# DRI-21700-flexpcb-12s4p.net
KiCad netlist of a schematic drawn in EAGLE
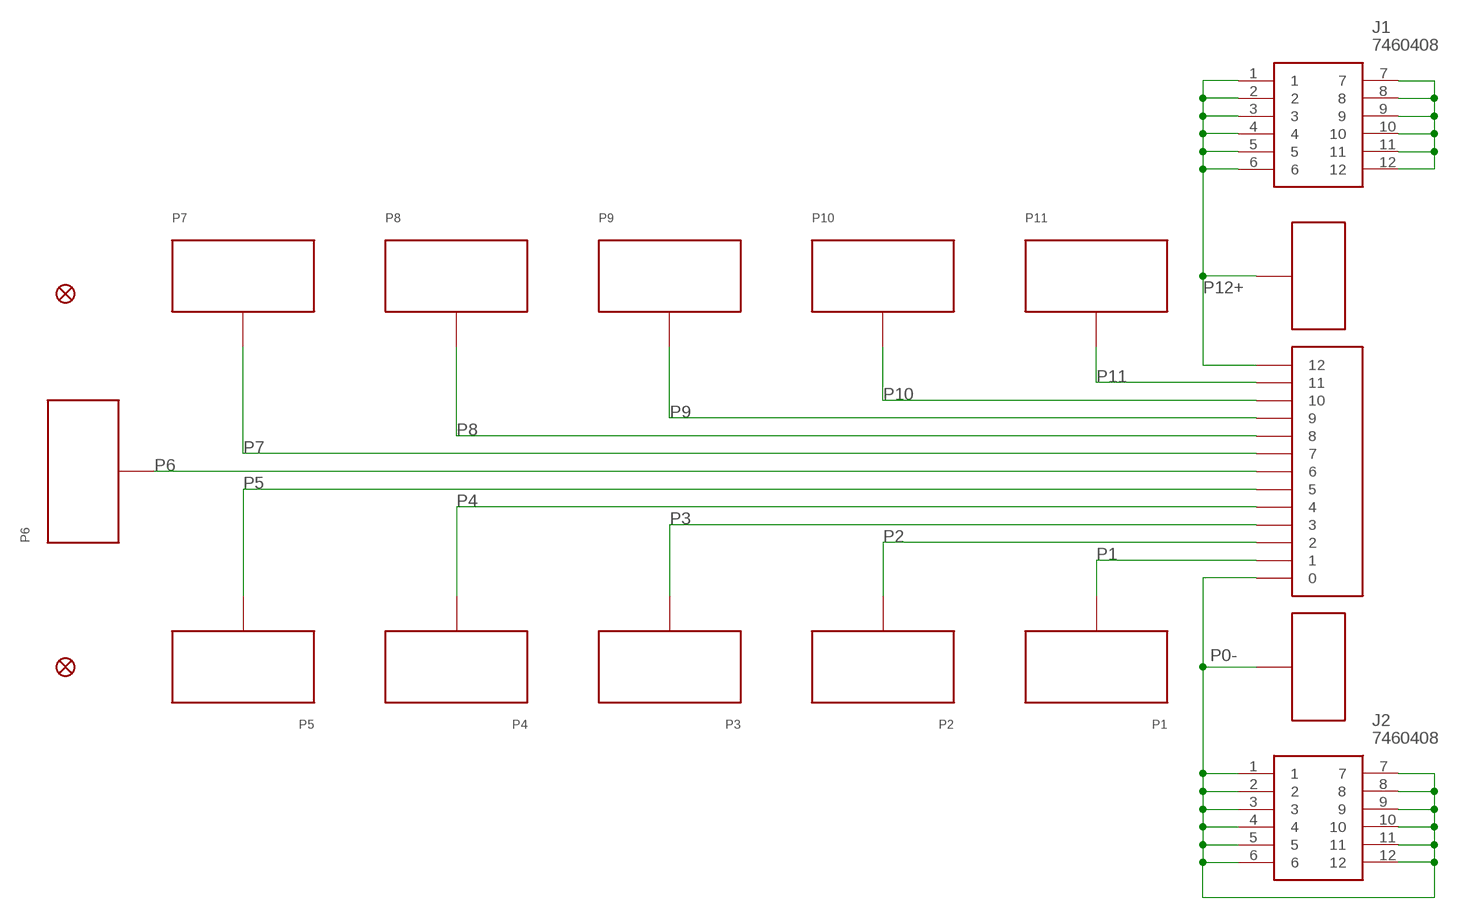
[diagram p0: schematic, sheet 1]

(export (version "E")
  (design (tool "Eeschema 10.0.6"))
  (components
    (comp (ref "FD1")
      (value "FIDUCIAL1X2")
      (footprint "eagle-import:FIDUCIAL-1X2")
      (libsource (lib "eagle-import") (part "FIDUCIAL1X2"))
    )
    (comp (ref "FD2")
      (value "FIDUCIAL1X2")
      (footprint "eagle-import:FIDUCIAL-1X2")
      (libsource (lib "eagle-import") (part "FIDUCIAL1X2"))
    )
    (comp (ref "J1")
      (value "7460408")
      (footprint "eagle-import:7460408")
      (fields (field (name "MOUSER_PART_NUMBER") "710-7460408"))
      (libsource (lib "eagle-import") (part "7460408"))
    )
    (comp (ref "J2")
      (value "7460408")
      (footprint "eagle-import:7460408")
      (fields (field (name "MOUSER_PART_NUMBER") "710-7460408"))
      (libsource (lib "eagle-import") (part "7460408"))
    )
    (comp (ref "JP1")
      (value "13P-JST-2MM")
      (footprint "eagle-import:13P-JST-2MM")
      (libsource (lib "eagle-import") (part "13P-JST-2MM"))
    )
    (comp (ref "P0")
      (value "BUS-TERM-PAD+")
      (footprint "eagle-import:TERM-PAD-")
      (libsource (lib "eagle-import") (part "BUS-TERM-PAD+"))
    )
    (comp (ref "P1")
      (value "BAT-TERM-L")
      (footprint "eagle-import:BAT-TERM-L")
      (libsource (lib "eagle-import") (part "BAT-TERM-L"))
    )
    (comp (ref "P2")
      (value "BAT-TERM-M")
      (footprint "eagle-import:BAT-TERM-M")
      (libsource (lib "eagle-import") (part "BAT-TERM-M"))
    )
    (comp (ref "P3")
      (value "BAT-TERM-L")
      (footprint "eagle-import:BAT-TERM-L")
      (libsource (lib "eagle-import") (part "BAT-TERM-L"))
    )
    (comp (ref "P4")
      (value "BAT-TERM-M")
      (footprint "eagle-import:BAT-TERM-M")
      (libsource (lib "eagle-import") (part "BAT-TERM-M"))
    )
    (comp (ref "P5")
      (value "BAT-TERM-L")
      (footprint "eagle-import:BAT-TERM-L")
      (libsource (lib "eagle-import") (part "BAT-TERM-L"))
    )
    (comp (ref "P6")
      (value "BAT-TERM-END")
      (footprint "eagle-import:BAT-TERM-END")
      (libsource (lib "eagle-import") (part "BAT-TERM-END"))
    )
    (comp (ref "P7")
      (value "BAT-TERM-L")
      (footprint "eagle-import:BAT-TERM-L")
      (libsource (lib "eagle-import") (part "BAT-TERM-L"))
    )
    (comp (ref "P8")
      (value "BAT-TERM-M")
      (footprint "eagle-import:BAT-TERM-M")
      (libsource (lib "eagle-import") (part "BAT-TERM-M"))
    )
    (comp (ref "P9")
      (value "BAT-TERM-L")
      (footprint "eagle-import:BAT-TERM-L")
      (libsource (lib "eagle-import") (part "BAT-TERM-L"))
    )
    (comp (ref "P10")
      (value "BAT-TERM-M")
      (footprint "eagle-import:BAT-TERM-M")
      (libsource (lib "eagle-import") (part "BAT-TERM-M"))
    )
    (comp (ref "P11")
      (value "BAT-TERM-L")
      (footprint "eagle-import:BAT-TERM-L")
      (libsource (lib "eagle-import") (part "BAT-TERM-L"))
    )
    (comp (ref "P12")
      (value "BUS-TERM-PAD+")
      (footprint "eagle-import:TERM-PAD-")
      (libsource (lib "eagle-import") (part "BUS-TERM-PAD+"))
    )
  )
  (nets
    (net (code "1") (name "/P0-") (class "Default")
      (node (ref "J2") (pin "1") (pinfunction "1_1") (pintype "bidirectional"))
      (node (ref "J2") (pin "10") (pinfunction "10_10") (pintype "bidirectional"))
      (node (ref "J2") (pin "11") (pinfunction "11_11") (pintype "bidirectional"))
      (node (ref "J2") (pin "12") (pinfunction "12_12") (pintype "bidirectional"))
      (node (ref "J2") (pin "2") (pinfunction "2_2") (pintype "bidirectional"))
      (node (ref "J2") (pin "3") (pinfunction "3_3") (pintype "bidirectional"))
      (node (ref "J2") (pin "4") (pinfunction "4_4") (pintype "bidirectional"))
      (node (ref "J2") (pin "5") (pinfunction "5_5") (pintype "bidirectional"))
      (node (ref "J2") (pin "6") (pinfunction "6_6") (pintype "bidirectional"))
      (node (ref "J2") (pin "7") (pinfunction "7_7") (pintype "bidirectional"))
      (node (ref "J2") (pin "8") (pinfunction "8_8") (pintype "bidirectional"))
      (node (ref "J2") (pin "9") (pinfunction "9_9") (pintype "bidirectional"))
      (node (ref "JP1") (pin "P$1") (pinfunction "0_P$1") (pintype "bidirectional"))
      (node (ref "P0") (pin "P$10") (pinfunction "P$0_P$10") (pintype "power_in"))
      (node (ref "P0") (pin "P$100") (pinfunction "P$0_P$100") (pintype "power_in"))
      (node (ref "P0") (pin "P$101") (pinfunction "P$0_P$101") (pintype "power_in"))
      (node (ref "P0") (pin "P$102") (pinfunction "P$0_P$102") (pintype "power_in"))
      (node (ref "P0") (pin "P$103") (pinfunction "P$0_P$103") (pintype "power_in"))
      (node (ref "P0") (pin "P$104") (pinfunction "P$0_P$104") (pintype "power_in"))
      (node (ref "P0") (pin "P$105") (pinfunction "P$0_P$105") (pintype "power_in"))
      (node (ref "P0") (pin "P$106") (pinfunction "P$0_P$106") (pintype "power_in"))
      (node (ref "P0") (pin "P$107") (pinfunction "P$0_P$107") (pintype "power_in"))
      (node (ref "P0") (pin "P$108") (pinfunction "P$0_P$108") (pintype "power_in"))
      (node (ref "P0") (pin "P$109") (pinfunction "P$0_P$109") (pintype "power_in"))
      (node (ref "P0") (pin "P$11") (pinfunction "P$0_P$11") (pintype "power_in"))
      (node (ref "P0") (pin "P$110") (pinfunction "P$0_P$110") (pintype "power_in"))
      (node (ref "P0") (pin "P$12") (pinfunction "P$0_P$12") (pintype "power_in"))
      (node (ref "P0") (pin "P$13") (pinfunction "P$0_P$13") (pintype "power_in"))
      (node (ref "P0") (pin "P$14") (pinfunction "P$0_P$14") (pintype "power_in"))
      (node (ref "P0") (pin "P$15") (pinfunction "P$0_P$15") (pintype "power_in"))
      (node (ref "P0") (pin "P$16") (pinfunction "P$0_P$16") (pintype "power_in"))
      (node (ref "P0") (pin "P$17") (pinfunction "P$0_P$17") (pintype "power_in"))
      (node (ref "P0") (pin "P$18") (pinfunction "P$0_P$18") (pintype "power_in"))
      (node (ref "P0") (pin "P$181") (pinfunction "P$0_P$181") (pintype "power_in"))
      (node (ref "P0") (pin "P$182") (pinfunction "P$0_P$182") (pintype "power_in"))
      (node (ref "P0") (pin "P$183") (pinfunction "P$0_P$183") (pintype "power_in"))
      (node (ref "P0") (pin "P$184") (pinfunction "P$0_P$184") (pintype "power_in"))
      (node (ref "P0") (pin "P$185") (pinfunction "P$0_P$185") (pintype "power_in"))
      (node (ref "P0") (pin "P$186") (pinfunction "P$0_P$186") (pintype "power_in"))
      (node (ref "P0") (pin "P$187") (pinfunction "P$0_P$187") (pintype "power_in"))
      (node (ref "P0") (pin "P$188") (pinfunction "P$0_P$188") (pintype "power_in"))
      (node (ref "P0") (pin "P$189") (pinfunction "P$0_P$189") (pintype "power_in"))
      (node (ref "P0") (pin "P$19") (pinfunction "P$0_P$19") (pintype "power_in"))
      (node (ref "P0") (pin "P$190") (pinfunction "P$0_P$190") (pintype "power_in"))
      (node (ref "P0") (pin "P$191") (pinfunction "P$0_P$191") (pintype "power_in"))
      (node (ref "P0") (pin "P$192") (pinfunction "P$0_P$192") (pintype "power_in"))
      (node (ref "P0") (pin "P$193") (pinfunction "P$0_P$193") (pintype "power_in"))
      (node (ref "P0") (pin "P$194") (pinfunction "P$0_P$194") (pintype "power_in"))
      (node (ref "P0") (pin "P$195") (pinfunction "P$0_P$195") (pintype "power_in"))
      (node (ref "P0") (pin "P$196") (pinfunction "P$0_P$196") (pintype "power_in"))
      (node (ref "P0") (pin "P$197") (pinfunction "P$0_P$197") (pintype "power_in"))
      (node (ref "P0") (pin "P$198") (pinfunction "P$0_P$198") (pintype "power_in"))
      (node (ref "P0") (pin "P$199") (pinfunction "P$0_P$199") (pintype "power_in"))
      (node (ref "P0") (pin "P$20") (pinfunction "P$0_P$20") (pintype "power_in"))
      (node (ref "P0") (pin "P$200") (pinfunction "P$0_P$200") (pintype "power_in"))
      (node (ref "P0") (pin "P$201") (pinfunction "P$0_P$201") (pintype "power_in"))
      (node (ref "P0") (pin "P$202") (pinfunction "P$0_P$202") (pintype "power_in"))
      (node (ref "P0") (pin "P$203") (pinfunction "P$0_P$203") (pintype "power_in"))
      (node (ref "P0") (pin "P$204") (pinfunction "P$0_P$204") (pintype "power_in"))
      (node (ref "P0") (pin "P$205") (pinfunction "P$0_P$205") (pintype "power_in"))
      (node (ref "P0") (pin "P$206") (pinfunction "P$0_P$206") (pintype "power_in"))
      (node (ref "P0") (pin "P$207") (pinfunction "P$0_P$207") (pintype "power_in"))
      (node (ref "P0") (pin "P$208") (pinfunction "P$0_P$208") (pintype "power_in"))
      (node (ref "P0") (pin "P$209") (pinfunction "P$0_P$209") (pintype "power_in"))
      (node (ref "P0") (pin "P$21") (pinfunction "P$0_P$21") (pintype "power_in"))
      (node (ref "P0") (pin "P$210") (pinfunction "P$0_P$210") (pintype "power_in"))
      (node (ref "P0") (pin "P$211") (pinfunction "P$0_P$211") (pintype "power_in"))
      (node (ref "P0") (pin "P$212") (pinfunction "P$0_P$212") (pintype "power_in"))
      (node (ref "P0") (pin "P$213") (pinfunction "P$0_P$213") (pintype "power_in"))
      (node (ref "P0") (pin "P$214") (pinfunction "P$0_P$214") (pintype "power_in"))
      (node (ref "P0") (pin "P$215") (pinfunction "P$0_P$215") (pintype "power_in"))
      (node (ref "P0") (pin "P$216") (pinfunction "P$0_P$216") (pintype "power_in"))
      (node (ref "P0") (pin "P$217") (pinfunction "P$0_P$217") (pintype "power_in"))
      (node (ref "P0") (pin "P$218") (pinfunction "P$0_P$218") (pintype "power_in"))
      (node (ref "P0") (pin "P$219") (pinfunction "P$0_P$219") (pintype "power_in"))
      (node (ref "P0") (pin "P$22") (pinfunction "P$0_P$22") (pintype "power_in"))
      (node (ref "P0") (pin "P$220") (pinfunction "P$0_P$220") (pintype "power_in"))
      (node (ref "P0") (pin "P$221") (pinfunction "P$0_P$221") (pintype "power_in"))
      (node (ref "P0") (pin "P$222") (pinfunction "P$0_P$222") (pintype "power_in"))
      (node (ref "P0") (pin "P$223") (pinfunction "P$0_P$223") (pintype "power_in"))
      (node (ref "P0") (pin "P$224") (pinfunction "P$0_P$224") (pintype "power_in"))
      (node (ref "P0") (pin "P$225") (pinfunction "P$0_P$225") (pintype "power_in"))
      (node (ref "P0") (pin "P$226") (pinfunction "P$0_P$226") (pintype "power_in"))
      (node (ref "P0") (pin "P$227") (pinfunction "P$0_P$227") (pintype "power_in"))
      (node (ref "P0") (pin "P$228") (pinfunction "P$0_P$228") (pintype "power_in"))
      (node (ref "P0") (pin "P$229") (pinfunction "P$0_P$229") (pintype "power_in"))
      (node (ref "P0") (pin "P$23") (pinfunction "P$0_P$23") (pintype "power_in"))
      (node (ref "P0") (pin "P$230") (pinfunction "P$0_P$230") (pintype "power_in"))
      (node (ref "P0") (pin "P$231") (pinfunction "P$0_P$231") (pintype "power_in"))
      (node (ref "P0") (pin "P$232") (pinfunction "P$0_P$232") (pintype "power_in"))
      (node (ref "P0") (pin "P$233") (pinfunction "P$0_P$233") (pintype "power_in"))
      (node (ref "P0") (pin "P$234") (pinfunction "P$0_P$234") (pintype "power_in"))
      (node (ref "P0") (pin "P$235") (pinfunction "P$0_P$235") (pintype "power_in"))
      (node (ref "P0") (pin "P$236") (pinfunction "P$0_P$236") (pintype "power_in"))
      (node (ref "P0") (pin "P$237") (pinfunction "P$0_P$237") (pintype "power_in"))
      (node (ref "P0") (pin "P$238") (pinfunction "P$0_P$238") (pintype "power_in"))
      (node (ref "P0") (pin "P$239") (pinfunction "P$0_P$239") (pintype "power_in"))
      (node (ref "P0") (pin "P$24") (pinfunction "P$0_P$24") (pintype "power_in"))
      (node (ref "P0") (pin "P$240") (pinfunction "P$0_P$240") (pintype "power_in"))
      (node (ref "P0") (pin "P$241") (pinfunction "P$0_P$241") (pintype "power_in"))
      (node (ref "P0") (pin "P$242") (pinfunction "P$0_P$242") (pintype "power_in"))
      (node (ref "P0") (pin "P$243") (pinfunction "P$0_P$243") (pintype "power_in"))
      (node (ref "P0") (pin "P$244") (pinfunction "P$0_P$244") (pintype "power_in"))
      (node (ref "P0") (pin "P$245") (pinfunction "P$0_P$245") (pintype "power_in"))
      (node (ref "P0") (pin "P$246") (pinfunction "P$0_P$246") (pintype "power_in"))
      (node (ref "P0") (pin "P$247") (pinfunction "P$0_P$247") (pintype "power_in"))
      (node (ref "P0") (pin "P$248") (pinfunction "P$0_P$248") (pintype "power_in"))
      (node (ref "P0") (pin "P$249") (pinfunction "P$0_P$249") (pintype "power_in"))
      (node (ref "P0") (pin "P$25") (pinfunction "P$0_P$25") (pintype "power_in"))
      (node (ref "P0") (pin "P$250") (pinfunction "P$0_P$250") (pintype "power_in"))
      (node (ref "P0") (pin "P$251") (pinfunction "P$0_P$251") (pintype "power_in"))
      (node (ref "P0") (pin "P$252") (pinfunction "P$0_P$252") (pintype "power_in"))
      (node (ref "P0") (pin "P$253") (pinfunction "P$0_P$253") (pintype "power_in"))
      (node (ref "P0") (pin "P$254") (pinfunction "P$0_P$254") (pintype "power_in"))
      (node (ref "P0") (pin "P$255") (pinfunction "P$0_P$255") (pintype "power_in"))
      (node (ref "P0") (pin "P$256") (pinfunction "P$0_P$256") (pintype "power_in"))
      (node (ref "P0") (pin "P$257") (pinfunction "P$0_P$257") (pintype "power_in"))
      (node (ref "P0") (pin "P$258") (pinfunction "P$0_P$258") (pintype "power_in"))
      (node (ref "P0") (pin "P$259") (pinfunction "P$0_P$259") (pintype "power_in"))
      (node (ref "P0") (pin "P$26") (pinfunction "P$0_P$26") (pintype "power_in"))
      (node (ref "P0") (pin "P$260") (pinfunction "P$0_P$260") (pintype "power_in"))
      (node (ref "P0") (pin "P$261") (pinfunction "P$0_P$261") (pintype "power_in"))
      (node (ref "P0") (pin "P$262") (pinfunction "P$0_P$262") (pintype "power_in"))
      (node (ref "P0") (pin "P$263") (pinfunction "P$0_P$263") (pintype "power_in"))
      (node (ref "P0") (pin "P$264") (pinfunction "P$0_P$264") (pintype "power_in"))
      (node (ref "P0") (pin "P$265") (pinfunction "P$0_P$265") (pintype "power_in"))
      (node (ref "P0") (pin "P$266") (pinfunction "P$0_P$266") (pintype "power_in"))
      (node (ref "P0") (pin "P$267") (pinfunction "P$0_P$267") (pintype "power_in"))
      (node (ref "P0") (pin "P$268") (pinfunction "P$0_P$268") (pintype "power_in"))
      (node (ref "P0") (pin "P$269") (pinfunction "P$0_P$269") (pintype "power_in"))
      (node (ref "P0") (pin "P$27") (pinfunction "P$0_P$27") (pintype "power_in"))
      (node (ref "P0") (pin "P$270") (pinfunction "P$0_P$270") (pintype "power_in"))
      (node (ref "P0") (pin "P$271") (pinfunction "P$0_P$271") (pintype "power_in"))
      (node (ref "P0") (pin "P$272") (pinfunction "P$0_P$272") (pintype "power_in"))
      (node (ref "P0") (pin "P$273") (pinfunction "P$0_P$273") (pintype "power_in"))
      (node (ref "P0") (pin "P$274") (pinfunction "P$0_P$274") (pintype "power_in"))
      (node (ref "P0") (pin "P$275") (pinfunction "P$0_P$275") (pintype "power_in"))
      (node (ref "P0") (pin "P$276") (pinfunction "P$0_P$276") (pintype "power_in"))
      (node (ref "P0") (pin "P$277") (pinfunction "P$0_P$277") (pintype "power_in"))
      (node (ref "P0") (pin "P$278") (pinfunction "P$0_P$278") (pintype "power_in"))
      (node (ref "P0") (pin "P$279") (pinfunction "P$0_P$279") (pintype "power_in"))
      (node (ref "P0") (pin "P$28") (pinfunction "P$0_P$28") (pintype "power_in"))
      (node (ref "P0") (pin "P$280") (pinfunction "P$0_P$280") (pintype "power_in"))
      (node (ref "P0") (pin "P$281") (pinfunction "P$0_P$281") (pintype "power_in"))
      (node (ref "P0") (pin "P$282") (pinfunction "P$0_P$282") (pintype "power_in"))
      (node (ref "P0") (pin "P$283") (pinfunction "P$0_P$283") (pintype "power_in"))
      (node (ref "P0") (pin "P$284") (pinfunction "P$0_P$284") (pintype "power_in"))
      (node (ref "P0") (pin "P$285") (pinfunction "P$0_P$285") (pintype "power_in"))
      (node (ref "P0") (pin "P$286") (pinfunction "P$0_P$286") (pintype "power_in"))
      (node (ref "P0") (pin "P$287") (pinfunction "P$0_P$287") (pintype "power_in"))
      (node (ref "P0") (pin "P$288") (pinfunction "P$0_P$288") (pintype "power_in"))
      (node (ref "P0") (pin "P$289") (pinfunction "P$0_P$289") (pintype "power_in"))
      (node (ref "P0") (pin "P$29") (pinfunction "P$0_P$29") (pintype "power_in"))
      (node (ref "P0") (pin "P$290") (pinfunction "P$0_P$290") (pintype "power_in"))
      (node (ref "P0") (pin "P$291") (pinfunction "P$0_P$291") (pintype "power_in"))
      (node (ref "P0") (pin "P$292") (pinfunction "P$0_P$292") (pintype "power_in"))
      (node (ref "P0") (pin "P$293") (pinfunction "P$0_P$293") (pintype "power_in"))
      (node (ref "P0") (pin "P$294") (pinfunction "P$0_P$294") (pintype "power_in"))
      (node (ref "P0") (pin "P$295") (pinfunction "P$0_P$295") (pintype "power_in"))
      (node (ref "P0") (pin "P$296") (pinfunction "P$0_P$296") (pintype "power_in"))
      (node (ref "P0") (pin "P$297") (pinfunction "P$0_P$297") (pintype "power_in"))
      (node (ref "P0") (pin "P$298") (pinfunction "P$0_P$298") (pintype "power_in"))
      (node (ref "P0") (pin "P$299") (pinfunction "P$0_P$299") (pintype "power_in"))
      (node (ref "P0") (pin "P$3") (pinfunction "P$0_P$3") (pintype "power_in"))
      (node (ref "P0") (pin "P$30") (pinfunction "P$0_P$30") (pintype "power_in"))
      (node (ref "P0") (pin "P$300") (pinfunction "P$0_P$300") (pintype "power_in"))
      (node (ref "P0") (pin "P$301") (pinfunction "P$0_P$301") (pintype "power_in"))
      (node (ref "P0") (pin "P$302") (pinfunction "P$0_P$302") (pintype "power_in"))
      (node (ref "P0") (pin "P$303") (pinfunction "P$0_P$303") (pintype "power_in"))
      (node (ref "P0") (pin "P$304") (pinfunction "P$0_P$304") (pintype "power_in"))
      (node (ref "P0") (pin "P$305") (pinfunction "P$0_P$305") (pintype "power_in"))
      (node (ref "P0") (pin "P$306") (pinfunction "P$0_P$306") (pintype "power_in"))
      (node (ref "P0") (pin "P$307") (pinfunction "P$0_P$307") (pintype "power_in"))
      (node (ref "P0") (pin "P$308") (pinfunction "P$0_P$308") (pintype "power_in"))
      (node (ref "P0") (pin "P$309") (pinfunction "P$0_P$309") (pintype "power_in"))
      (node (ref "P0") (pin "P$31") (pinfunction "P$0_P$31") (pintype "power_in"))
      (node (ref "P0") (pin "P$310") (pinfunction "P$0_P$310") (pintype "power_in"))
      (node (ref "P0") (pin "P$311") (pinfunction "P$0_P$311") (pintype "power_in"))
      (node (ref "P0") (pin "P$312") (pinfunction "P$0_P$312") (pintype "power_in"))
      (node (ref "P0") (pin "P$313") (pinfunction "P$0_P$313") (pintype "power_in"))
      (node (ref "P0") (pin "P$314") (pinfunction "P$0_P$314") (pintype "power_in"))
      (node (ref "P0") (pin "P$315") (pinfunction "P$0_P$315") (pintype "power_in"))
      (node (ref "P0") (pin "P$316") (pinfunction "P$0_P$316") (pintype "power_in"))
      (node (ref "P0") (pin "P$317") (pinfunction "P$0_P$317") (pintype "power_in"))
      (node (ref "P0") (pin "P$318") (pinfunction "P$0_P$318") (pintype "power_in"))
      (node (ref "P0") (pin "P$319") (pinfunction "P$0_P$319") (pintype "power_in"))
      (node (ref "P0") (pin "P$32") (pinfunction "P$0_P$32") (pintype "power_in"))
      (node (ref "P0") (pin "P$320") (pinfunction "P$0_P$320") (pintype "power_in"))
      (node (ref "P0") (pin "P$321") (pinfunction "P$0_P$321") (pintype "power_in"))
      (node (ref "P0") (pin "P$322") (pinfunction "P$0_P$322") (pintype "power_in"))
      (node (ref "P0") (pin "P$323") (pinfunction "P$0_P$323") (pintype "power_in"))
      (node (ref "P0") (pin "P$324") (pinfunction "P$0_P$324") (pintype "power_in"))
      (node (ref "P0") (pin "P$325") (pinfunction "P$0_P$325") (pintype "power_in"))
      (node (ref "P0") (pin "P$326") (pinfunction "P$0_P$326") (pintype "power_in"))
      (node (ref "P0") (pin "P$327") (pinfunction "P$0_P$327") (pintype "power_in"))
      (node (ref "P0") (pin "P$328") (pinfunction "P$0_P$328") (pintype "power_in"))
      (node (ref "P0") (pin "P$329") (pinfunction "P$0_P$329") (pintype "power_in"))
      (node (ref "P0") (pin "P$33") (pinfunction "P$0_P$33") (pintype "power_in"))
      (node (ref "P0") (pin "P$330") (pinfunction "P$0_P$330") (pintype "power_in"))
      (node (ref "P0") (pin "P$331") (pinfunction "P$0_P$331") (pintype "power_in"))
      (node (ref "P0") (pin "P$332") (pinfunction "P$0_P$332") (pintype "power_in"))
      (node (ref "P0") (pin "P$333") (pinfunction "P$0_P$333") (pintype "power_in"))
      (node (ref "P0") (pin "P$334") (pinfunction "P$0_P$334") (pintype "power_in"))
      (node (ref "P0") (pin "P$335") (pinfunction "P$0_P$335") (pintype "power_in"))
      (node (ref "P0") (pin "P$336") (pinfunction "P$0_P$336") (pintype "power_in"))
      (node (ref "P0") (pin "P$337") (pinfunction "P$0_P$337") (pintype "power_in"))
      (node (ref "P0") (pin "P$338") (pinfunction "P$0_P$338") (pintype "power_in"))
      (node (ref "P0") (pin "P$339") (pinfunction "P$0_P$339") (pintype "power_in"))
      (node (ref "P0") (pin "P$34") (pinfunction "P$0_P$34") (pintype "power_in"))
      (node (ref "P0") (pin "P$340") (pinfunction "P$0_P$340") (pintype "power_in"))
      (node (ref "P0") (pin "P$341") (pinfunction "P$0_P$341") (pintype "power_in"))
      (node (ref "P0") (pin "P$342") (pinfunction "P$0_P$342") (pintype "power_in"))
      (node (ref "P0") (pin "P$343") (pinfunction "P$0_P$343") (pintype "power_in"))
      (node (ref "P0") (pin "P$344") (pinfunction "P$0_P$344") (pintype "power_in"))
      (node (ref "P0") (pin "P$345") (pinfunction "P$0_P$345") (pintype "power_in"))
      (node (ref "P0") (pin "P$346") (pinfunction "P$0_P$346") (pintype "power_in"))
      (node (ref "P0") (pin "P$347") (pinfunction "P$0_P$347") (pintype "power_in"))
      (node (ref "P0") (pin "P$348") (pinfunction "P$0_P$348") (pintype "power_in"))
      (node (ref "P0") (pin "P$349") (pinfunction "P$0_P$349") (pintype "power_in"))
      (node (ref "P0") (pin "P$35") (pinfunction "P$0_P$35") (pintype "power_in"))
      (node (ref "P0") (pin "P$350") (pinfunction "P$0_P$350") (pintype "power_in"))
      (node (ref "P0") (pin "P$351") (pinfunction "P$0_P$351") (pintype "power_in"))
      (node (ref "P0") (pin "P$352") (pinfunction "P$0_P$352") (pintype "power_in"))
      (node (ref "P0") (pin "P$353") (pinfunction "P$0_P$353") (pintype "power_in"))
      (node (ref "P0") (pin "P$354") (pinfunction "P$0_P$354") (pintype "power_in"))
      (node (ref "P0") (pin "P$355") (pinfunction "P$0_P$355") (pintype "power_in"))
      (node (ref "P0") (pin "P$356") (pinfunction "P$0_P$356") (pintype "power_in"))
      (node (ref "P0") (pin "P$357") (pinfunction "P$0_P$357") (pintype "power_in"))
      (node (ref "P0") (pin "P$358") (pinfunction "P$0_P$358") (pintype "power_in"))
      (node (ref "P0") (pin "P$359") (pinfunction "P$0_P$359") (pintype "power_in"))
      (node (ref "P0") (pin "P$36") (pinfunction "P$0_P$36") (pintype "power_in"))
      (node (ref "P0") (pin "P$360") (pinfunction "P$0_P$360") (pintype "power_in"))
      (node (ref "P0") (pin "P$37") (pinfunction "P$0_P$37") (pintype "power_in"))
      (node (ref "P0") (pin "P$38") (pinfunction "P$0_P$38") (pintype "power_in"))
      (node (ref "P0") (pin "P$39") (pinfunction "P$0_P$39") (pintype "power_in"))
      (node (ref "P0") (pin "P$4") (pinfunction "P$0_P$4") (pintype "power_in"))
      (node (ref "P0") (pin "P$40") (pinfunction "P$0_P$40") (pintype "power_in"))
      (node (ref "P0") (pin "P$41") (pinfunction "P$0_P$41") (pintype "power_in"))
      (node (ref "P0") (pin "P$42") (pinfunction "P$0_P$42") (pintype "power_in"))
      (node (ref "P0") (pin "P$43") (pinfunction "P$0_P$43") (pintype "power_in"))
      (node (ref "P0") (pin "P$44") (pinfunction "P$0_P$44") (pintype "power_in"))
      (node (ref "P0") (pin "P$45") (pinfunction "P$0_P$45") (pintype "power_in"))
      (node (ref "P0") (pin "P$46") (pinfunction "P$0_P$46") (pintype "power_in"))
      (node (ref "P0") (pin "P$47") (pinfunction "P$0_P$47") (pintype "power_in"))
      (node (ref "P0") (pin "P$48") (pinfunction "P$0_P$48") (pintype "power_in"))
      (node (ref "P0") (pin "P$49") (pinfunction "P$0_P$49") (pintype "power_in"))
      (node (ref "P0") (pin "P$5") (pinfunction "P$0_P$5") (pintype "power_in"))
      (node (ref "P0") (pin "P$50") (pinfunction "P$0_P$50") (pintype "power_in"))
      (node (ref "P0") (pin "P$51") (pinfunction "P$0_P$51") (pintype "power_in"))
      (node (ref "P0") (pin "P$52") (pinfunction "P$0_P$52") (pintype "power_in"))
      (node (ref "P0") (pin "P$53") (pinfunction "P$0_P$53") (pintype "power_in"))
      (node (ref "P0") (pin "P$54") (pinfunction "P$0_P$54") (pintype "power_in"))
      (node (ref "P0") (pin "P$55") (pinfunction "P$0_P$55") (pintype "power_in"))
      (node (ref "P0") (pin "P$56") (pinfunction "P$0_P$56") (pintype "power_in"))
      (node (ref "P0") (pin "P$57") (pinfunction "P$0_P$57") (pintype "power_in"))
      (node (ref "P0") (pin "P$58") (pinfunction "P$0_P$58") (pintype "power_in"))
      (node (ref "P0") (pin "P$59") (pinfunction "P$0_P$59") (pintype "power_in"))
      (node (ref "P0") (pin "P$6") (pinfunction "P$0_P$6") (pintype "power_in"))
      (node (ref "P0") (pin "P$60") (pinfunction "P$0_P$60") (pintype "power_in"))
      (node (ref "P0") (pin "P$61") (pinfunction "P$0_P$61") (pintype "power_in"))
      (node (ref "P0") (pin "P$62") (pinfunction "P$0_P$62") (pintype "power_in"))
      (node (ref "P0") (pin "P$63") (pinfunction "P$0_P$63") (pintype "power_in"))
      (node (ref "P0") (pin "P$64") (pinfunction "P$0_P$64") (pintype "power_in"))
      (node (ref "P0") (pin "P$65") (pinfunction "P$0_P$65") (pintype "power_in"))
      (node (ref "P0") (pin "P$66") (pinfunction "P$0_P$66") (pintype "power_in"))
      (node (ref "P0") (pin "P$67") (pinfunction "P$0_P$67") (pintype "power_in"))
      (node (ref "P0") (pin "P$68") (pinfunction "P$0_P$68") (pintype "power_in"))
      (node (ref "P0") (pin "P$69") (pinfunction "P$0_P$69") (pintype "power_in"))
      (node (ref "P0") (pin "P$7") (pinfunction "P$0_P$7") (pintype "power_in"))
      (node (ref "P0") (pin "P$70") (pinfunction "P$0_P$70") (pintype "power_in"))
      (node (ref "P0") (pin "P$71") (pinfunction "P$0_P$71") (pintype "power_in"))
      (node (ref "P0") (pin "P$72") (pinfunction "P$0_P$72") (pintype "power_in"))
      (node (ref "P0") (pin "P$73") (pinfunction "P$0_P$73") (pintype "power_in"))
      (node (ref "P0") (pin "P$74") (pinfunction "P$0_P$74") (pintype "power_in"))
      (node (ref "P0") (pin "P$75") (pinfunction "P$0_P$75") (pintype "power_in"))
      (node (ref "P0") (pin "P$76") (pinfunction "P$0_P$76") (pintype "power_in"))
      (node (ref "P0") (pin "P$77") (pinfunction "P$0_P$77") (pintype "power_in"))
      (node (ref "P0") (pin "P$78") (pinfunction "P$0_P$78") (pintype "power_in"))
      (node (ref "P0") (pin "P$79") (pinfunction "P$0_P$79") (pintype "power_in"))
      (node (ref "P0") (pin "P$8") (pinfunction "P$0_P$8") (pintype "power_in"))
      (node (ref "P0") (pin "P$80") (pinfunction "P$0_P$80") (pintype "power_in"))
      (node (ref "P0") (pin "P$81") (pinfunction "P$0_P$81") (pintype "power_in"))
      (node (ref "P0") (pin "P$82") (pinfunction "P$0_P$82") (pintype "power_in"))
      (node (ref "P0") (pin "P$83") (pinfunction "P$0_P$83") (pintype "power_in"))
      (node (ref "P0") (pin "P$84") (pinfunction "P$0_P$84") (pintype "power_in"))
      (node (ref "P0") (pin "P$85") (pinfunction "P$0_P$85") (pintype "power_in"))
      (node (ref "P0") (pin "P$86") (pinfunction "P$0_P$86") (pintype "power_in"))
      (node (ref "P0") (pin "P$87") (pinfunction "P$0_P$87") (pintype "power_in"))
      (node (ref "P0") (pin "P$88") (pinfunction "P$0_P$88") (pintype "power_in"))
      (node (ref "P0") (pin "P$89") (pinfunction "P$0_P$89") (pintype "power_in"))
      (node (ref "P0") (pin "P$9") (pinfunction "P$0_P$9") (pintype "power_in"))
      (node (ref "P0") (pin "P$90") (pinfunction "P$0_P$90") (pintype "power_in"))
      (node (ref "P0") (pin "P$91") (pinfunction "P$0_P$91") (pintype "power_in"))
      (node (ref "P0") (pin "P$92") (pinfunction "P$0_P$92") (pintype "power_in"))
      (node (ref "P0") (pin "P$93") (pinfunction "P$0_P$93") (pintype "power_in"))
      (node (ref "P0") (pin "P$94") (pinfunction "P$0_P$94") (pintype "power_in"))
      (node (ref "P0") (pin "P$95") (pinfunction "P$0_P$95") (pintype "power_in"))
      (node (ref "P0") (pin "P$96") (pinfunction "P$0_P$96") (pintype "power_in"))
      (node (ref "P0") (pin "P$97") (pinfunction "P$0_P$97") (pintype "power_in"))
      (node (ref "P0") (pin "P$98") (pinfunction "P$0_P$98") (pintype "power_in"))
      (node (ref "P0") (pin "P$99") (pinfunction "P$0_P$99") (pintype "power_in"))
    )
    (net (code "2") (name "/P1") (class "Default")
      (node (ref "JP1") (pin "P$2") (pinfunction "1_P$2") (pintype "bidirectional"))
      (node (ref "P1") (pin "P$10") (pinfunction "P$1_P$10") (pintype "power_in"))
      (node (ref "P1") (pin "P$100") (pinfunction "P$1_P$100") (pintype "power_in"))
      (node (ref "P1") (pin "P$101") (pinfunction "P$1_P$101") (pintype "power_in"))
      (node (ref "P1") (pin "P$102") (pinfunction "P$1_P$102") (pintype "power_in"))
      (node (ref "P1") (pin "P$103") (pinfunction "P$1_P$103") (pintype "power_in"))
      (node (ref "P1") (pin "P$104") (pinfunction "P$1_P$104") (pintype "power_in"))
      (node (ref "P1") (pin "P$105") (pinfunction "P$1_P$105") (pintype "power_in"))
      (node (ref "P1") (pin "P$106") (pinfunction "P$1_P$106") (pintype "power_in"))
      (node (ref "P1") (pin "P$107") (pinfunction "P$1_P$107") (pintype "power_in"))
      (node (ref "P1") (pin "P$108") (pinfunction "P$1_P$108") (pintype "power_in"))
      (node (ref "P1") (pin "P$109") (pinfunction "P$1_P$109") (pintype "power_in"))
      (node (ref "P1") (pin "P$11") (pinfunction "P$1_P$11") (pintype "power_in"))
      (node (ref "P1") (pin "P$110") (pinfunction "P$1_P$110") (pintype "power_in"))
      (node (ref "P1") (pin "P$111") (pinfunction "P$1_P$111") (pintype "power_in"))
      (node (ref "P1") (pin "P$112") (pinfunction "P$1_P$112") (pintype "power_in"))
      (node (ref "P1") (pin "P$114") (pinfunction "P$1_P$114") (pintype "power_in"))
      (node (ref "P1") (pin "P$115") (pinfunction "P$1_P$115") (pintype "power_in"))
      (node (ref "P1") (pin "P$116") (pinfunction "P$1_P$116") (pintype "power_in"))
      (node (ref "P1") (pin "P$117") (pinfunction "P$1_P$117") (pintype "power_in"))
      (node (ref "P1") (pin "P$118") (pinfunction "P$1_P$118") (pintype "power_in"))
      (node (ref "P1") (pin "P$119") (pinfunction "P$1_P$119") (pintype "power_in"))
      (node (ref "P1") (pin "P$12") (pinfunction "P$1_P$12") (pintype "power_in"))
      (node (ref "P1") (pin "P$120") (pinfunction "P$1_P$120") (pintype "power_in"))
      (node (ref "P1") (pin "P$121") (pinfunction "P$1_P$121") (pintype "power_in"))
      (node (ref "P1") (pin "P$122") (pinfunction "P$1_P$122") (pintype "power_in"))
      (node (ref "P1") (pin "P$123") (pinfunction "P$1_P$123") (pintype "power_in"))
      (node (ref "P1") (pin "P$124") (pinfunction "P$1_P$124") (pintype "power_in"))
      (node (ref "P1") (pin "P$125") (pinfunction "P$1_P$125") (pintype "power_in"))
      (node (ref "P1") (pin "P$126") (pinfunction "P$1_P$126") (pintype "power_in"))
      (node (ref "P1") (pin "P$127") (pinfunction "P$1_P$127") (pintype "power_in"))
      (node (ref "P1") (pin "P$128") (pinfunction "P$1_P$128") (pintype "power_in"))
      (node (ref "P1") (pin "P$129") (pinfunction "P$1_P$129") (pintype "power_in"))
      (node (ref "P1") (pin "P$13") (pinfunction "P$1_P$13") (pintype "power_in"))
      (node (ref "P1") (pin "P$130") (pinfunction "P$1_P$130") (pintype "power_in"))
      (node (ref "P1") (pin "P$131") (pinfunction "P$1_P$131") (pintype "power_in"))
      (node (ref "P1") (pin "P$132") (pinfunction "P$1_P$132") (pintype "power_in"))
      (node (ref "P1") (pin "P$133") (pinfunction "P$1_P$133") (pintype "power_in"))
      (node (ref "P1") (pin "P$134") (pinfunction "P$1_P$134") (pintype "power_in"))
      (node (ref "P1") (pin "P$135") (pinfunction "P$1_P$135") (pintype "power_in"))
      (node (ref "P1") (pin "P$136") (pinfunction "P$1_P$136") (pintype "power_in"))
      (node (ref "P1") (pin "P$137") (pinfunction "P$1_P$137") (pintype "power_in"))
      (node (ref "P1") (pin "P$138") (pinfunction "P$1_P$138") (pintype "power_in"))
      (node (ref "P1") (pin "P$139") (pinfunction "P$1_P$139") (pintype "power_in"))
      (node (ref "P1") (pin "P$14") (pinfunction "P$1_P$14") (pintype "power_in"))
      (node (ref "P1") (pin "P$140") (pinfunction "P$1_P$140") (pintype "power_in"))
      (node (ref "P1") (pin "P$141") (pinfunction "P$1_P$141") (pintype "power_in"))
      (node (ref "P1") (pin "P$142") (pinfunction "P$1_P$142") (pintype "power_in"))
      (node (ref "P1") (pin "P$143") (pinfunction "P$1_P$143") (pintype "power_in"))
      (node (ref "P1") (pin "P$144") (pinfunction "P$1_P$144") (pintype "power_in"))
      (node (ref "P1") (pin "P$145") (pinfunction "P$1_P$145") (pintype "power_in"))
      (node (ref "P1") (pin "P$146") (pinfunction "P$1_P$146") (pintype "power_in"))
      (node (ref "P1") (pin "P$147") (pinfunction "P$1_P$147") (pintype "power_in"))
      (node (ref "P1") (pin "P$148") (pinfunction "P$1_P$148") (pintype "power_in"))
      (node (ref "P1") (pin "P$149") (pinfunction "P$1_P$149") (pintype "power_in"))
      (node (ref "P1") (pin "P$15") (pinfunction "P$1_P$15") (pintype "power_in"))
      (node (ref "P1") (pin "P$151") (pinfunction "P$1_P$151") (pintype "power_in"))
      (node (ref "P1") (pin "P$152") (pinfunction "P$1_P$152") (pintype "power_in"))
      (node (ref "P1") (pin "P$153") (pinfunction "P$1_P$153") (pintype "power_in"))
      (node (ref "P1") (pin "P$154") (pinfunction "P$1_P$154") (pintype "power_in"))
      (node (ref "P1") (pin "P$155") (pinfunction "P$1_P$155") (pintype "power_in"))
      (node (ref "P1") (pin "P$156") (pinfunction "P$1_P$156") (pintype "power_in"))
      (node (ref "P1") (pin "P$157") (pinfunction "P$1_P$157") (pintype "power_in"))
      (node (ref "P1") (pin "P$158") (pinfunction "P$1_P$158") (pintype "power_in"))
      (node (ref "P1") (pin "P$159") (pinfunction "P$1_P$159") (pintype "power_in"))
      (node (ref "P1") (pin "P$16") (pinfunction "P$1_P$16") (pintype "power_in"))
      (node (ref "P1") (pin "P$160") (pinfunction "P$1_P$160") (pintype "power_in"))
      (node (ref "P1") (pin "P$161") (pinfunction "P$1_P$161") (pintype "power_in"))
      (node (ref "P1") (pin "P$162") (pinfunction "P$1_P$162") (pintype "power_in"))
      (node (ref "P1") (pin "P$163") (pinfunction "P$1_P$163") (pintype "power_in"))
      (node (ref "P1") (pin "P$164") (pinfunction "P$1_P$164") (pintype "power_in"))
      (node (ref "P1") (pin "P$165") (pinfunction "P$1_P$165") (pintype "power_in"))
      (node (ref "P1") (pin "P$166") (pinfunction "P$1_P$166") (pintype "power_in"))
      (node (ref "P1") (pin "P$167") (pinfunction "P$1_P$167") (pintype "power_in"))
      (node (ref "P1") (pin "P$168") (pinfunction "P$1_P$168") (pintype "power_in"))
      (node (ref "P1") (pin "P$169") (pinfunction "P$1_P$169") (pintype "power_in"))
      (node (ref "P1") (pin "P$17") (pinfunction "P$1_P$17") (pintype "power_in"))
      (node (ref "P1") (pin "P$170") (pinfunction "P$1_P$170") (pintype "power_in"))
      (node (ref "P1") (pin "P$171") (pinfunction "P$1_P$171") (pintype "power_in"))
      (node (ref "P1") (pin "P$172") (pinfunction "P$1_P$172") (pintype "power_in"))
      (node (ref "P1") (pin "P$173") (pinfunction "P$1_P$173") (pintype "power_in"))
      (node (ref "P1") (pin "P$174") (pinfunction "P$1_P$174") (pintype "power_in"))
      (node (ref "P1") (pin "P$175") (pinfunction "P$1_P$175") (pintype "power_in"))
      (node (ref "P1") (pin "P$176") (pinfunction "P$1_P$176") (pintype "power_in"))
      (node (ref "P1") (pin "P$177") (pinfunction "P$1_P$177") (pintype "power_in"))
      (node (ref "P1") (pin "P$178") (pinfunction "P$1_P$178") (pintype "power_in"))
      (node (ref "P1") (pin "P$179") (pinfunction "P$1_P$179") (pintype "power_in"))
      (node (ref "P1") (pin "P$18") (pinfunction "P$1_P$18") (pintype "power_in"))
      (node (ref "P1") (pin "P$180") (pinfunction "P$1_P$180") (pintype "power_in"))
      (node (ref "P1") (pin "P$181") (pinfunction "P$1_P$181") (pintype "power_in"))
      (node (ref "P1") (pin "P$182") (pinfunction "P$1_P$182") (pintype "power_in"))
      (node (ref "P1") (pin "P$183") (pinfunction "P$1_P$183") (pintype "power_in"))
      (node (ref "P1") (pin "P$184") (pinfunction "P$1_P$184") (pintype "power_in"))
      (node (ref "P1") (pin "P$185") (pinfunction "P$1_P$185") (pintype "power_in"))
      (node (ref "P1") (pin "P$186") (pinfunction "P$1_P$186") (pintype "power_in"))
      (node (ref "P1") (pin "P$188") (pinfunction "P$1_P$188") (pintype "power_in"))
      (node (ref "P1") (pin "P$189") (pinfunction "P$1_P$189") (pintype "power_in"))
      (node (ref "P1") (pin "P$19") (pinfunction "P$1_P$19") (pintype "power_in"))
      (node (ref "P1") (pin "P$190") (pinfunction "P$1_P$190") (pintype "power_in"))
      (node (ref "P1") (pin "P$191") (pinfunction "P$1_P$191") (pintype "power_in"))
      (node (ref "P1") (pin "P$192") (pinfunction "P$1_P$192") (pintype "power_in"))
      (node (ref "P1") (pin "P$193") (pinfunction "P$1_P$193") (pintype "power_in"))
      (node (ref "P1") (pin "P$194") (pinfunction "P$1_P$194") (pintype "power_in"))
      (node (ref "P1") (pin "P$195") (pinfunction "P$1_P$195") (pintype "power_in"))
      (node (ref "P1") (pin "P$196") (pinfunction "P$1_P$196") (pintype "power_in"))
      (node (ref "P1") (pin "P$197") (pinfunction "P$1_P$197") (pintype "power_in"))
      (node (ref "P1") (pin "P$198") (pinfunction "P$1_P$198") (pintype "power_in"))
      (node (ref "P1") (pin "P$199") (pinfunction "P$1_P$199") (pintype "power_in"))
      (node (ref "P1") (pin "P$20") (pinfunction "P$1_P$20") (pintype "power_in"))
      (node (ref "P1") (pin "P$200") (pinfunction "P$1_P$200") (pintype "power_in"))
      (node (ref "P1") (pin "P$201") (pinfunction "P$1_P$201") (pintype "power_in"))
      (node (ref "P1") (pin "P$202") (pinfunction "P$1_P$202") (pintype "power_in"))
      (node (ref "P1") (pin "P$203") (pinfunction "P$1_P$203") (pintype "power_in"))
      (node (ref "P1") (pin "P$204") (pinfunction "P$1_P$204") (pintype "power_in"))
      (node (ref "P1") (pin "P$205") (pinfunction "P$1_P$205") (pintype "power_in"))
      (node (ref "P1") (pin "P$206") (pinfunction "P$1_P$206") (pintype "power_in"))
      (node (ref "P1") (pin "P$207") (pinfunction "P$1_P$207") (pintype "power_in"))
      (node (ref "P1") (pin "P$208") (pinfunction "P$1_P$208") (pintype "power_in"))
      (node (ref "P1") (pin "P$209") (pinfunction "P$1_P$209") (pintype "power_in"))
      (node (ref "P1") (pin "P$21") (pinfunction "P$1_P$21") (pintype "power_in"))
      (node (ref "P1") (pin "P$210") (pinfunction "P$1_P$210") (pintype "power_in"))
      (node (ref "P1") (pin "P$211") (pinfunction "P$1_P$211") (pintype "power_in"))
      (node (ref "P1") (pin "P$212") (pinfunction "P$1_P$212") (pintype "power_in"))
      (node (ref "P1") (pin "P$213") (pinfunction "P$1_P$213") (pintype "power_in"))
      (node (ref "P1") (pin "P$214") (pinfunction "P$1_P$214") (pintype "power_in"))
      (node (ref "P1") (pin "P$215") (pinfunction "P$1_P$215") (pintype "power_in"))
      (node (ref "P1") (pin "P$216") (pinfunction "P$1_P$216") (pintype "power_in"))
      (node (ref "P1") (pin "P$217") (pinfunction "P$1_P$217") (pintype "power_in"))
      (node (ref "P1") (pin "P$218") (pinfunction "P$1_P$218") (pintype "power_in"))
      (node (ref "P1") (pin "P$219") (pinfunction "P$1_P$219") (pintype "power_in"))
      (node (ref "P1") (pin "P$22") (pinfunction "P$1_P$22") (pintype "power_in"))
      (node (ref "P1") (pin "P$220") (pinfunction "P$1_P$220") (pintype "power_in"))
      (node (ref "P1") (pin "P$221") (pinfunction "P$1_P$221") (pintype "power_in"))
      (node (ref "P1") (pin "P$222") (pinfunction "P$1_P$222") (pintype "power_in"))
      (node (ref "P1") (pin "P$223") (pinfunction "P$1_P$223") (pintype "power_in"))
      (node (ref "P1") (pin "P$23") (pinfunction "P$1_P$23") (pintype "power_in"))
      (node (ref "P1") (pin "P$24") (pinfunction "P$1_P$24") (pintype "power_in"))
      (node (ref "P1") (pin "P$25") (pinfunction "P$1_P$25") (pintype "power_in"))
      (node (ref "P1") (pin "P$26") (pinfunction "P$1_P$26") (pintype "power_in"))
      (node (ref "P1") (pin "P$27") (pinfunction "P$1_P$27") (pintype "power_in"))
      (node (ref "P1") (pin "P$28") (pinfunction "P$1_P$28") (pintype "power_in"))
      (node (ref "P1") (pin "P$29") (pinfunction "P$1_P$29") (pintype "power_in"))
      (node (ref "P1") (pin "P$30") (pinfunction "P$1_P$30") (pintype "power_in"))
      (node (ref "P1") (pin "P$31") (pinfunction "P$1_P$31") (pintype "power_in"))
      (node (ref "P1") (pin "P$32") (pinfunction "P$1_P$32") (pintype "power_in"))
      (node (ref "P1") (pin "P$33") (pinfunction "P$1_P$33") (pintype "power_in"))
      (node (ref "P1") (pin "P$34") (pinfunction "P$1_P$34") (pintype "power_in"))
      (node (ref "P1") (pin "P$35") (pinfunction "P$1_P$35") (pintype "power_in"))
      (node (ref "P1") (pin "P$36") (pinfunction "P$1_P$36") (pintype "power_in"))
      (node (ref "P1") (pin "P$37") (pinfunction "P$1_P$37") (pintype "power_in"))
      (node (ref "P1") (pin "P$38") (pinfunction "P$1_P$38") (pintype "power_in"))
      (node (ref "P1") (pin "P$39") (pinfunction "P$1_P$39") (pintype "power_in"))
      (node (ref "P1") (pin "P$40") (pinfunction "P$1_P$40") (pintype "power_in"))
      (node (ref "P1") (pin "P$41") (pinfunction "P$1_P$41") (pintype "power_in"))
      (node (ref "P1") (pin "P$42") (pinfunction "P$1_P$42") (pintype "power_in"))
      (node (ref "P1") (pin "P$43") (pinfunction "P$1_P$43") (pintype "power_in"))
      (node (ref "P1") (pin "P$44") (pinfunction "P$1_P$44") (pintype "power_in"))
      (node (ref "P1") (pin "P$45") (pinfunction "P$1_P$45") (pintype "power_in"))
      (node (ref "P1") (pin "P$46") (pinfunction "P$1_P$46") (pintype "power_in"))
      (node (ref "P1") (pin "P$47") (pinfunction "P$1_P$47") (pintype "power_in"))
      (node (ref "P1") (pin "P$48") (pinfunction "P$1_P$48") (pintype "power_in"))
      (node (ref "P1") (pin "P$49") (pinfunction "P$1_P$49") (pintype "power_in"))
      (node (ref "P1") (pin "P$5") (pinfunction "P$1_P$5") (pintype "power_in"))
      (node (ref "P1") (pin "P$50") (pinfunction "P$1_P$50") (pintype "power_in"))
      (node (ref "P1") (pin "P$51") (pinfunction "P$1_P$51") (pintype "power_in"))
      (node (ref "P1") (pin "P$52") (pinfunction "P$1_P$52") (pintype "power_in"))
      (node (ref "P1") (pin "P$53") (pinfunction "P$1_P$53") (pintype "power_in"))
      (node (ref "P1") (pin "P$54") (pinfunction "P$1_P$54") (pintype "power_in"))
      (node (ref "P1") (pin "P$55") (pinfunction "P$1_P$55") (pintype "power_in"))
      (node (ref "P1") (pin "P$56") (pinfunction "P$1_P$56") (pintype "power_in"))
      (node (ref "P1") (pin "P$57") (pinfunction "P$1_P$57") (pintype "power_in"))
      (node (ref "P1") (pin "P$58") (pinfunction "P$1_P$58") (pintype "power_in"))
      (node (ref "P1") (pin "P$59") (pinfunction "P$1_P$59") (pintype "power_in"))
      (node (ref "P1") (pin "P$6") (pinfunction "P$1_P$6") (pintype "power_in"))
      (node (ref "P1") (pin "P$60") (pinfunction "P$1_P$60") (pintype "power_in"))
      (node (ref "P1") (pin "P$61") (pinfunction "P$1_P$61") (pintype "power_in"))
      (node (ref "P1") (pin "P$62") (pinfunction "P$1_P$62") (pintype "power_in"))
      (node (ref "P1") (pin "P$63") (pinfunction "P$1_P$63") (pintype "power_in"))
      (node (ref "P1") (pin "P$64") (pinfunction "P$1_P$64") (pintype "power_in"))
      (node (ref "P1") (pin "P$65") (pinfunction "P$1_P$65") (pintype "power_in"))
      (node (ref "P1") (pin "P$66") (pinfunction "P$1_P$66") (pintype "power_in"))
      (node (ref "P1") (pin "P$67") (pinfunction "P$1_P$67") (pintype "power_in"))
      (node (ref "P1") (pin "P$68") (pinfunction "P$1_P$68") (pintype "power_in"))
      (node (ref "P1") (pin "P$69") (pinfunction "P$1_P$69") (pintype "power_in"))
      (node (ref "P1") (pin "P$7") (pinfunction "P$1_P$7") (pintype "power_in"))
      (node (ref "P1") (pin "P$70") (pinfunction "P$1_P$70") (pintype "power_in"))
      (node (ref "P1") (pin "P$71") (pinfunction "P$1_P$71") (pintype "power_in"))
      (node (ref "P1") (pin "P$72") (pinfunction "P$1_P$72") (pintype "power_in"))
      (node (ref "P1") (pin "P$73") (pinfunction "P$1_P$73") (pintype "power_in"))
      (node (ref "P1") (pin "P$74") (pinfunction "P$1_P$74") (pintype "power_in"))
      (node (ref "P1") (pin "P$75") (pinfunction "P$1_P$75") (pintype "power_in"))
      (node (ref "P1") (pin "P$76") (pinfunction "P$1_P$76") (pintype "power_in"))
      (node (ref "P1") (pin "P$77") (pinfunction "P$1_P$77") (pintype "power_in"))
      (node (ref "P1") (pin "P$78") (pinfunction "P$1_P$78") (pintype "power_in"))
      (node (ref "P1") (pin "P$79") (pinfunction "P$1_P$79") (pintype "power_in"))
      (node (ref "P1") (pin "P$8") (pinfunction "P$1_P$8") (pintype "power_in"))
      (node (ref "P1") (pin "P$80") (pinfunction "P$1_P$80") (pintype "power_in"))
      (node (ref "P1") (pin "P$81") (pinfunction "P$1_P$81") (pintype "power_in"))
      (node (ref "P1") (pin "P$82") (pinfunction "P$1_P$82") (pintype "power_in"))
      (node (ref "P1") (pin "P$83") (pinfunction "P$1_P$83") (pintype "power_in"))
      (node (ref "P1") (pin "P$84") (pinfunction "P$1_P$84") (pintype "power_in"))
      (node (ref "P1") (pin "P$85") (pinfunction "P$1_P$85") (pintype "power_in"))
      (node (ref "P1") (pin "P$86") (pinfunction "P$1_P$86") (pintype "power_in"))
      (node (ref "P1") (pin "P$87") (pinfunction "P$1_P$87") (pintype "power_in"))
      (node (ref "P1") (pin "P$88") (pinfunction "P$1_P$88") (pintype "power_in"))
      (node (ref "P1") (pin "P$89") (pinfunction "P$1_P$89") (pintype "power_in"))
      (node (ref "P1") (pin "P$9") (pinfunction "P$1_P$9") (pintype "power_in"))
      (node (ref "P1") (pin "P$90") (pinfunction "P$1_P$90") (pintype "power_in"))
      (node (ref "P1") (pin "P$91") (pinfunction "P$1_P$91") (pintype "power_in"))
      (node (ref "P1") (pin "P$92") (pinfunction "P$1_P$92") (pintype "power_in"))
      (node (ref "P1") (pin "P$93") (pinfunction "P$1_P$93") (pintype "power_in"))
      (node (ref "P1") (pin "P$94") (pinfunction "P$1_P$94") (pintype "power_in"))
      (node (ref "P1") (pin "P$95") (pinfunction "P$1_P$95") (pintype "power_in"))
      (node (ref "P1") (pin "P$96") (pinfunction "P$1_P$96") (pintype "power_in"))
      (node (ref "P1") (pin "P$97") (pinfunction "P$1_P$97") (pintype "power_in"))
      (node (ref "P1") (pin "P$98") (pinfunction "P$1_P$98") (pintype "power_in"))
      (node (ref "P1") (pin "P$99") (pinfunction "P$1_P$99") (pintype "power_in"))
    )
    (net (code "3") (name "/P2") (class "Default")
      (node (ref "JP1") (pin "P$3") (pinfunction "2_P$3") (pintype "bidirectional"))
      (node (ref "P2") (pin "P$10") (pinfunction "P$1_P$10") (pintype "power_in"))
      (node (ref "P2") (pin "P$100") (pinfunction "P$1_P$100") (pintype "power_in"))
      (node (ref "P2") (pin "P$101") (pinfunction "P$1_P$101") (pintype "power_in"))
      (node (ref "P2") (pin "P$102") (pinfunction "P$1_P$102") (pintype "power_in"))
      (node (ref "P2") (pin "P$103") (pinfunction "P$1_P$103") (pintype "power_in"))
      (node (ref "P2") (pin "P$104") (pinfunction "P$1_P$104") (pintype "power_in"))
      (node (ref "P2") (pin "P$105") (pinfunction "P$1_P$105") (pintype "power_in"))
      (node (ref "P2") (pin "P$106") (pinfunction "P$1_P$106") (pintype "power_in"))
      (node (ref "P2") (pin "P$107") (pinfunction "P$1_P$107") (pintype "power_in"))
      (node (ref "P2") (pin "P$108") (pinfunction "P$1_P$108") (pintype "power_in"))
      (node (ref "P2") (pin "P$109") (pinfunction "P$1_P$109") (pintype "power_in"))
      (node (ref "P2") (pin "P$11") (pinfunction "P$1_P$11") (pintype "power_in"))
      (node (ref "P2") (pin "P$110") (pinfunction "P$1_P$110") (pintype "power_in"))
      (node (ref "P2") (pin "P$111") (pinfunction "P$1_P$111") (pintype "power_in"))
      (node (ref "P2") (pin "P$112") (pinfunction "P$1_P$112") (pintype "power_in"))
      (node (ref "P2") (pin "P$113") (pinfunction "P$1_P$113") (pintype "power_in"))
      (node (ref "P2") (pin "P$114") (pinfunction "P$1_P$114") (pintype "power_in"))
      (node (ref "P2") (pin "P$116") (pinfunction "P$1_P$116") (pintype "power_in"))
      (node (ref "P2") (pin "P$117") (pinfunction "P$1_P$117") (pintype "power_in"))
      (node (ref "P2") (pin "P$118") (pinfunction "P$1_P$118") (pintype "power_in"))
      (node (ref "P2") (pin "P$119") (pinfunction "P$1_P$119") (pintype "power_in"))
      (node (ref "P2") (pin "P$12") (pinfunction "P$1_P$12") (pintype "power_in"))
      (node (ref "P2") (pin "P$120") (pinfunction "P$1_P$120") (pintype "power_in"))
      (node (ref "P2") (pin "P$121") (pinfunction "P$1_P$121") (pintype "power_in"))
      (node (ref "P2") (pin "P$122") (pinfunction "P$1_P$122") (pintype "power_in"))
      (node (ref "P2") (pin "P$123") (pinfunction "P$1_P$123") (pintype "power_in"))
      (node (ref "P2") (pin "P$124") (pinfunction "P$1_P$124") (pintype "power_in"))
      (node (ref "P2") (pin "P$125") (pinfunction "P$1_P$125") (pintype "power_in"))
      (node (ref "P2") (pin "P$126") (pinfunction "P$1_P$126") (pintype "power_in"))
      (node (ref "P2") (pin "P$127") (pinfunction "P$1_P$127") (pintype "power_in"))
      (node (ref "P2") (pin "P$128") (pinfunction "P$1_P$128") (pintype "power_in"))
      (node (ref "P2") (pin "P$129") (pinfunction "P$1_P$129") (pintype "power_in"))
      (node (ref "P2") (pin "P$13") (pinfunction "P$1_P$13") (pintype "power_in"))
      (node (ref "P2") (pin "P$130") (pinfunction "P$1_P$130") (pintype "power_in"))
      (node (ref "P2") (pin "P$131") (pinfunction "P$1_P$131") (pintype "power_in"))
      (node (ref "P2") (pin "P$132") (pinfunction "P$1_P$132") (pintype "power_in"))
      (node (ref "P2") (pin "P$133") (pinfunction "P$1_P$133") (pintype "power_in"))
      (node (ref "P2") (pin "P$134") (pinfunction "P$1_P$134") (pintype "power_in"))
      (node (ref "P2") (pin "P$135") (pinfunction "P$1_P$135") (pintype "power_in"))
      (node (ref "P2") (pin "P$136") (pinfunction "P$1_P$136") (pintype "power_in"))
      (node (ref "P2") (pin "P$137") (pinfunction "P$1_P$137") (pintype "power_in"))
      (node (ref "P2") (pin "P$138") (pinfunction "P$1_P$138") (pintype "power_in"))
      (node (ref "P2") (pin "P$139") (pinfunction "P$1_P$139") (pintype "power_in"))
      (node (ref "P2") (pin "P$14") (pinfunction "P$1_P$14") (pintype "power_in"))
      (node (ref "P2") (pin "P$140") (pinfunction "P$1_P$140") (pintype "power_in"))
      (node (ref "P2") (pin "P$141") (pinfunction "P$1_P$141") (pintype "power_in"))
      (node (ref "P2") (pin "P$142") (pinfunction "P$1_P$142") (pintype "power_in"))
      (node (ref "P2") (pin "P$143") (pinfunction "P$1_P$143") (pintype "power_in"))
      (node (ref "P2") (pin "P$144") (pinfunction "P$1_P$144") (pintype "power_in"))
      (node (ref "P2") (pin "P$145") (pinfunction "P$1_P$145") (pintype "power_in"))
      (node (ref "P2") (pin "P$146") (pinfunction "P$1_P$146") (pintype "power_in"))
      (node (ref "P2") (pin "P$147") (pinfunction "P$1_P$147") (pintype "power_in"))
      (node (ref "P2") (pin "P$148") (pinfunction "P$1_P$148") (pintype "power_in"))
      (node (ref "P2") (pin "P$149") (pinfunction "P$1_P$149") (pintype "power_in"))
      (node (ref "P2") (pin "P$15") (pinfunction "P$1_P$15") (pintype "power_in"))
      (node (ref "P2") (pin "P$150") (pinfunction "P$1_P$150") (pintype "power_in"))
      (node (ref "P2") (pin "P$151") (pinfunction "P$1_P$151") (pintype "power_in"))
      (node (ref "P2") (pin "P$153") (pinfunction "P$1_P$153") (pintype "power_in"))
      (node (ref "P2") (pin "P$154") (pinfunction "P$1_P$154") (pintype "power_in"))
      (node (ref "P2") (pin "P$155") (pinfunction "P$1_P$155") (pintype "power_in"))
      (node (ref "P2") (pin "P$156") (pinfunction "P$1_P$156") (pintype "power_in"))
      (node (ref "P2") (pin "P$157") (pinfunction "P$1_P$157") (pintype "power_in"))
      (node (ref "P2") (pin "P$158") (pinfunction "P$1_P$158") (pintype "power_in"))
      (node (ref "P2") (pin "P$159") (pinfunction "P$1_P$159") (pintype "power_in"))
      (node (ref "P2") (pin "P$16") (pinfunction "P$1_P$16") (pintype "power_in"))
      (node (ref "P2") (pin "P$160") (pinfunction "P$1_P$160") (pintype "power_in"))
      (node (ref "P2") (pin "P$161") (pinfunction "P$1_P$161") (pintype "power_in"))
      (node (ref "P2") (pin "P$162") (pinfunction "P$1_P$162") (pintype "power_in"))
      (node (ref "P2") (pin "P$163") (pinfunction "P$1_P$163") (pintype "power_in"))
      (node (ref "P2") (pin "P$164") (pinfunction "P$1_P$164") (pintype "power_in"))
      (node (ref "P2") (pin "P$165") (pinfunction "P$1_P$165") (pintype "power_in"))
      (node (ref "P2") (pin "P$166") (pinfunction "P$1_P$166") (pintype "power_in"))
      (node (ref "P2") (pin "P$167") (pinfunction "P$1_P$167") (pintype "power_in"))
      (node (ref "P2") (pin "P$168") (pinfunction "P$1_P$168") (pintype "power_in"))
      (node (ref "P2") (pin "P$169") (pinfunction "P$1_P$169") (pintype "power_in"))
      (node (ref "P2") (pin "P$17") (pinfunction "P$1_P$17") (pintype "power_in"))
      (node (ref "P2") (pin "P$170") (pinfunction "P$1_P$170") (pintype "power_in"))
      (node (ref "P2") (pin "P$171") (pinfunction "P$1_P$171") (pintype "power_in"))
      (node (ref "P2") (pin "P$172") (pinfunction "P$1_P$172") (pintype "power_in"))
      (node (ref "P2") (pin "P$173") (pinfunction "P$1_P$173") (pintype "power_in"))
      (node (ref "P2") (pin "P$174") (pinfunction "P$1_P$174") (pintype "power_in"))
      (node (ref "P2") (pin "P$175") (pinfunction "P$1_P$175") (pintype "power_in"))
      (node (ref "P2") (pin "P$176") (pinfunction "P$1_P$176") (pintype "power_in"))
      (node (ref "P2") (pin "P$177") (pinfunction "P$1_P$177") (pintype "power_in"))
      (node (ref "P2") (pin "P$178") (pinfunction "P$1_P$178") (pintype "power_in"))
      (node (ref "P2") (pin "P$179") (pinfunction "P$1_P$179") (pintype "power_in"))
      (node (ref "P2") (pin "P$18") (pinfunction "P$1_P$18") (pintype "power_in"))
      (node (ref "P2") (pin "P$180") (pinfunction "P$1_P$180") (pintype "power_in"))
      (node (ref "P2") (pin "P$181") (pinfunction "P$1_P$181") (pintype "power_in"))
      (node (ref "P2") (pin "P$182") (pinfunction "P$1_P$182") (pintype "power_in"))
      (node (ref "P2") (pin "P$183") (pinfunction "P$1_P$183") (pintype "power_in"))
      (node (ref "P2") (pin "P$184") (pinfunction "P$1_P$184") (pintype "power_in"))
      (node (ref "P2") (pin "P$185") (pinfunction "P$1_P$185") (pintype "power_in"))
      (node (ref "P2") (pin "P$186") (pinfunction "P$1_P$186") (pintype "power_in"))
      (node (ref "P2") (pin "P$187") (pinfunction "P$1_P$187") (pintype "power_in"))
      (node (ref "P2") (pin "P$188") (pinfunction "P$1_P$188") (pintype "power_in"))
      (node (ref "P2") (pin "P$19") (pinfunction "P$1_P$19") (pintype "power_in"))
      (node (ref "P2") (pin "P$190") (pinfunction "P$1_P$190") (pintype "power_in"))
      (node (ref "P2") (pin "P$191") (pinfunction "P$1_P$191") (pintype "power_in"))
      (node (ref "P2") (pin "P$192") (pinfunction "P$1_P$192") (pintype "power_in"))
      (node (ref "P2") (pin "P$193") (pinfunction "P$1_P$193") (pintype "power_in"))
      (node (ref "P2") (pin "P$194") (pinfunction "P$1_P$194") (pintype "power_in"))
      (node (ref "P2") (pin "P$195") (pinfunction "P$1_P$195") (pintype "power_in"))
      (node (ref "P2") (pin "P$196") (pinfunction "P$1_P$196") (pintype "power_in"))
      (node (ref "P2") (pin "P$197") (pinfunction "P$1_P$197") (pintype "power_in"))
      (node (ref "P2") (pin "P$198") (pinfunction "P$1_P$198") (pintype "power_in"))
      (node (ref "P2") (pin "P$199") (pinfunction "P$1_P$199") (pintype "power_in"))
      (node (ref "P2") (pin "P$20") (pinfunction "P$1_P$20") (pintype "power_in"))
      (node (ref "P2") (pin "P$200") (pinfunction "P$1_P$200") (pintype "power_in"))
      (node (ref "P2") (pin "P$201") (pinfunction "P$1_P$201") (pintype "power_in"))
      (node (ref "P2") (pin "P$202") (pinfunction "P$1_P$202") (pintype "power_in"))
      (node (ref "P2") (pin "P$203") (pinfunction "P$1_P$203") (pintype "power_in"))
      (node (ref "P2") (pin "P$204") (pinfunction "P$1_P$204") (pintype "power_in"))
      (node (ref "P2") (pin "P$205") (pinfunction "P$1_P$205") (pintype "power_in"))
      (node (ref "P2") (pin "P$206") (pinfunction "P$1_P$206") (pintype "power_in"))
      (node (ref "P2") (pin "P$207") (pinfunction "P$1_P$207") (pintype "power_in"))
      (node (ref "P2") (pin "P$208") (pinfunction "P$1_P$208") (pintype "power_in"))
      (node (ref "P2") (pin "P$209") (pinfunction "P$1_P$209") (pintype "power_in"))
      (node (ref "P2") (pin "P$21") (pinfunction "P$1_P$21") (pintype "power_in"))
      (node (ref "P2") (pin "P$210") (pinfunction "P$1_P$210") (pintype "power_in"))
      (node (ref "P2") (pin "P$211") (pinfunction "P$1_P$211") (pintype "power_in"))
      (node (ref "P2") (pin "P$212") (pinfunction "P$1_P$212") (pintype "power_in"))
      (node (ref "P2") (pin "P$213") (pinfunction "P$1_P$213") (pintype "power_in"))
      (node (ref "P2") (pin "P$214") (pinfunction "P$1_P$214") (pintype "power_in"))
      (node (ref "P2") (pin "P$215") (pinfunction "P$1_P$215") (pintype "power_in"))
      (node (ref "P2") (pin "P$216") (pinfunction "P$1_P$216") (pintype "power_in"))
      (node (ref "P2") (pin "P$217") (pinfunction "P$1_P$217") (pintype "power_in"))
      (node (ref "P2") (pin "P$218") (pinfunction "P$1_P$218") (pintype "power_in"))
      (node (ref "P2") (pin "P$219") (pinfunction "P$1_P$219") (pintype "power_in"))
      (node (ref "P2") (pin "P$22") (pinfunction "P$1_P$22") (pintype "power_in"))
      (node (ref "P2") (pin "P$220") (pinfunction "P$1_P$220") (pintype "power_in"))
      (node (ref "P2") (pin "P$221") (pinfunction "P$1_P$221") (pintype "power_in"))
      (node (ref "P2") (pin "P$222") (pinfunction "P$1_P$222") (pintype "power_in"))
      (node (ref "P2") (pin "P$223") (pinfunction "P$1_P$223") (pintype "power_in"))
      (node (ref "P2") (pin "P$224") (pinfunction "P$1_P$224") (pintype "power_in"))
      (node (ref "P2") (pin "P$225") (pinfunction "P$1_P$225") (pintype "power_in"))
      (node (ref "P2") (pin "P$23") (pinfunction "P$1_P$23") (pintype "power_in"))
      (node (ref "P2") (pin "P$24") (pinfunction "P$1_P$24") (pintype "power_in"))
      (node (ref "P2") (pin "P$25") (pinfunction "P$1_P$25") (pintype "power_in"))
      (node (ref "P2") (pin "P$26") (pinfunction "P$1_P$26") (pintype "power_in"))
      (node (ref "P2") (pin "P$27") (pinfunction "P$1_P$27") (pintype "power_in"))
      (node (ref "P2") (pin "P$28") (pinfunction "P$1_P$28") (pintype "power_in"))
      (node (ref "P2") (pin "P$29") (pinfunction "P$1_P$29") (pintype "power_in"))
      (node (ref "P2") (pin "P$30") (pinfunction "P$1_P$30") (pintype "power_in"))
      (node (ref "P2") (pin "P$31") (pinfunction "P$1_P$31") (pintype "power_in"))
      (node (ref "P2") (pin "P$32") (pinfunction "P$1_P$32") (pintype "power_in"))
      (node (ref "P2") (pin "P$33") (pinfunction "P$1_P$33") (pintype "power_in"))
      (node (ref "P2") (pin "P$34") (pinfunction "P$1_P$34") (pintype "power_in"))
      (node (ref "P2") (pin "P$35") (pinfunction "P$1_P$35") (pintype "power_in"))
      (node (ref "P2") (pin "P$36") (pinfunction "P$1_P$36") (pintype "power_in"))
      (node (ref "P2") (pin "P$37") (pinfunction "P$1_P$37") (pintype "power_in"))
      (node (ref "P2") (pin "P$38") (pinfunction "P$1_P$38") (pintype "power_in"))
      (node (ref "P2") (pin "P$39") (pinfunction "P$1_P$39") (pintype "power_in"))
      (node (ref "P2") (pin "P$40") (pinfunction "P$1_P$40") (pintype "power_in"))
      (node (ref "P2") (pin "P$42") (pinfunction "P$1_P$42") (pintype "power_in"))
      (node (ref "P2") (pin "P$43") (pinfunction "P$1_P$43") (pintype "power_in"))
      (node (ref "P2") (pin "P$44") (pinfunction "P$1_P$44") (pintype "power_in"))
      (node (ref "P2") (pin "P$45") (pinfunction "P$1_P$45") (pintype "power_in"))
      (node (ref "P2") (pin "P$46") (pinfunction "P$1_P$46") (pintype "power_in"))
      (node (ref "P2") (pin "P$47") (pinfunction "P$1_P$47") (pintype "power_in"))
      (node (ref "P2") (pin "P$48") (pinfunction "P$1_P$48") (pintype "power_in"))
      (node (ref "P2") (pin "P$49") (pinfunction "P$1_P$49") (pintype "power_in"))
      (node (ref "P2") (pin "P$5") (pinfunction "P$1_P$5") (pintype "power_in"))
      (node (ref "P2") (pin "P$50") (pinfunction "P$1_P$50") (pintype "power_in"))
      (node (ref "P2") (pin "P$51") (pinfunction "P$1_P$51") (pintype "power_in"))
      (node (ref "P2") (pin "P$52") (pinfunction "P$1_P$52") (pintype "power_in"))
      (node (ref "P2") (pin "P$53") (pinfunction "P$1_P$53") (pintype "power_in"))
      (node (ref "P2") (pin "P$54") (pinfunction "P$1_P$54") (pintype "power_in"))
      (node (ref "P2") (pin "P$55") (pinfunction "P$1_P$55") (pintype "power_in"))
      (node (ref "P2") (pin "P$56") (pinfunction "P$1_P$56") (pintype "power_in"))
      (node (ref "P2") (pin "P$57") (pinfunction "P$1_P$57") (pintype "power_in"))
      (node (ref "P2") (pin "P$58") (pinfunction "P$1_P$58") (pintype "power_in"))
      (node (ref "P2") (pin "P$59") (pinfunction "P$1_P$59") (pintype "power_in"))
      (node (ref "P2") (pin "P$6") (pinfunction "P$1_P$6") (pintype "power_in"))
      (node (ref "P2") (pin "P$60") (pinfunction "P$1_P$60") (pintype "power_in"))
      (node (ref "P2") (pin "P$61") (pinfunction "P$1_P$61") (pintype "power_in"))
      (node (ref "P2") (pin "P$62") (pinfunction "P$1_P$62") (pintype "power_in"))
      (node (ref "P2") (pin "P$63") (pinfunction "P$1_P$63") (pintype "power_in"))
      (node (ref "P2") (pin "P$64") (pinfunction "P$1_P$64") (pintype "power_in"))
      (node (ref "P2") (pin "P$65") (pinfunction "P$1_P$65") (pintype "power_in"))
      (node (ref "P2") (pin "P$66") (pinfunction "P$1_P$66") (pintype "power_in"))
      (node (ref "P2") (pin "P$67") (pinfunction "P$1_P$67") (pintype "power_in"))
      (node (ref "P2") (pin "P$68") (pinfunction "P$1_P$68") (pintype "power_in"))
      (node (ref "P2") (pin "P$69") (pinfunction "P$1_P$69") (pintype "power_in"))
      (node (ref "P2") (pin "P$7") (pinfunction "P$1_P$7") (pintype "power_in"))
      (node (ref "P2") (pin "P$70") (pinfunction "P$1_P$70") (pintype "power_in"))
      (node (ref "P2") (pin "P$71") (pinfunction "P$1_P$71") (pintype "power_in"))
      (node (ref "P2") (pin "P$72") (pinfunction "P$1_P$72") (pintype "power_in"))
      (node (ref "P2") (pin "P$73") (pinfunction "P$1_P$73") (pintype "power_in"))
      (node (ref "P2") (pin "P$74") (pinfunction "P$1_P$74") (pintype "power_in"))
      (node (ref "P2") (pin "P$75") (pinfunction "P$1_P$75") (pintype "power_in"))
      (node (ref "P2") (pin "P$76") (pinfunction "P$1_P$76") (pintype "power_in"))
      (node (ref "P2") (pin "P$77") (pinfunction "P$1_P$77") (pintype "power_in"))
      (node (ref "P2") (pin "P$79") (pinfunction "P$1_P$79") (pintype "power_in"))
      (node (ref "P2") (pin "P$8") (pinfunction "P$1_P$8") (pintype "power_in"))
      (node (ref "P2") (pin "P$80") (pinfunction "P$1_P$80") (pintype "power_in"))
      (node (ref "P2") (pin "P$81") (pinfunction "P$1_P$81") (pintype "power_in"))
      (node (ref "P2") (pin "P$82") (pinfunction "P$1_P$82") (pintype "power_in"))
      (node (ref "P2") (pin "P$83") (pinfunction "P$1_P$83") (pintype "power_in"))
      (node (ref "P2") (pin "P$84") (pinfunction "P$1_P$84") (pintype "power_in"))
      (node (ref "P2") (pin "P$85") (pinfunction "P$1_P$85") (pintype "power_in"))
      (node (ref "P2") (pin "P$86") (pinfunction "P$1_P$86") (pintype "power_in"))
      (node (ref "P2") (pin "P$87") (pinfunction "P$1_P$87") (pintype "power_in"))
      (node (ref "P2") (pin "P$88") (pinfunction "P$1_P$88") (pintype "power_in"))
      (node (ref "P2") (pin "P$89") (pinfunction "P$1_P$89") (pintype "power_in"))
      (node (ref "P2") (pin "P$9") (pinfunction "P$1_P$9") (pintype "power_in"))
      (node (ref "P2") (pin "P$90") (pinfunction "P$1_P$90") (pintype "power_in"))
      (node (ref "P2") (pin "P$91") (pinfunction "P$1_P$91") (pintype "power_in"))
      (node (ref "P2") (pin "P$92") (pinfunction "P$1_P$92") (pintype "power_in"))
      (node (ref "P2") (pin "P$93") (pinfunction "P$1_P$93") (pintype "power_in"))
      (node (ref "P2") (pin "P$94") (pinfunction "P$1_P$94") (pintype "power_in"))
      (node (ref "P2") (pin "P$95") (pinfunction "P$1_P$95") (pintype "power_in"))
      (node (ref "P2") (pin "P$96") (pinfunction "P$1_P$96") (pintype "power_in"))
      (node (ref "P2") (pin "P$97") (pinfunction "P$1_P$97") (pintype "power_in"))
      (node (ref "P2") (pin "P$98") (pinfunction "P$1_P$98") (pintype "power_in"))
      (node (ref "P2") (pin "P$99") (pinfunction "P$1_P$99") (pintype "power_in"))
    )
    (net (code "4") (name "/P3") (class "Default")
      (node (ref "JP1") (pin "P$4") (pinfunction "3_P$4") (pintype "bidirectional"))
      (node (ref "P3") (pin "P$10") (pinfunction "P$1_P$10") (pintype "power_in"))
      (node (ref "P3") (pin "P$100") (pinfunction "P$1_P$100") (pintype "power_in"))
      (node (ref "P3") (pin "P$101") (pinfunction "P$1_P$101") (pintype "power_in"))
      (node (ref "P3") (pin "P$102") (pinfunction "P$1_P$102") (pintype "power_in"))
      (node (ref "P3") (pin "P$103") (pinfunction "P$1_P$103") (pintype "power_in"))
      (node (ref "P3") (pin "P$104") (pinfunction "P$1_P$104") (pintype "power_in"))
      (node (ref "P3") (pin "P$105") (pinfunction "P$1_P$105") (pintype "power_in"))
      (node (ref "P3") (pin "P$106") (pinfunction "P$1_P$106") (pintype "power_in"))
      (node (ref "P3") (pin "P$107") (pinfunction "P$1_P$107") (pintype "power_in"))
      (node (ref "P3") (pin "P$108") (pinfunction "P$1_P$108") (pintype "power_in"))
      (node (ref "P3") (pin "P$109") (pinfunction "P$1_P$109") (pintype "power_in"))
      (node (ref "P3") (pin "P$11") (pinfunction "P$1_P$11") (pintype "power_in"))
      (node (ref "P3") (pin "P$110") (pinfunction "P$1_P$110") (pintype "power_in"))
      (node (ref "P3") (pin "P$111") (pinfunction "P$1_P$111") (pintype "power_in"))
      (node (ref "P3") (pin "P$112") (pinfunction "P$1_P$112") (pintype "power_in"))
      (node (ref "P3") (pin "P$114") (pinfunction "P$1_P$114") (pintype "power_in"))
      (node (ref "P3") (pin "P$115") (pinfunction "P$1_P$115") (pintype "power_in"))
      (node (ref "P3") (pin "P$116") (pinfunction "P$1_P$116") (pintype "power_in"))
      (node (ref "P3") (pin "P$117") (pinfunction "P$1_P$117") (pintype "power_in"))
      (node (ref "P3") (pin "P$118") (pinfunction "P$1_P$118") (pintype "power_in"))
      (node (ref "P3") (pin "P$119") (pinfunction "P$1_P$119") (pintype "power_in"))
      (node (ref "P3") (pin "P$12") (pinfunction "P$1_P$12") (pintype "power_in"))
      (node (ref "P3") (pin "P$120") (pinfunction "P$1_P$120") (pintype "power_in"))
      (node (ref "P3") (pin "P$121") (pinfunction "P$1_P$121") (pintype "power_in"))
      (node (ref "P3") (pin "P$122") (pinfunction "P$1_P$122") (pintype "power_in"))
      (node (ref "P3") (pin "P$123") (pinfunction "P$1_P$123") (pintype "power_in"))
      (node (ref "P3") (pin "P$124") (pinfunction "P$1_P$124") (pintype "power_in"))
      (node (ref "P3") (pin "P$125") (pinfunction "P$1_P$125") (pintype "power_in"))
      (node (ref "P3") (pin "P$126") (pinfunction "P$1_P$126") (pintype "power_in"))
      (node (ref "P3") (pin "P$127") (pinfunction "P$1_P$127") (pintype "power_in"))
      (node (ref "P3") (pin "P$128") (pinfunction "P$1_P$128") (pintype "power_in"))
      (node (ref "P3") (pin "P$129") (pinfunction "P$1_P$129") (pintype "power_in"))
      (node (ref "P3") (pin "P$13") (pinfunction "P$1_P$13") (pintype "power_in"))
      (node (ref "P3") (pin "P$130") (pinfunction "P$1_P$130") (pintype "power_in"))
      (node (ref "P3") (pin "P$131") (pinfunction "P$1_P$131") (pintype "power_in"))
      (node (ref "P3") (pin "P$132") (pinfunction "P$1_P$132") (pintype "power_in"))
      (node (ref "P3") (pin "P$133") (pinfunction "P$1_P$133") (pintype "power_in"))
      (node (ref "P3") (pin "P$134") (pinfunction "P$1_P$134") (pintype "power_in"))
      (node (ref "P3") (pin "P$135") (pinfunction "P$1_P$135") (pintype "power_in"))
      (node (ref "P3") (pin "P$136") (pinfunction "P$1_P$136") (pintype "power_in"))
      (node (ref "P3") (pin "P$137") (pinfunction "P$1_P$137") (pintype "power_in"))
      (node (ref "P3") (pin "P$138") (pinfunction "P$1_P$138") (pintype "power_in"))
      (node (ref "P3") (pin "P$139") (pinfunction "P$1_P$139") (pintype "power_in"))
      (node (ref "P3") (pin "P$14") (pinfunction "P$1_P$14") (pintype "power_in"))
      (node (ref "P3") (pin "P$140") (pinfunction "P$1_P$140") (pintype "power_in"))
      (node (ref "P3") (pin "P$141") (pinfunction "P$1_P$141") (pintype "power_in"))
      (node (ref "P3") (pin "P$142") (pinfunction "P$1_P$142") (pintype "power_in"))
      (node (ref "P3") (pin "P$143") (pinfunction "P$1_P$143") (pintype "power_in"))
      (node (ref "P3") (pin "P$144") (pinfunction "P$1_P$144") (pintype "power_in"))
      (node (ref "P3") (pin "P$145") (pinfunction "P$1_P$145") (pintype "power_in"))
      (node (ref "P3") (pin "P$146") (pinfunction "P$1_P$146") (pintype "power_in"))
      (node (ref "P3") (pin "P$147") (pinfunction "P$1_P$147") (pintype "power_in"))
      (node (ref "P3") (pin "P$148") (pinfunction "P$1_P$148") (pintype "power_in"))
      (node (ref "P3") (pin "P$149") (pinfunction "P$1_P$149") (pintype "power_in"))
      (node (ref "P3") (pin "P$15") (pinfunction "P$1_P$15") (pintype "power_in"))
      (node (ref "P3") (pin "P$151") (pinfunction "P$1_P$151") (pintype "power_in"))
      (node (ref "P3") (pin "P$152") (pinfunction "P$1_P$152") (pintype "power_in"))
      (node (ref "P3") (pin "P$153") (pinfunction "P$1_P$153") (pintype "power_in"))
      (node (ref "P3") (pin "P$154") (pinfunction "P$1_P$154") (pintype "power_in"))
      (node (ref "P3") (pin "P$155") (pinfunction "P$1_P$155") (pintype "power_in"))
      (node (ref "P3") (pin "P$156") (pinfunction "P$1_P$156") (pintype "power_in"))
      (node (ref "P3") (pin "P$157") (pinfunction "P$1_P$157") (pintype "power_in"))
      (node (ref "P3") (pin "P$158") (pinfunction "P$1_P$158") (pintype "power_in"))
      (node (ref "P3") (pin "P$159") (pinfunction "P$1_P$159") (pintype "power_in"))
      (node (ref "P3") (pin "P$16") (pinfunction "P$1_P$16") (pintype "power_in"))
      (node (ref "P3") (pin "P$160") (pinfunction "P$1_P$160") (pintype "power_in"))
      (node (ref "P3") (pin "P$161") (pinfunction "P$1_P$161") (pintype "power_in"))
      (node (ref "P3") (pin "P$162") (pinfunction "P$1_P$162") (pintype "power_in"))
      (node (ref "P3") (pin "P$163") (pinfunction "P$1_P$163") (pintype "power_in"))
      (node (ref "P3") (pin "P$164") (pinfunction "P$1_P$164") (pintype "power_in"))
      (node (ref "P3") (pin "P$165") (pinfunction "P$1_P$165") (pintype "power_in"))
      (node (ref "P3") (pin "P$166") (pinfunction "P$1_P$166") (pintype "power_in"))
      (node (ref "P3") (pin "P$167") (pinfunction "P$1_P$167") (pintype "power_in"))
      (node (ref "P3") (pin "P$168") (pinfunction "P$1_P$168") (pintype "power_in"))
      (node (ref "P3") (pin "P$169") (pinfunction "P$1_P$169") (pintype "power_in"))
      (node (ref "P3") (pin "P$17") (pinfunction "P$1_P$17") (pintype "power_in"))
      (node (ref "P3") (pin "P$170") (pinfunction "P$1_P$170") (pintype "power_in"))
      (node (ref "P3") (pin "P$171") (pinfunction "P$1_P$171") (pintype "power_in"))
      (node (ref "P3") (pin "P$172") (pinfunction "P$1_P$172") (pintype "power_in"))
      (node (ref "P3") (pin "P$173") (pinfunction "P$1_P$173") (pintype "power_in"))
      (node (ref "P3") (pin "P$174") (pinfunction "P$1_P$174") (pintype "power_in"))
      (node (ref "P3") (pin "P$175") (pinfunction "P$1_P$175") (pintype "power_in"))
      (node (ref "P3") (pin "P$176") (pinfunction "P$1_P$176") (pintype "power_in"))
      (node (ref "P3") (pin "P$177") (pinfunction "P$1_P$177") (pintype "power_in"))
      (node (ref "P3") (pin "P$178") (pinfunction "P$1_P$178") (pintype "power_in"))
      (node (ref "P3") (pin "P$179") (pinfunction "P$1_P$179") (pintype "power_in"))
      (node (ref "P3") (pin "P$18") (pinfunction "P$1_P$18") (pintype "power_in"))
      (node (ref "P3") (pin "P$180") (pinfunction "P$1_P$180") (pintype "power_in"))
      (node (ref "P3") (pin "P$181") (pinfunction "P$1_P$181") (pintype "power_in"))
      (node (ref "P3") (pin "P$182") (pinfunction "P$1_P$182") (pintype "power_in"))
      (node (ref "P3") (pin "P$183") (pinfunction "P$1_P$183") (pintype "power_in"))
      (node (ref "P3") (pin "P$184") (pinfunction "P$1_P$184") (pintype "power_in"))
      (node (ref "P3") (pin "P$185") (pinfunction "P$1_P$185") (pintype "power_in"))
      (node (ref "P3") (pin "P$186") (pinfunction "P$1_P$186") (pintype "power_in"))
      (node (ref "P3") (pin "P$188") (pinfunction "P$1_P$188") (pintype "power_in"))
      (node (ref "P3") (pin "P$189") (pinfunction "P$1_P$189") (pintype "power_in"))
      (node (ref "P3") (pin "P$19") (pinfunction "P$1_P$19") (pintype "power_in"))
      (node (ref "P3") (pin "P$190") (pinfunction "P$1_P$190") (pintype "power_in"))
      (node (ref "P3") (pin "P$191") (pinfunction "P$1_P$191") (pintype "power_in"))
      (node (ref "P3") (pin "P$192") (pinfunction "P$1_P$192") (pintype "power_in"))
      (node (ref "P3") (pin "P$193") (pinfunction "P$1_P$193") (pintype "power_in"))
      (node (ref "P3") (pin "P$194") (pinfunction "P$1_P$194") (pintype "power_in"))
      (node (ref "P3") (pin "P$195") (pinfunction "P$1_P$195") (pintype "power_in"))
      (node (ref "P3") (pin "P$196") (pinfunction "P$1_P$196") (pintype "power_in"))
      (node (ref "P3") (pin "P$197") (pinfunction "P$1_P$197") (pintype "power_in"))
      (node (ref "P3") (pin "P$198") (pinfunction "P$1_P$198") (pintype "power_in"))
      (node (ref "P3") (pin "P$199") (pinfunction "P$1_P$199") (pintype "power_in"))
      (node (ref "P3") (pin "P$20") (pinfunction "P$1_P$20") (pintype "power_in"))
      (node (ref "P3") (pin "P$200") (pinfunction "P$1_P$200") (pintype "power_in"))
      (node (ref "P3") (pin "P$201") (pinfunction "P$1_P$201") (pintype "power_in"))
      (node (ref "P3") (pin "P$202") (pinfunction "P$1_P$202") (pintype "power_in"))
      (node (ref "P3") (pin "P$203") (pinfunction "P$1_P$203") (pintype "power_in"))
      (node (ref "P3") (pin "P$204") (pinfunction "P$1_P$204") (pintype "power_in"))
      (node (ref "P3") (pin "P$205") (pinfunction "P$1_P$205") (pintype "power_in"))
      (node (ref "P3") (pin "P$206") (pinfunction "P$1_P$206") (pintype "power_in"))
      (node (ref "P3") (pin "P$207") (pinfunction "P$1_P$207") (pintype "power_in"))
      (node (ref "P3") (pin "P$208") (pinfunction "P$1_P$208") (pintype "power_in"))
      (node (ref "P3") (pin "P$209") (pinfunction "P$1_P$209") (pintype "power_in"))
      (node (ref "P3") (pin "P$21") (pinfunction "P$1_P$21") (pintype "power_in"))
      (node (ref "P3") (pin "P$210") (pinfunction "P$1_P$210") (pintype "power_in"))
      (node (ref "P3") (pin "P$211") (pinfunction "P$1_P$211") (pintype "power_in"))
      (node (ref "P3") (pin "P$212") (pinfunction "P$1_P$212") (pintype "power_in"))
      (node (ref "P3") (pin "P$213") (pinfunction "P$1_P$213") (pintype "power_in"))
      (node (ref "P3") (pin "P$214") (pinfunction "P$1_P$214") (pintype "power_in"))
      (node (ref "P3") (pin "P$215") (pinfunction "P$1_P$215") (pintype "power_in"))
      (node (ref "P3") (pin "P$216") (pinfunction "P$1_P$216") (pintype "power_in"))
      (node (ref "P3") (pin "P$217") (pinfunction "P$1_P$217") (pintype "power_in"))
      (node (ref "P3") (pin "P$218") (pinfunction "P$1_P$218") (pintype "power_in"))
      (node (ref "P3") (pin "P$219") (pinfunction "P$1_P$219") (pintype "power_in"))
      (node (ref "P3") (pin "P$22") (pinfunction "P$1_P$22") (pintype "power_in"))
      (node (ref "P3") (pin "P$220") (pinfunction "P$1_P$220") (pintype "power_in"))
      (node (ref "P3") (pin "P$221") (pinfunction "P$1_P$221") (pintype "power_in"))
      (node (ref "P3") (pin "P$222") (pinfunction "P$1_P$222") (pintype "power_in"))
      (node (ref "P3") (pin "P$223") (pinfunction "P$1_P$223") (pintype "power_in"))
      (node (ref "P3") (pin "P$23") (pinfunction "P$1_P$23") (pintype "power_in"))
      (node (ref "P3") (pin "P$24") (pinfunction "P$1_P$24") (pintype "power_in"))
      (node (ref "P3") (pin "P$25") (pinfunction "P$1_P$25") (pintype "power_in"))
      (node (ref "P3") (pin "P$26") (pinfunction "P$1_P$26") (pintype "power_in"))
      (node (ref "P3") (pin "P$27") (pinfunction "P$1_P$27") (pintype "power_in"))
      (node (ref "P3") (pin "P$28") (pinfunction "P$1_P$28") (pintype "power_in"))
      (node (ref "P3") (pin "P$29") (pinfunction "P$1_P$29") (pintype "power_in"))
      (node (ref "P3") (pin "P$30") (pinfunction "P$1_P$30") (pintype "power_in"))
      (node (ref "P3") (pin "P$31") (pinfunction "P$1_P$31") (pintype "power_in"))
      (node (ref "P3") (pin "P$32") (pinfunction "P$1_P$32") (pintype "power_in"))
      (node (ref "P3") (pin "P$33") (pinfunction "P$1_P$33") (pintype "power_in"))
      (node (ref "P3") (pin "P$34") (pinfunction "P$1_P$34") (pintype "power_in"))
      (node (ref "P3") (pin "P$35") (pinfunction "P$1_P$35") (pintype "power_in"))
      (node (ref "P3") (pin "P$36") (pinfunction "P$1_P$36") (pintype "power_in"))
      (node (ref "P3") (pin "P$37") (pinfunction "P$1_P$37") (pintype "power_in"))
      (node (ref "P3") (pin "P$38") (pinfunction "P$1_P$38") (pintype "power_in"))
      (node (ref "P3") (pin "P$39") (pinfunction "P$1_P$39") (pintype "power_in"))
      (node (ref "P3") (pin "P$40") (pinfunction "P$1_P$40") (pintype "power_in"))
      (node (ref "P3") (pin "P$41") (pinfunction "P$1_P$41") (pintype "power_in"))
      (node (ref "P3") (pin "P$42") (pinfunction "P$1_P$42") (pintype "power_in"))
      (node (ref "P3") (pin "P$43") (pinfunction "P$1_P$43") (pintype "power_in"))
      (node (ref "P3") (pin "P$44") (pinfunction "P$1_P$44") (pintype "power_in"))
      (node (ref "P3") (pin "P$45") (pinfunction "P$1_P$45") (pintype "power_in"))
      (node (ref "P3") (pin "P$46") (pinfunction "P$1_P$46") (pintype "power_in"))
      (node (ref "P3") (pin "P$47") (pinfunction "P$1_P$47") (pintype "power_in"))
      (node (ref "P3") (pin "P$48") (pinfunction "P$1_P$48") (pintype "power_in"))
      (node (ref "P3") (pin "P$49") (pinfunction "P$1_P$49") (pintype "power_in"))
      (node (ref "P3") (pin "P$5") (pinfunction "P$1_P$5") (pintype "power_in"))
      (node (ref "P3") (pin "P$50") (pinfunction "P$1_P$50") (pintype "power_in"))
      (node (ref "P3") (pin "P$51") (pinfunction "P$1_P$51") (pintype "power_in"))
      (node (ref "P3") (pin "P$52") (pinfunction "P$1_P$52") (pintype "power_in"))
      (node (ref "P3") (pin "P$53") (pinfunction "P$1_P$53") (pintype "power_in"))
      (node (ref "P3") (pin "P$54") (pinfunction "P$1_P$54") (pintype "power_in"))
      (node (ref "P3") (pin "P$55") (pinfunction "P$1_P$55") (pintype "power_in"))
      (node (ref "P3") (pin "P$56") (pinfunction "P$1_P$56") (pintype "power_in"))
      (node (ref "P3") (pin "P$57") (pinfunction "P$1_P$57") (pintype "power_in"))
      (node (ref "P3") (pin "P$58") (pinfunction "P$1_P$58") (pintype "power_in"))
      (node (ref "P3") (pin "P$59") (pinfunction "P$1_P$59") (pintype "power_in"))
      (node (ref "P3") (pin "P$6") (pinfunction "P$1_P$6") (pintype "power_in"))
      (node (ref "P3") (pin "P$60") (pinfunction "P$1_P$60") (pintype "power_in"))
      (node (ref "P3") (pin "P$61") (pinfunction "P$1_P$61") (pintype "power_in"))
      (node (ref "P3") (pin "P$62") (pinfunction "P$1_P$62") (pintype "power_in"))
      (node (ref "P3") (pin "P$63") (pinfunction "P$1_P$63") (pintype "power_in"))
      (node (ref "P3") (pin "P$64") (pinfunction "P$1_P$64") (pintype "power_in"))
      (node (ref "P3") (pin "P$65") (pinfunction "P$1_P$65") (pintype "power_in"))
      (node (ref "P3") (pin "P$66") (pinfunction "P$1_P$66") (pintype "power_in"))
      (node (ref "P3") (pin "P$67") (pinfunction "P$1_P$67") (pintype "power_in"))
      (node (ref "P3") (pin "P$68") (pinfunction "P$1_P$68") (pintype "power_in"))
      (node (ref "P3") (pin "P$69") (pinfunction "P$1_P$69") (pintype "power_in"))
      (node (ref "P3") (pin "P$7") (pinfunction "P$1_P$7") (pintype "power_in"))
      (node (ref "P3") (pin "P$70") (pinfunction "P$1_P$70") (pintype "power_in"))
      (node (ref "P3") (pin "P$71") (pinfunction "P$1_P$71") (pintype "power_in"))
      (node (ref "P3") (pin "P$72") (pinfunction "P$1_P$72") (pintype "power_in"))
      (node (ref "P3") (pin "P$73") (pinfunction "P$1_P$73") (pintype "power_in"))
      (node (ref "P3") (pin "P$74") (pinfunction "P$1_P$74") (pintype "power_in"))
      (node (ref "P3") (pin "P$75") (pinfunction "P$1_P$75") (pintype "power_in"))
      (node (ref "P3") (pin "P$76") (pinfunction "P$1_P$76") (pintype "power_in"))
      (node (ref "P3") (pin "P$77") (pinfunction "P$1_P$77") (pintype "power_in"))
      (node (ref "P3") (pin "P$78") (pinfunction "P$1_P$78") (pintype "power_in"))
      (node (ref "P3") (pin "P$79") (pinfunction "P$1_P$79") (pintype "power_in"))
      (node (ref "P3") (pin "P$8") (pinfunction "P$1_P$8") (pintype "power_in"))
      (node (ref "P3") (pin "P$80") (pinfunction "P$1_P$80") (pintype "power_in"))
      (node (ref "P3") (pin "P$81") (pinfunction "P$1_P$81") (pintype "power_in"))
      (node (ref "P3") (pin "P$82") (pinfunction "P$1_P$82") (pintype "power_in"))
      (node (ref "P3") (pin "P$83") (pinfunction "P$1_P$83") (pintype "power_in"))
      (node (ref "P3") (pin "P$84") (pinfunction "P$1_P$84") (pintype "power_in"))
      (node (ref "P3") (pin "P$85") (pinfunction "P$1_P$85") (pintype "power_in"))
      (node (ref "P3") (pin "P$86") (pinfunction "P$1_P$86") (pintype "power_in"))
      (node (ref "P3") (pin "P$87") (pinfunction "P$1_P$87") (pintype "power_in"))
      (node (ref "P3") (pin "P$88") (pinfunction "P$1_P$88") (pintype "power_in"))
      (node (ref "P3") (pin "P$89") (pinfunction "P$1_P$89") (pintype "power_in"))
      (node (ref "P3") (pin "P$9") (pinfunction "P$1_P$9") (pintype "power_in"))
      (node (ref "P3") (pin "P$90") (pinfunction "P$1_P$90") (pintype "power_in"))
      (node (ref "P3") (pin "P$91") (pinfunction "P$1_P$91") (pintype "power_in"))
      (node (ref "P3") (pin "P$92") (pinfunction "P$1_P$92") (pintype "power_in"))
      (node (ref "P3") (pin "P$93") (pinfunction "P$1_P$93") (pintype "power_in"))
      (node (ref "P3") (pin "P$94") (pinfunction "P$1_P$94") (pintype "power_in"))
      (node (ref "P3") (pin "P$95") (pinfunction "P$1_P$95") (pintype "power_in"))
      (node (ref "P3") (pin "P$96") (pinfunction "P$1_P$96") (pintype "power_in"))
      (node (ref "P3") (pin "P$97") (pinfunction "P$1_P$97") (pintype "power_in"))
      (node (ref "P3") (pin "P$98") (pinfunction "P$1_P$98") (pintype "power_in"))
      (node (ref "P3") (pin "P$99") (pinfunction "P$1_P$99") (pintype "power_in"))
    )
    (net (code "5") (name "/P4") (class "Default")
      (node (ref "JP1") (pin "P$5") (pinfunction "4_P$5") (pintype "bidirectional"))
      (node (ref "P4") (pin "P$10") (pinfunction "P$1_P$10") (pintype "power_in"))
      (node (ref "P4") (pin "P$100") (pinfunction "P$1_P$100") (pintype "power_in"))
      (node (ref "P4") (pin "P$101") (pinfunction "P$1_P$101") (pintype "power_in"))
      (node (ref "P4") (pin "P$102") (pinfunction "P$1_P$102") (pintype "power_in"))
      (node (ref "P4") (pin "P$103") (pinfunction "P$1_P$103") (pintype "power_in"))
      (node (ref "P4") (pin "P$104") (pinfunction "P$1_P$104") (pintype "power_in"))
      (node (ref "P4") (pin "P$105") (pinfunction "P$1_P$105") (pintype "power_in"))
      (node (ref "P4") (pin "P$106") (pinfunction "P$1_P$106") (pintype "power_in"))
      (node (ref "P4") (pin "P$107") (pinfunction "P$1_P$107") (pintype "power_in"))
      (node (ref "P4") (pin "P$108") (pinfunction "P$1_P$108") (pintype "power_in"))
      (node (ref "P4") (pin "P$109") (pinfunction "P$1_P$109") (pintype "power_in"))
      (node (ref "P4") (pin "P$11") (pinfunction "P$1_P$11") (pintype "power_in"))
      (node (ref "P4") (pin "P$110") (pinfunction "P$1_P$110") (pintype "power_in"))
      (node (ref "P4") (pin "P$111") (pinfunction "P$1_P$111") (pintype "power_in"))
      (node (ref "P4") (pin "P$112") (pinfunction "P$1_P$112") (pintype "power_in"))
      (node (ref "P4") (pin "P$113") (pinfunction "P$1_P$113") (pintype "power_in"))
      (node (ref "P4") (pin "P$114") (pinfunction "P$1_P$114") (pintype "power_in"))
      (node (ref "P4") (pin "P$116") (pinfunction "P$1_P$116") (pintype "power_in"))
      (node (ref "P4") (pin "P$117") (pinfunction "P$1_P$117") (pintype "power_in"))
      (node (ref "P4") (pin "P$118") (pinfunction "P$1_P$118") (pintype "power_in"))
      (node (ref "P4") (pin "P$119") (pinfunction "P$1_P$119") (pintype "power_in"))
      (node (ref "P4") (pin "P$12") (pinfunction "P$1_P$12") (pintype "power_in"))
      (node (ref "P4") (pin "P$120") (pinfunction "P$1_P$120") (pintype "power_in"))
      (node (ref "P4") (pin "P$121") (pinfunction "P$1_P$121") (pintype "power_in"))
      (node (ref "P4") (pin "P$122") (pinfunction "P$1_P$122") (pintype "power_in"))
      (node (ref "P4") (pin "P$123") (pinfunction "P$1_P$123") (pintype "power_in"))
      (node (ref "P4") (pin "P$124") (pinfunction "P$1_P$124") (pintype "power_in"))
      (node (ref "P4") (pin "P$125") (pinfunction "P$1_P$125") (pintype "power_in"))
      (node (ref "P4") (pin "P$126") (pinfunction "P$1_P$126") (pintype "power_in"))
      (node (ref "P4") (pin "P$127") (pinfunction "P$1_P$127") (pintype "power_in"))
      (node (ref "P4") (pin "P$128") (pinfunction "P$1_P$128") (pintype "power_in"))
      (node (ref "P4") (pin "P$129") (pinfunction "P$1_P$129") (pintype "power_in"))
      (node (ref "P4") (pin "P$13") (pinfunction "P$1_P$13") (pintype "power_in"))
      (node (ref "P4") (pin "P$130") (pinfunction "P$1_P$130") (pintype "power_in"))
      (node (ref "P4") (pin "P$131") (pinfunction "P$1_P$131") (pintype "power_in"))
      (node (ref "P4") (pin "P$132") (pinfunction "P$1_P$132") (pintype "power_in"))
      (node (ref "P4") (pin "P$133") (pinfunction "P$1_P$133") (pintype "power_in"))
      (node (ref "P4") (pin "P$134") (pinfunction "P$1_P$134") (pintype "power_in"))
      (node (ref "P4") (pin "P$135") (pinfunction "P$1_P$135") (pintype "power_in"))
      (node (ref "P4") (pin "P$136") (pinfunction "P$1_P$136") (pintype "power_in"))
      (node (ref "P4") (pin "P$137") (pinfunction "P$1_P$137") (pintype "power_in"))
      (node (ref "P4") (pin "P$138") (pinfunction "P$1_P$138") (pintype "power_in"))
      (node (ref "P4") (pin "P$139") (pinfunction "P$1_P$139") (pintype "power_in"))
      (node (ref "P4") (pin "P$14") (pinfunction "P$1_P$14") (pintype "power_in"))
      (node (ref "P4") (pin "P$140") (pinfunction "P$1_P$140") (pintype "power_in"))
      (node (ref "P4") (pin "P$141") (pinfunction "P$1_P$141") (pintype "power_in"))
      (node (ref "P4") (pin "P$142") (pinfunction "P$1_P$142") (pintype "power_in"))
      (node (ref "P4") (pin "P$143") (pinfunction "P$1_P$143") (pintype "power_in"))
      (node (ref "P4") (pin "P$144") (pinfunction "P$1_P$144") (pintype "power_in"))
      (node (ref "P4") (pin "P$145") (pinfunction "P$1_P$145") (pintype "power_in"))
      (node (ref "P4") (pin "P$146") (pinfunction "P$1_P$146") (pintype "power_in"))
      (node (ref "P4") (pin "P$147") (pinfunction "P$1_P$147") (pintype "power_in"))
      (node (ref "P4") (pin "P$148") (pinfunction "P$1_P$148") (pintype "power_in"))
      (node (ref "P4") (pin "P$149") (pinfunction "P$1_P$149") (pintype "power_in"))
      (node (ref "P4") (pin "P$15") (pinfunction "P$1_P$15") (pintype "power_in"))
      (node (ref "P4") (pin "P$150") (pinfunction "P$1_P$150") (pintype "power_in"))
      (node (ref "P4") (pin "P$151") (pinfunction "P$1_P$151") (pintype "power_in"))
      (node (ref "P4") (pin "P$153") (pinfunction "P$1_P$153") (pintype "power_in"))
      (node (ref "P4") (pin "P$154") (pinfunction "P$1_P$154") (pintype "power_in"))
      (node (ref "P4") (pin "P$155") (pinfunction "P$1_P$155") (pintype "power_in"))
      (node (ref "P4") (pin "P$156") (pinfunction "P$1_P$156") (pintype "power_in"))
      (node (ref "P4") (pin "P$157") (pinfunction "P$1_P$157") (pintype "power_in"))
      (node (ref "P4") (pin "P$158") (pinfunction "P$1_P$158") (pintype "power_in"))
      (node (ref "P4") (pin "P$159") (pinfunction "P$1_P$159") (pintype "power_in"))
      (node (ref "P4") (pin "P$16") (pinfunction "P$1_P$16") (pintype "power_in"))
      (node (ref "P4") (pin "P$160") (pinfunction "P$1_P$160") (pintype "power_in"))
      (node (ref "P4") (pin "P$161") (pinfunction "P$1_P$161") (pintype "power_in"))
      (node (ref "P4") (pin "P$162") (pinfunction "P$1_P$162") (pintype "power_in"))
      (node (ref "P4") (pin "P$163") (pinfunction "P$1_P$163") (pintype "power_in"))
      (node (ref "P4") (pin "P$164") (pinfunction "P$1_P$164") (pintype "power_in"))
      (node (ref "P4") (pin "P$165") (pinfunction "P$1_P$165") (pintype "power_in"))
      (node (ref "P4") (pin "P$166") (pinfunction "P$1_P$166") (pintype "power_in"))
      (node (ref "P4") (pin "P$167") (pinfunction "P$1_P$167") (pintype "power_in"))
      (node (ref "P4") (pin "P$168") (pinfunction "P$1_P$168") (pintype "power_in"))
      (node (ref "P4") (pin "P$169") (pinfunction "P$1_P$169") (pintype "power_in"))
      (node (ref "P4") (pin "P$17") (pinfunction "P$1_P$17") (pintype "power_in"))
      (node (ref "P4") (pin "P$170") (pinfunction "P$1_P$170") (pintype "power_in"))
      (node (ref "P4") (pin "P$171") (pinfunction "P$1_P$171") (pintype "power_in"))
      (node (ref "P4") (pin "P$172") (pinfunction "P$1_P$172") (pintype "power_in"))
      (node (ref "P4") (pin "P$173") (pinfunction "P$1_P$173") (pintype "power_in"))
      (node (ref "P4") (pin "P$174") (pinfunction "P$1_P$174") (pintype "power_in"))
      (node (ref "P4") (pin "P$175") (pinfunction "P$1_P$175") (pintype "power_in"))
      (node (ref "P4") (pin "P$176") (pinfunction "P$1_P$176") (pintype "power_in"))
      (node (ref "P4") (pin "P$177") (pinfunction "P$1_P$177") (pintype "power_in"))
      (node (ref "P4") (pin "P$178") (pinfunction "P$1_P$178") (pintype "power_in"))
      (node (ref "P4") (pin "P$179") (pinfunction "P$1_P$179") (pintype "power_in"))
      (node (ref "P4") (pin "P$18") (pinfunction "P$1_P$18") (pintype "power_in"))
      (node (ref "P4") (pin "P$180") (pinfunction "P$1_P$180") (pintype "power_in"))
      (node (ref "P4") (pin "P$181") (pinfunction "P$1_P$181") (pintype "power_in"))
      (node (ref "P4") (pin "P$182") (pinfunction "P$1_P$182") (pintype "power_in"))
      (node (ref "P4") (pin "P$183") (pinfunction "P$1_P$183") (pintype "power_in"))
      (node (ref "P4") (pin "P$184") (pinfunction "P$1_P$184") (pintype "power_in"))
      (node (ref "P4") (pin "P$185") (pinfunction "P$1_P$185") (pintype "power_in"))
      (node (ref "P4") (pin "P$186") (pinfunction "P$1_P$186") (pintype "power_in"))
      (node (ref "P4") (pin "P$187") (pinfunction "P$1_P$187") (pintype "power_in"))
      (node (ref "P4") (pin "P$188") (pinfunction "P$1_P$188") (pintype "power_in"))
      (node (ref "P4") (pin "P$19") (pinfunction "P$1_P$19") (pintype "power_in"))
      (node (ref "P4") (pin "P$190") (pinfunction "P$1_P$190") (pintype "power_in"))
      (node (ref "P4") (pin "P$191") (pinfunction "P$1_P$191") (pintype "power_in"))
      (node (ref "P4") (pin "P$192") (pinfunction "P$1_P$192") (pintype "power_in"))
      (node (ref "P4") (pin "P$193") (pinfunction "P$1_P$193") (pintype "power_in"))
      (node (ref "P4") (pin "P$194") (pinfunction "P$1_P$194") (pintype "power_in"))
      (node (ref "P4") (pin "P$195") (pinfunction "P$1_P$195") (pintype "power_in"))
      (node (ref "P4") (pin "P$196") (pinfunction "P$1_P$196") (pintype "power_in"))
      (node (ref "P4") (pin "P$197") (pinfunction "P$1_P$197") (pintype "power_in"))
      (node (ref "P4") (pin "P$198") (pinfunction "P$1_P$198") (pintype "power_in"))
      (node (ref "P4") (pin "P$199") (pinfunction "P$1_P$199") (pintype "power_in"))
      (node (ref "P4") (pin "P$20") (pinfunction "P$1_P$20") (pintype "power_in"))
      (node (ref "P4") (pin "P$200") (pinfunction "P$1_P$200") (pintype "power_in"))
      (node (ref "P4") (pin "P$201") (pinfunction "P$1_P$201") (pintype "power_in"))
      (node (ref "P4") (pin "P$202") (pinfunction "P$1_P$202") (pintype "power_in"))
      (node (ref "P4") (pin "P$203") (pinfunction "P$1_P$203") (pintype "power_in"))
      (node (ref "P4") (pin "P$204") (pinfunction "P$1_P$204") (pintype "power_in"))
      (node (ref "P4") (pin "P$205") (pinfunction "P$1_P$205") (pintype "power_in"))
      (node (ref "P4") (pin "P$206") (pinfunction "P$1_P$206") (pintype "power_in"))
      (node (ref "P4") (pin "P$207") (pinfunction "P$1_P$207") (pintype "power_in"))
      (node (ref "P4") (pin "P$208") (pinfunction "P$1_P$208") (pintype "power_in"))
      (node (ref "P4") (pin "P$209") (pinfunction "P$1_P$209") (pintype "power_in"))
      (node (ref "P4") (pin "P$21") (pinfunction "P$1_P$21") (pintype "power_in"))
      (node (ref "P4") (pin "P$210") (pinfunction "P$1_P$210") (pintype "power_in"))
      (node (ref "P4") (pin "P$211") (pinfunction "P$1_P$211") (pintype "power_in"))
      (node (ref "P4") (pin "P$212") (pinfunction "P$1_P$212") (pintype "power_in"))
      (node (ref "P4") (pin "P$213") (pinfunction "P$1_P$213") (pintype "power_in"))
      (node (ref "P4") (pin "P$214") (pinfunction "P$1_P$214") (pintype "power_in"))
      (node (ref "P4") (pin "P$215") (pinfunction "P$1_P$215") (pintype "power_in"))
      (node (ref "P4") (pin "P$216") (pinfunction "P$1_P$216") (pintype "power_in"))
      (node (ref "P4") (pin "P$217") (pinfunction "P$1_P$217") (pintype "power_in"))
      (node (ref "P4") (pin "P$218") (pinfunction "P$1_P$218") (pintype "power_in"))
      (node (ref "P4") (pin "P$219") (pinfunction "P$1_P$219") (pintype "power_in"))
      (node (ref "P4") (pin "P$22") (pinfunction "P$1_P$22") (pintype "power_in"))
      (node (ref "P4") (pin "P$220") (pinfunction "P$1_P$220") (pintype "power_in"))
      (node (ref "P4") (pin "P$221") (pinfunction "P$1_P$221") (pintype "power_in"))
      (node (ref "P4") (pin "P$222") (pinfunction "P$1_P$222") (pintype "power_in"))
      (node (ref "P4") (pin "P$223") (pinfunction "P$1_P$223") (pintype "power_in"))
      (node (ref "P4") (pin "P$224") (pinfunction "P$1_P$224") (pintype "power_in"))
      (node (ref "P4") (pin "P$225") (pinfunction "P$1_P$225") (pintype "power_in"))
      (node (ref "P4") (pin "P$23") (pinfunction "P$1_P$23") (pintype "power_in"))
      (node (ref "P4") (pin "P$24") (pinfunction "P$1_P$24") (pintype "power_in"))
      (node (ref "P4") (pin "P$25") (pinfunction "P$1_P$25") (pintype "power_in"))
      (node (ref "P4") (pin "P$26") (pinfunction "P$1_P$26") (pintype "power_in"))
      (node (ref "P4") (pin "P$27") (pinfunction "P$1_P$27") (pintype "power_in"))
      (node (ref "P4") (pin "P$28") (pinfunction "P$1_P$28") (pintype "power_in"))
      (node (ref "P4") (pin "P$29") (pinfunction "P$1_P$29") (pintype "power_in"))
      (node (ref "P4") (pin "P$30") (pinfunction "P$1_P$30") (pintype "power_in"))
      (node (ref "P4") (pin "P$31") (pinfunction "P$1_P$31") (pintype "power_in"))
      (node (ref "P4") (pin "P$32") (pinfunction "P$1_P$32") (pintype "power_in"))
      (node (ref "P4") (pin "P$33") (pinfunction "P$1_P$33") (pintype "power_in"))
      (node (ref "P4") (pin "P$34") (pinfunction "P$1_P$34") (pintype "power_in"))
      (node (ref "P4") (pin "P$35") (pinfunction "P$1_P$35") (pintype "power_in"))
      (node (ref "P4") (pin "P$36") (pinfunction "P$1_P$36") (pintype "power_in"))
      (node (ref "P4") (pin "P$37") (pinfunction "P$1_P$37") (pintype "power_in"))
      (node (ref "P4") (pin "P$38") (pinfunction "P$1_P$38") (pintype "power_in"))
      (node (ref "P4") (pin "P$39") (pinfunction "P$1_P$39") (pintype "power_in"))
      (node (ref "P4") (pin "P$40") (pinfunction "P$1_P$40") (pintype "power_in"))
      (node (ref "P4") (pin "P$42") (pinfunction "P$1_P$42") (pintype "power_in"))
      (node (ref "P4") (pin "P$43") (pinfunction "P$1_P$43") (pintype "power_in"))
      (node (ref "P4") (pin "P$44") (pinfunction "P$1_P$44") (pintype "power_in"))
      (node (ref "P4") (pin "P$45") (pinfunction "P$1_P$45") (pintype "power_in"))
      (node (ref "P4") (pin "P$46") (pinfunction "P$1_P$46") (pintype "power_in"))
      (node (ref "P4") (pin "P$47") (pinfunction "P$1_P$47") (pintype "power_in"))
      (node (ref "P4") (pin "P$48") (pinfunction "P$1_P$48") (pintype "power_in"))
      (node (ref "P4") (pin "P$49") (pinfunction "P$1_P$49") (pintype "power_in"))
      (node (ref "P4") (pin "P$5") (pinfunction "P$1_P$5") (pintype "power_in"))
      (node (ref "P4") (pin "P$50") (pinfunction "P$1_P$50") (pintype "power_in"))
      (node (ref "P4") (pin "P$51") (pinfunction "P$1_P$51") (pintype "power_in"))
      (node (ref "P4") (pin "P$52") (pinfunction "P$1_P$52") (pintype "power_in"))
      (node (ref "P4") (pin "P$53") (pinfunction "P$1_P$53") (pintype "power_in"))
      (node (ref "P4") (pin "P$54") (pinfunction "P$1_P$54") (pintype "power_in"))
      (node (ref "P4") (pin "P$55") (pinfunction "P$1_P$55") (pintype "power_in"))
      (node (ref "P4") (pin "P$56") (pinfunction "P$1_P$56") (pintype "power_in"))
      (node (ref "P4") (pin "P$57") (pinfunction "P$1_P$57") (pintype "power_in"))
      (node (ref "P4") (pin "P$58") (pinfunction "P$1_P$58") (pintype "power_in"))
      (node (ref "P4") (pin "P$59") (pinfunction "P$1_P$59") (pintype "power_in"))
      (node (ref "P4") (pin "P$6") (pinfunction "P$1_P$6") (pintype "power_in"))
      (node (ref "P4") (pin "P$60") (pinfunction "P$1_P$60") (pintype "power_in"))
      (node (ref "P4") (pin "P$61") (pinfunction "P$1_P$61") (pintype "power_in"))
      (node (ref "P4") (pin "P$62") (pinfunction "P$1_P$62") (pintype "power_in"))
      (node (ref "P4") (pin "P$63") (pinfunction "P$1_P$63") (pintype "power_in"))
      (node (ref "P4") (pin "P$64") (pinfunction "P$1_P$64") (pintype "power_in"))
      (node (ref "P4") (pin "P$65") (pinfunction "P$1_P$65") (pintype "power_in"))
      (node (ref "P4") (pin "P$66") (pinfunction "P$1_P$66") (pintype "power_in"))
      (node (ref "P4") (pin "P$67") (pinfunction "P$1_P$67") (pintype "power_in"))
      (node (ref "P4") (pin "P$68") (pinfunction "P$1_P$68") (pintype "power_in"))
      (node (ref "P4") (pin "P$69") (pinfunction "P$1_P$69") (pintype "power_in"))
      (node (ref "P4") (pin "P$7") (pinfunction "P$1_P$7") (pintype "power_in"))
      (node (ref "P4") (pin "P$70") (pinfunction "P$1_P$70") (pintype "power_in"))
      (node (ref "P4") (pin "P$71") (pinfunction "P$1_P$71") (pintype "power_in"))
      (node (ref "P4") (pin "P$72") (pinfunction "P$1_P$72") (pintype "power_in"))
      (node (ref "P4") (pin "P$73") (pinfunction "P$1_P$73") (pintype "power_in"))
      (node (ref "P4") (pin "P$74") (pinfunction "P$1_P$74") (pintype "power_in"))
      (node (ref "P4") (pin "P$75") (pinfunction "P$1_P$75") (pintype "power_in"))
      (node (ref "P4") (pin "P$76") (pinfunction "P$1_P$76") (pintype "power_in"))
      (node (ref "P4") (pin "P$77") (pinfunction "P$1_P$77") (pintype "power_in"))
      (node (ref "P4") (pin "P$79") (pinfunction "P$1_P$79") (pintype "power_in"))
      (node (ref "P4") (pin "P$8") (pinfunction "P$1_P$8") (pintype "power_in"))
      (node (ref "P4") (pin "P$80") (pinfunction "P$1_P$80") (pintype "power_in"))
      (node (ref "P4") (pin "P$81") (pinfunction "P$1_P$81") (pintype "power_in"))
      (node (ref "P4") (pin "P$82") (pinfunction "P$1_P$82") (pintype "power_in"))
      (node (ref "P4") (pin "P$83") (pinfunction "P$1_P$83") (pintype "power_in"))
      (node (ref "P4") (pin "P$84") (pinfunction "P$1_P$84") (pintype "power_in"))
      (node (ref "P4") (pin "P$85") (pinfunction "P$1_P$85") (pintype "power_in"))
      (node (ref "P4") (pin "P$86") (pinfunction "P$1_P$86") (pintype "power_in"))
      (node (ref "P4") (pin "P$87") (pinfunction "P$1_P$87") (pintype "power_in"))
      (node (ref "P4") (pin "P$88") (pinfunction "P$1_P$88") (pintype "power_in"))
      (node (ref "P4") (pin "P$89") (pinfunction "P$1_P$89") (pintype "power_in"))
      (node (ref "P4") (pin "P$9") (pinfunction "P$1_P$9") (pintype "power_in"))
      (node (ref "P4") (pin "P$90") (pinfunction "P$1_P$90") (pintype "power_in"))
      (node (ref "P4") (pin "P$91") (pinfunction "P$1_P$91") (pintype "power_in"))
      (node (ref "P4") (pin "P$92") (pinfunction "P$1_P$92") (pintype "power_in"))
      (node (ref "P4") (pin "P$93") (pinfunction "P$1_P$93") (pintype "power_in"))
      (node (ref "P4") (pin "P$94") (pinfunction "P$1_P$94") (pintype "power_in"))
      (node (ref "P4") (pin "P$95") (pinfunction "P$1_P$95") (pintype "power_in"))
      (node (ref "P4") (pin "P$96") (pinfunction "P$1_P$96") (pintype "power_in"))
      (node (ref "P4") (pin "P$97") (pinfunction "P$1_P$97") (pintype "power_in"))
      (node (ref "P4") (pin "P$98") (pinfunction "P$1_P$98") (pintype "power_in"))
      (node (ref "P4") (pin "P$99") (pinfunction "P$1_P$99") (pintype "power_in"))
    )
    (net (code "6") (name "/P5") (class "Default")
      (node (ref "JP1") (pin "P$6") (pinfunction "5_P$6") (pintype "bidirectional"))
      (node (ref "P5") (pin "P$10") (pinfunction "P$1_P$10") (pintype "power_in"))
      (node (ref "P5") (pin "P$100") (pinfunction "P$1_P$100") (pintype "power_in"))
      (node (ref "P5") (pin "P$101") (pinfunction "P$1_P$101") (pintype "power_in"))
      (node (ref "P5") (pin "P$102") (pinfunction "P$1_P$102") (pintype "power_in"))
      (node (ref "P5") (pin "P$103") (pinfunction "P$1_P$103") (pintype "power_in"))
      (node (ref "P5") (pin "P$104") (pinfunction "P$1_P$104") (pintype "power_in"))
      (node (ref "P5") (pin "P$105") (pinfunction "P$1_P$105") (pintype "power_in"))
      (node (ref "P5") (pin "P$106") (pinfunction "P$1_P$106") (pintype "power_in"))
      (node (ref "P5") (pin "P$107") (pinfunction "P$1_P$107") (pintype "power_in"))
      (node (ref "P5") (pin "P$108") (pinfunction "P$1_P$108") (pintype "power_in"))
      (node (ref "P5") (pin "P$109") (pinfunction "P$1_P$109") (pintype "power_in"))
      (node (ref "P5") (pin "P$11") (pinfunction "P$1_P$11") (pintype "power_in"))
      (node (ref "P5") (pin "P$110") (pinfunction "P$1_P$110") (pintype "power_in"))
      (node (ref "P5") (pin "P$111") (pinfunction "P$1_P$111") (pintype "power_in"))
      (node (ref "P5") (pin "P$112") (pinfunction "P$1_P$112") (pintype "power_in"))
      (node (ref "P5") (pin "P$114") (pinfunction "P$1_P$114") (pintype "power_in"))
      (node (ref "P5") (pin "P$115") (pinfunction "P$1_P$115") (pintype "power_in"))
      (node (ref "P5") (pin "P$116") (pinfunction "P$1_P$116") (pintype "power_in"))
      (node (ref "P5") (pin "P$117") (pinfunction "P$1_P$117") (pintype "power_in"))
      (node (ref "P5") (pin "P$118") (pinfunction "P$1_P$118") (pintype "power_in"))
      (node (ref "P5") (pin "P$119") (pinfunction "P$1_P$119") (pintype "power_in"))
      (node (ref "P5") (pin "P$12") (pinfunction "P$1_P$12") (pintype "power_in"))
      (node (ref "P5") (pin "P$120") (pinfunction "P$1_P$120") (pintype "power_in"))
      (node (ref "P5") (pin "P$121") (pinfunction "P$1_P$121") (pintype "power_in"))
      (node (ref "P5") (pin "P$122") (pinfunction "P$1_P$122") (pintype "power_in"))
      (node (ref "P5") (pin "P$123") (pinfunction "P$1_P$123") (pintype "power_in"))
      (node (ref "P5") (pin "P$124") (pinfunction "P$1_P$124") (pintype "power_in"))
      (node (ref "P5") (pin "P$125") (pinfunction "P$1_P$125") (pintype "power_in"))
      (node (ref "P5") (pin "P$126") (pinfunction "P$1_P$126") (pintype "power_in"))
      (node (ref "P5") (pin "P$127") (pinfunction "P$1_P$127") (pintype "power_in"))
      (node (ref "P5") (pin "P$128") (pinfunction "P$1_P$128") (pintype "power_in"))
      (node (ref "P5") (pin "P$129") (pinfunction "P$1_P$129") (pintype "power_in"))
      (node (ref "P5") (pin "P$13") (pinfunction "P$1_P$13") (pintype "power_in"))
      (node (ref "P5") (pin "P$130") (pinfunction "P$1_P$130") (pintype "power_in"))
      (node (ref "P5") (pin "P$131") (pinfunction "P$1_P$131") (pintype "power_in"))
      (node (ref "P5") (pin "P$132") (pinfunction "P$1_P$132") (pintype "power_in"))
      (node (ref "P5") (pin "P$133") (pinfunction "P$1_P$133") (pintype "power_in"))
      (node (ref "P5") (pin "P$134") (pinfunction "P$1_P$134") (pintype "power_in"))
      (node (ref "P5") (pin "P$135") (pinfunction "P$1_P$135") (pintype "power_in"))
      (node (ref "P5") (pin "P$136") (pinfunction "P$1_P$136") (pintype "power_in"))
      (node (ref "P5") (pin "P$137") (pinfunction "P$1_P$137") (pintype "power_in"))
      (node (ref "P5") (pin "P$138") (pinfunction "P$1_P$138") (pintype "power_in"))
      (node (ref "P5") (pin "P$139") (pinfunction "P$1_P$139") (pintype "power_in"))
      (node (ref "P5") (pin "P$14") (pinfunction "P$1_P$14") (pintype "power_in"))
      (node (ref "P5") (pin "P$140") (pinfunction "P$1_P$140") (pintype "power_in"))
      (node (ref "P5") (pin "P$141") (pinfunction "P$1_P$141") (pintype "power_in"))
      (node (ref "P5") (pin "P$142") (pinfunction "P$1_P$142") (pintype "power_in"))
      (node (ref "P5") (pin "P$143") (pinfunction "P$1_P$143") (pintype "power_in"))
      (node (ref "P5") (pin "P$144") (pinfunction "P$1_P$144") (pintype "power_in"))
      (node (ref "P5") (pin "P$145") (pinfunction "P$1_P$145") (pintype "power_in"))
      (node (ref "P5") (pin "P$146") (pinfunction "P$1_P$146") (pintype "power_in"))
      (node (ref "P5") (pin "P$147") (pinfunction "P$1_P$147") (pintype "power_in"))
      (node (ref "P5") (pin "P$148") (pinfunction "P$1_P$148") (pintype "power_in"))
      (node (ref "P5") (pin "P$149") (pinfunction "P$1_P$149") (pintype "power_in"))
      (node (ref "P5") (pin "P$15") (pinfunction "P$1_P$15") (pintype "power_in"))
      (node (ref "P5") (pin "P$151") (pinfunction "P$1_P$151") (pintype "power_in"))
      (node (ref "P5") (pin "P$152") (pinfunction "P$1_P$152") (pintype "power_in"))
      (node (ref "P5") (pin "P$153") (pinfunction "P$1_P$153") (pintype "power_in"))
      (node (ref "P5") (pin "P$154") (pinfunction "P$1_P$154") (pintype "power_in"))
      (node (ref "P5") (pin "P$155") (pinfunction "P$1_P$155") (pintype "power_in"))
      (node (ref "P5") (pin "P$156") (pinfunction "P$1_P$156") (pintype "power_in"))
      (node (ref "P5") (pin "P$157") (pinfunction "P$1_P$157") (pintype "power_in"))
      (node (ref "P5") (pin "P$158") (pinfunction "P$1_P$158") (pintype "power_in"))
      (node (ref "P5") (pin "P$159") (pinfunction "P$1_P$159") (pintype "power_in"))
      (node (ref "P5") (pin "P$16") (pinfunction "P$1_P$16") (pintype "power_in"))
      (node (ref "P5") (pin "P$160") (pinfunction "P$1_P$160") (pintype "power_in"))
      (node (ref "P5") (pin "P$161") (pinfunction "P$1_P$161") (pintype "power_in"))
      (node (ref "P5") (pin "P$162") (pinfunction "P$1_P$162") (pintype "power_in"))
      (node (ref "P5") (pin "P$163") (pinfunction "P$1_P$163") (pintype "power_in"))
      (node (ref "P5") (pin "P$164") (pinfunction "P$1_P$164") (pintype "power_in"))
      (node (ref "P5") (pin "P$165") (pinfunction "P$1_P$165") (pintype "power_in"))
      (node (ref "P5") (pin "P$166") (pinfunction "P$1_P$166") (pintype "power_in"))
      (node (ref "P5") (pin "P$167") (pinfunction "P$1_P$167") (pintype "power_in"))
      (node (ref "P5") (pin "P$168") (pinfunction "P$1_P$168") (pintype "power_in"))
      (node (ref "P5") (pin "P$169") (pinfunction "P$1_P$169") (pintype "power_in"))
      (node (ref "P5") (pin "P$17") (pinfunction "P$1_P$17") (pintype "power_in"))
      (node (ref "P5") (pin "P$170") (pinfunction "P$1_P$170") (pintype "power_in"))
      (node (ref "P5") (pin "P$171") (pinfunction "P$1_P$171") (pintype "power_in"))
      (node (ref "P5") (pin "P$172") (pinfunction "P$1_P$172") (pintype "power_in"))
      (node (ref "P5") (pin "P$173") (pinfunction "P$1_P$173") (pintype "power_in"))
      (node (ref "P5") (pin "P$174") (pinfunction "P$1_P$174") (pintype "power_in"))
      (node (ref "P5") (pin "P$175") (pinfunction "P$1_P$175") (pintype "power_in"))
      (node (ref "P5") (pin "P$176") (pinfunction "P$1_P$176") (pintype "power_in"))
      (node (ref "P5") (pin "P$177") (pinfunction "P$1_P$177") (pintype "power_in"))
      (node (ref "P5") (pin "P$178") (pinfunction "P$1_P$178") (pintype "power_in"))
      (node (ref "P5") (pin "P$179") (pinfunction "P$1_P$179") (pintype "power_in"))
      (node (ref "P5") (pin "P$18") (pinfunction "P$1_P$18") (pintype "power_in"))
      (node (ref "P5") (pin "P$180") (pinfunction "P$1_P$180") (pintype "power_in"))
      (node (ref "P5") (pin "P$181") (pinfunction "P$1_P$181") (pintype "power_in"))
      (node (ref "P5") (pin "P$182") (pinfunction "P$1_P$182") (pintype "power_in"))
      (node (ref "P5") (pin "P$183") (pinfunction "P$1_P$183") (pintype "power_in"))
      (node (ref "P5") (pin "P$184") (pinfunction "P$1_P$184") (pintype "power_in"))
      (node (ref "P5") (pin "P$185") (pinfunction "P$1_P$185") (pintype "power_in"))
      (node (ref "P5") (pin "P$186") (pinfunction "P$1_P$186") (pintype "power_in"))
      (node (ref "P5") (pin "P$188") (pinfunction "P$1_P$188") (pintype "power_in"))
      (node (ref "P5") (pin "P$189") (pinfunction "P$1_P$189") (pintype "power_in"))
      (node (ref "P5") (pin "P$19") (pinfunction "P$1_P$19") (pintype "power_in"))
      (node (ref "P5") (pin "P$190") (pinfunction "P$1_P$190") (pintype "power_in"))
      (node (ref "P5") (pin "P$191") (pinfunction "P$1_P$191") (pintype "power_in"))
      (node (ref "P5") (pin "P$192") (pinfunction "P$1_P$192") (pintype "power_in"))
      (node (ref "P5") (pin "P$193") (pinfunction "P$1_P$193") (pintype "power_in"))
      (node (ref "P5") (pin "P$194") (pinfunction "P$1_P$194") (pintype "power_in"))
      (node (ref "P5") (pin "P$195") (pinfunction "P$1_P$195") (pintype "power_in"))
      (node (ref "P5") (pin "P$196") (pinfunction "P$1_P$196") (pintype "power_in"))
      (node (ref "P5") (pin "P$197") (pinfunction "P$1_P$197") (pintype "power_in"))
      (node (ref "P5") (pin "P$198") (pinfunction "P$1_P$198") (pintype "power_in"))
      (node (ref "P5") (pin "P$199") (pinfunction "P$1_P$199") (pintype "power_in"))
      (node (ref "P5") (pin "P$20") (pinfunction "P$1_P$20") (pintype "power_in"))
      (node (ref "P5") (pin "P$200") (pinfunction "P$1_P$200") (pintype "power_in"))
      (node (ref "P5") (pin "P$201") (pinfunction "P$1_P$201") (pintype "power_in"))
      (node (ref "P5") (pin "P$202") (pinfunction "P$1_P$202") (pintype "power_in"))
      (node (ref "P5") (pin "P$203") (pinfunction "P$1_P$203") (pintype "power_in"))
      (node (ref "P5") (pin "P$204") (pinfunction "P$1_P$204") (pintype "power_in"))
      (node (ref "P5") (pin "P$205") (pinfunction "P$1_P$205") (pintype "power_in"))
      (node (ref "P5") (pin "P$206") (pinfunction "P$1_P$206") (pintype "power_in"))
      (node (ref "P5") (pin "P$207") (pinfunction "P$1_P$207") (pintype "power_in"))
      (node (ref "P5") (pin "P$208") (pinfunction "P$1_P$208") (pintype "power_in"))
      (node (ref "P5") (pin "P$209") (pinfunction "P$1_P$209") (pintype "power_in"))
      (node (ref "P5") (pin "P$21") (pinfunction "P$1_P$21") (pintype "power_in"))
      (node (ref "P5") (pin "P$210") (pinfunction "P$1_P$210") (pintype "power_in"))
      (node (ref "P5") (pin "P$211") (pinfunction "P$1_P$211") (pintype "power_in"))
      (node (ref "P5") (pin "P$212") (pinfunction "P$1_P$212") (pintype "power_in"))
      (node (ref "P5") (pin "P$213") (pinfunction "P$1_P$213") (pintype "power_in"))
      (node (ref "P5") (pin "P$214") (pinfunction "P$1_P$214") (pintype "power_in"))
      (node (ref "P5") (pin "P$215") (pinfunction "P$1_P$215") (pintype "power_in"))
      (node (ref "P5") (pin "P$216") (pinfunction "P$1_P$216") (pintype "power_in"))
      (node (ref "P5") (pin "P$217") (pinfunction "P$1_P$217") (pintype "power_in"))
      (node (ref "P5") (pin "P$218") (pinfunction "P$1_P$218") (pintype "power_in"))
      (node (ref "P5") (pin "P$219") (pinfunction "P$1_P$219") (pintype "power_in"))
      (node (ref "P5") (pin "P$22") (pinfunction "P$1_P$22") (pintype "power_in"))
      (node (ref "P5") (pin "P$220") (pinfunction "P$1_P$220") (pintype "power_in"))
      (node (ref "P5") (pin "P$221") (pinfunction "P$1_P$221") (pintype "power_in"))
      (node (ref "P5") (pin "P$222") (pinfunction "P$1_P$222") (pintype "power_in"))
      (node (ref "P5") (pin "P$223") (pinfunction "P$1_P$223") (pintype "power_in"))
      (node (ref "P5") (pin "P$23") (pinfunction "P$1_P$23") (pintype "power_in"))
      (node (ref "P5") (pin "P$24") (pinfunction "P$1_P$24") (pintype "power_in"))
      (node (ref "P5") (pin "P$25") (pinfunction "P$1_P$25") (pintype "power_in"))
      (node (ref "P5") (pin "P$26") (pinfunction "P$1_P$26") (pintype "power_in"))
      (node (ref "P5") (pin "P$27") (pinfunction "P$1_P$27") (pintype "power_in"))
      (node (ref "P5") (pin "P$28") (pinfunction "P$1_P$28") (pintype "power_in"))
      (node (ref "P5") (pin "P$29") (pinfunction "P$1_P$29") (pintype "power_in"))
      (node (ref "P5") (pin "P$30") (pinfunction "P$1_P$30") (pintype "power_in"))
      (node (ref "P5") (pin "P$31") (pinfunction "P$1_P$31") (pintype "power_in"))
      (node (ref "P5") (pin "P$32") (pinfunction "P$1_P$32") (pintype "power_in"))
      (node (ref "P5") (pin "P$33") (pinfunction "P$1_P$33") (pintype "power_in"))
      (node (ref "P5") (pin "P$34") (pinfunction "P$1_P$34") (pintype "power_in"))
      (node (ref "P5") (pin "P$35") (pinfunction "P$1_P$35") (pintype "power_in"))
      (node (ref "P5") (pin "P$36") (pinfunction "P$1_P$36") (pintype "power_in"))
      (node (ref "P5") (pin "P$37") (pinfunction "P$1_P$37") (pintype "power_in"))
      (node (ref "P5") (pin "P$38") (pinfunction "P$1_P$38") (pintype "power_in"))
      (node (ref "P5") (pin "P$39") (pinfunction "P$1_P$39") (pintype "power_in"))
      (node (ref "P5") (pin "P$40") (pinfunction "P$1_P$40") (pintype "power_in"))
      (node (ref "P5") (pin "P$41") (pinfunction "P$1_P$41") (pintype "power_in"))
      (node (ref "P5") (pin "P$42") (pinfunction "P$1_P$42") (pintype "power_in"))
      (node (ref "P5") (pin "P$43") (pinfunction "P$1_P$43") (pintype "power_in"))
      (node (ref "P5") (pin "P$44") (pinfunction "P$1_P$44") (pintype "power_in"))
      (node (ref "P5") (pin "P$45") (pinfunction "P$1_P$45") (pintype "power_in"))
      (node (ref "P5") (pin "P$46") (pinfunction "P$1_P$46") (pintype "power_in"))
      (node (ref "P5") (pin "P$47") (pinfunction "P$1_P$47") (pintype "power_in"))
      (node (ref "P5") (pin "P$48") (pinfunction "P$1_P$48") (pintype "power_in"))
      (node (ref "P5") (pin "P$49") (pinfunction "P$1_P$49") (pintype "power_in"))
      (node (ref "P5") (pin "P$5") (pinfunction "P$1_P$5") (pintype "power_in"))
      (node (ref "P5") (pin "P$50") (pinfunction "P$1_P$50") (pintype "power_in"))
      (node (ref "P5") (pin "P$51") (pinfunction "P$1_P$51") (pintype "power_in"))
      (node (ref "P5") (pin "P$52") (pinfunction "P$1_P$52") (pintype "power_in"))
      (node (ref "P5") (pin "P$53") (pinfunction "P$1_P$53") (pintype "power_in"))
      (node (ref "P5") (pin "P$54") (pinfunction "P$1_P$54") (pintype "power_in"))
      (node (ref "P5") (pin "P$55") (pinfunction "P$1_P$55") (pintype "power_in"))
      (node (ref "P5") (pin "P$56") (pinfunction "P$1_P$56") (pintype "power_in"))
      (node (ref "P5") (pin "P$57") (pinfunction "P$1_P$57") (pintype "power_in"))
      (node (ref "P5") (pin "P$58") (pinfunction "P$1_P$58") (pintype "power_in"))
      (node (ref "P5") (pin "P$59") (pinfunction "P$1_P$59") (pintype "power_in"))
      (node (ref "P5") (pin "P$6") (pinfunction "P$1_P$6") (pintype "power_in"))
      (node (ref "P5") (pin "P$60") (pinfunction "P$1_P$60") (pintype "power_in"))
      (node (ref "P5") (pin "P$61") (pinfunction "P$1_P$61") (pintype "power_in"))
      (node (ref "P5") (pin "P$62") (pinfunction "P$1_P$62") (pintype "power_in"))
      (node (ref "P5") (pin "P$63") (pinfunction "P$1_P$63") (pintype "power_in"))
      (node (ref "P5") (pin "P$64") (pinfunction "P$1_P$64") (pintype "power_in"))
      (node (ref "P5") (pin "P$65") (pinfunction "P$1_P$65") (pintype "power_in"))
      (node (ref "P5") (pin "P$66") (pinfunction "P$1_P$66") (pintype "power_in"))
      (node (ref "P5") (pin "P$67") (pinfunction "P$1_P$67") (pintype "power_in"))
      (node (ref "P5") (pin "P$68") (pinfunction "P$1_P$68") (pintype "power_in"))
      (node (ref "P5") (pin "P$69") (pinfunction "P$1_P$69") (pintype "power_in"))
      (node (ref "P5") (pin "P$7") (pinfunction "P$1_P$7") (pintype "power_in"))
      (node (ref "P5") (pin "P$70") (pinfunction "P$1_P$70") (pintype "power_in"))
      (node (ref "P5") (pin "P$71") (pinfunction "P$1_P$71") (pintype "power_in"))
      (node (ref "P5") (pin "P$72") (pinfunction "P$1_P$72") (pintype "power_in"))
      (node (ref "P5") (pin "P$73") (pinfunction "P$1_P$73") (pintype "power_in"))
      (node (ref "P5") (pin "P$74") (pinfunction "P$1_P$74") (pintype "power_in"))
      (node (ref "P5") (pin "P$75") (pinfunction "P$1_P$75") (pintype "power_in"))
      (node (ref "P5") (pin "P$76") (pinfunction "P$1_P$76") (pintype "power_in"))
      (node (ref "P5") (pin "P$77") (pinfunction "P$1_P$77") (pintype "power_in"))
      (node (ref "P5") (pin "P$78") (pinfunction "P$1_P$78") (pintype "power_in"))
      (node (ref "P5") (pin "P$79") (pinfunction "P$1_P$79") (pintype "power_in"))
      (node (ref "P5") (pin "P$8") (pinfunction "P$1_P$8") (pintype "power_in"))
      (node (ref "P5") (pin "P$80") (pinfunction "P$1_P$80") (pintype "power_in"))
      (node (ref "P5") (pin "P$81") (pinfunction "P$1_P$81") (pintype "power_in"))
      (node (ref "P5") (pin "P$82") (pinfunction "P$1_P$82") (pintype "power_in"))
      (node (ref "P5") (pin "P$83") (pinfunction "P$1_P$83") (pintype "power_in"))
      (node (ref "P5") (pin "P$84") (pinfunction "P$1_P$84") (pintype "power_in"))
      (node (ref "P5") (pin "P$85") (pinfunction "P$1_P$85") (pintype "power_in"))
      (node (ref "P5") (pin "P$86") (pinfunction "P$1_P$86") (pintype "power_in"))
      (node (ref "P5") (pin "P$87") (pinfunction "P$1_P$87") (pintype "power_in"))
      (node (ref "P5") (pin "P$88") (pinfunction "P$1_P$88") (pintype "power_in"))
      (node (ref "P5") (pin "P$89") (pinfunction "P$1_P$89") (pintype "power_in"))
      (node (ref "P5") (pin "P$9") (pinfunction "P$1_P$9") (pintype "power_in"))
      (node (ref "P5") (pin "P$90") (pinfunction "P$1_P$90") (pintype "power_in"))
      (node (ref "P5") (pin "P$91") (pinfunction "P$1_P$91") (pintype "power_in"))
      (node (ref "P5") (pin "P$92") (pinfunction "P$1_P$92") (pintype "power_in"))
      (node (ref "P5") (pin "P$93") (pinfunction "P$1_P$93") (pintype "power_in"))
      (node (ref "P5") (pin "P$94") (pinfunction "P$1_P$94") (pintype "power_in"))
      (node (ref "P5") (pin "P$95") (pinfunction "P$1_P$95") (pintype "power_in"))
      (node (ref "P5") (pin "P$96") (pinfunction "P$1_P$96") (pintype "power_in"))
      (node (ref "P5") (pin "P$97") (pinfunction "P$1_P$97") (pintype "power_in"))
      (node (ref "P5") (pin "P$98") (pinfunction "P$1_P$98") (pintype "power_in"))
      (node (ref "P5") (pin "P$99") (pinfunction "P$1_P$99") (pintype "power_in"))
    )
    (net (code "7") (name "/P6") (class "Default")
      (node (ref "JP1") (pin "P$7") (pinfunction "6_P$7") (pintype "bidirectional"))
      (node (ref "P6") (pin "P$10") (pinfunction "P$1_P$10") (pintype "power_in"))
      (node (ref "P6") (pin "P$100") (pinfunction "P$1_P$100") (pintype "power_in"))
      (node (ref "P6") (pin "P$101") (pinfunction "P$1_P$101") (pintype "power_in"))
      (node (ref "P6") (pin "P$102") (pinfunction "P$1_P$102") (pintype "power_in"))
      (node (ref "P6") (pin "P$103") (pinfunction "P$1_P$103") (pintype "power_in"))
      (node (ref "P6") (pin "P$104") (pinfunction "P$1_P$104") (pintype "power_in"))
      (node (ref "P6") (pin "P$105") (pinfunction "P$1_P$105") (pintype "power_in"))
      (node (ref "P6") (pin "P$106") (pinfunction "P$1_P$106") (pintype "power_in"))
      (node (ref "P6") (pin "P$107") (pinfunction "P$1_P$107") (pintype "power_in"))
      (node (ref "P6") (pin "P$108") (pinfunction "P$1_P$108") (pintype "power_in"))
      (node (ref "P6") (pin "P$109") (pinfunction "P$1_P$109") (pintype "power_in"))
      (node (ref "P6") (pin "P$11") (pinfunction "P$1_P$11") (pintype "power_in"))
      (node (ref "P6") (pin "P$110") (pinfunction "P$1_P$110") (pintype "power_in"))
      (node (ref "P6") (pin "P$111") (pinfunction "P$1_P$111") (pintype "power_in"))
      (node (ref "P6") (pin "P$113") (pinfunction "P$1_P$113") (pintype "power_in"))
      (node (ref "P6") (pin "P$114") (pinfunction "P$1_P$114") (pintype "power_in"))
      (node (ref "P6") (pin "P$115") (pinfunction "P$1_P$115") (pintype "power_in"))
      (node (ref "P6") (pin "P$116") (pinfunction "P$1_P$116") (pintype "power_in"))
      (node (ref "P6") (pin "P$117") (pinfunction "P$1_P$117") (pintype "power_in"))
      (node (ref "P6") (pin "P$118") (pinfunction "P$1_P$118") (pintype "power_in"))
      (node (ref "P6") (pin "P$119") (pinfunction "P$1_P$119") (pintype "power_in"))
      (node (ref "P6") (pin "P$12") (pinfunction "P$1_P$12") (pintype "power_in"))
      (node (ref "P6") (pin "P$120") (pinfunction "P$1_P$120") (pintype "power_in"))
      (node (ref "P6") (pin "P$121") (pinfunction "P$1_P$121") (pintype "power_in"))
      (node (ref "P6") (pin "P$122") (pinfunction "P$1_P$122") (pintype "power_in"))
      (node (ref "P6") (pin "P$123") (pinfunction "P$1_P$123") (pintype "power_in"))
      (node (ref "P6") (pin "P$124") (pinfunction "P$1_P$124") (pintype "power_in"))
      (node (ref "P6") (pin "P$125") (pinfunction "P$1_P$125") (pintype "power_in"))
      (node (ref "P6") (pin "P$126") (pinfunction "P$1_P$126") (pintype "power_in"))
      (node (ref "P6") (pin "P$127") (pinfunction "P$1_P$127") (pintype "power_in"))
      (node (ref "P6") (pin "P$128") (pinfunction "P$1_P$128") (pintype "power_in"))
      (node (ref "P6") (pin "P$129") (pinfunction "P$1_P$129") (pintype "power_in"))
      (node (ref "P6") (pin "P$13") (pinfunction "P$1_P$13") (pintype "power_in"))
      (node (ref "P6") (pin "P$130") (pinfunction "P$1_P$130") (pintype "power_in"))
      (node (ref "P6") (pin "P$131") (pinfunction "P$1_P$131") (pintype "power_in"))
      (node (ref "P6") (pin "P$132") (pinfunction "P$1_P$132") (pintype "power_in"))
      (node (ref "P6") (pin "P$133") (pinfunction "P$1_P$133") (pintype "power_in"))
      (node (ref "P6") (pin "P$134") (pinfunction "P$1_P$134") (pintype "power_in"))
      (node (ref "P6") (pin "P$135") (pinfunction "P$1_P$135") (pintype "power_in"))
      (node (ref "P6") (pin "P$136") (pinfunction "P$1_P$136") (pintype "power_in"))
      (node (ref "P6") (pin "P$137") (pinfunction "P$1_P$137") (pintype "power_in"))
      (node (ref "P6") (pin "P$138") (pinfunction "P$1_P$138") (pintype "power_in"))
      (node (ref "P6") (pin "P$139") (pinfunction "P$1_P$139") (pintype "power_in"))
      (node (ref "P6") (pin "P$14") (pinfunction "P$1_P$14") (pintype "power_in"))
      (node (ref "P6") (pin "P$140") (pinfunction "P$1_P$140") (pintype "power_in"))
      (node (ref "P6") (pin "P$141") (pinfunction "P$1_P$141") (pintype "power_in"))
      (node (ref "P6") (pin "P$142") (pinfunction "P$1_P$142") (pintype "power_in"))
      (node (ref "P6") (pin "P$143") (pinfunction "P$1_P$143") (pintype "power_in"))
      (node (ref "P6") (pin "P$144") (pinfunction "P$1_P$144") (pintype "power_in"))
      (node (ref "P6") (pin "P$145") (pinfunction "P$1_P$145") (pintype "power_in"))
      (node (ref "P6") (pin "P$146") (pinfunction "P$1_P$146") (pintype "power_in"))
      (node (ref "P6") (pin "P$147") (pinfunction "P$1_P$147") (pintype "power_in"))
      (node (ref "P6") (pin "P$148") (pinfunction "P$1_P$148") (pintype "power_in"))
      (node (ref "P6") (pin "P$15") (pinfunction "P$1_P$15") (pintype "power_in"))
      (node (ref "P6") (pin "P$150") (pinfunction "P$1_P$150") (pintype "power_in"))
      (node (ref "P6") (pin "P$151") (pinfunction "P$1_P$151") (pintype "power_in"))
      (node (ref "P6") (pin "P$152") (pinfunction "P$1_P$152") (pintype "power_in"))
      (node (ref "P6") (pin "P$153") (pinfunction "P$1_P$153") (pintype "power_in"))
      (node (ref "P6") (pin "P$154") (pinfunction "P$1_P$154") (pintype "power_in"))
      (node (ref "P6") (pin "P$155") (pinfunction "P$1_P$155") (pintype "power_in"))
      (node (ref "P6") (pin "P$156") (pinfunction "P$1_P$156") (pintype "power_in"))
      (node (ref "P6") (pin "P$157") (pinfunction "P$1_P$157") (pintype "power_in"))
      (node (ref "P6") (pin "P$158") (pinfunction "P$1_P$158") (pintype "power_in"))
      (node (ref "P6") (pin "P$159") (pinfunction "P$1_P$159") (pintype "power_in"))
      (node (ref "P6") (pin "P$16") (pinfunction "P$1_P$16") (pintype "power_in"))
      (node (ref "P6") (pin "P$160") (pinfunction "P$1_P$160") (pintype "power_in"))
      (node (ref "P6") (pin "P$161") (pinfunction "P$1_P$161") (pintype "power_in"))
      (node (ref "P6") (pin "P$162") (pinfunction "P$1_P$162") (pintype "power_in"))
      (node (ref "P6") (pin "P$163") (pinfunction "P$1_P$163") (pintype "power_in"))
      (node (ref "P6") (pin "P$164") (pinfunction "P$1_P$164") (pintype "power_in"))
      (node (ref "P6") (pin "P$165") (pinfunction "P$1_P$165") (pintype "power_in"))
      (node (ref "P6") (pin "P$166") (pinfunction "P$1_P$166") (pintype "power_in"))
      (node (ref "P6") (pin "P$167") (pinfunction "P$1_P$167") (pintype "power_in"))
      (node (ref "P6") (pin "P$168") (pinfunction "P$1_P$168") (pintype "power_in"))
      (node (ref "P6") (pin "P$169") (pinfunction "P$1_P$169") (pintype "power_in"))
      (node (ref "P6") (pin "P$17") (pinfunction "P$1_P$17") (pintype "power_in"))
      (node (ref "P6") (pin "P$170") (pinfunction "P$1_P$170") (pintype "power_in"))
      (node (ref "P6") (pin "P$171") (pinfunction "P$1_P$171") (pintype "power_in"))
      (node (ref "P6") (pin "P$172") (pinfunction "P$1_P$172") (pintype "power_in"))
      (node (ref "P6") (pin "P$173") (pinfunction "P$1_P$173") (pintype "power_in"))
      (node (ref "P6") (pin "P$174") (pinfunction "P$1_P$174") (pintype "power_in"))
      (node (ref "P6") (pin "P$175") (pinfunction "P$1_P$175") (pintype "power_in"))
      (node (ref "P6") (pin "P$176") (pinfunction "P$1_P$176") (pintype "power_in"))
      (node (ref "P6") (pin "P$177") (pinfunction "P$1_P$177") (pintype "power_in"))
      (node (ref "P6") (pin "P$178") (pinfunction "P$1_P$178") (pintype "power_in"))
      (node (ref "P6") (pin "P$179") (pinfunction "P$1_P$179") (pintype "power_in"))
      (node (ref "P6") (pin "P$18") (pinfunction "P$1_P$18") (pintype "power_in"))
      (node (ref "P6") (pin "P$180") (pinfunction "P$1_P$180") (pintype "power_in"))
      (node (ref "P6") (pin "P$181") (pinfunction "P$1_P$181") (pintype "power_in"))
      (node (ref "P6") (pin "P$182") (pinfunction "P$1_P$182") (pintype "power_in"))
      (node (ref "P6") (pin "P$183") (pinfunction "P$1_P$183") (pintype "power_in"))
      (node (ref "P6") (pin "P$184") (pinfunction "P$1_P$184") (pintype "power_in"))
      (node (ref "P6") (pin "P$185") (pinfunction "P$1_P$185") (pintype "power_in"))
      (node (ref "P6") (pin "P$187") (pinfunction "P$1_P$187") (pintype "power_in"))
      (node (ref "P6") (pin "P$188") (pinfunction "P$1_P$188") (pintype "power_in"))
      (node (ref "P6") (pin "P$189") (pinfunction "P$1_P$189") (pintype "power_in"))
      (node (ref "P6") (pin "P$19") (pinfunction "P$1_P$19") (pintype "power_in"))
      (node (ref "P6") (pin "P$190") (pinfunction "P$1_P$190") (pintype "power_in"))
      (node (ref "P6") (pin "P$191") (pinfunction "P$1_P$191") (pintype "power_in"))
      (node (ref "P6") (pin "P$192") (pinfunction "P$1_P$192") (pintype "power_in"))
      (node (ref "P6") (pin "P$193") (pinfunction "P$1_P$193") (pintype "power_in"))
      (node (ref "P6") (pin "P$194") (pinfunction "P$1_P$194") (pintype "power_in"))
      (node (ref "P6") (pin "P$195") (pinfunction "P$1_P$195") (pintype "power_in"))
      (node (ref "P6") (pin "P$196") (pinfunction "P$1_P$196") (pintype "power_in"))
      (node (ref "P6") (pin "P$197") (pinfunction "P$1_P$197") (pintype "power_in"))
      (node (ref "P6") (pin "P$198") (pinfunction "P$1_P$198") (pintype "power_in"))
      (node (ref "P6") (pin "P$199") (pinfunction "P$1_P$199") (pintype "power_in"))
      (node (ref "P6") (pin "P$2") (pinfunction "P$1_P$2") (pintype "power_in"))
      (node (ref "P6") (pin "P$20") (pinfunction "P$1_P$20") (pintype "power_in"))
      (node (ref "P6") (pin "P$200") (pinfunction "P$1_P$200") (pintype "power_in"))
      (node (ref "P6") (pin "P$201") (pinfunction "P$1_P$201") (pintype "power_in"))
      (node (ref "P6") (pin "P$202") (pinfunction "P$1_P$202") (pintype "power_in"))
      (node (ref "P6") (pin "P$203") (pinfunction "P$1_P$203") (pintype "power_in"))
      (node (ref "P6") (pin "P$204") (pinfunction "P$1_P$204") (pintype "power_in"))
      (node (ref "P6") (pin "P$205") (pinfunction "P$1_P$205") (pintype "power_in"))
      (node (ref "P6") (pin "P$206") (pinfunction "P$1_P$206") (pintype "power_in"))
      (node (ref "P6") (pin "P$207") (pinfunction "P$1_P$207") (pintype "power_in"))
      (node (ref "P6") (pin "P$208") (pinfunction "P$1_P$208") (pintype "power_in"))
      (node (ref "P6") (pin "P$209") (pinfunction "P$1_P$209") (pintype "power_in"))
      (node (ref "P6") (pin "P$21") (pinfunction "P$1_P$21") (pintype "power_in"))
      (node (ref "P6") (pin "P$210") (pinfunction "P$1_P$210") (pintype "power_in"))
      (node (ref "P6") (pin "P$211") (pinfunction "P$1_P$211") (pintype "power_in"))
      (node (ref "P6") (pin "P$212") (pinfunction "P$1_P$212") (pintype "power_in"))
      (node (ref "P6") (pin "P$213") (pinfunction "P$1_P$213") (pintype "power_in"))
      (node (ref "P6") (pin "P$214") (pinfunction "P$1_P$214") (pintype "power_in"))
      (node (ref "P6") (pin "P$215") (pinfunction "P$1_P$215") (pintype "power_in"))
      (node (ref "P6") (pin "P$216") (pinfunction "P$1_P$216") (pintype "power_in"))
      (node (ref "P6") (pin "P$217") (pinfunction "P$1_P$217") (pintype "power_in"))
      (node (ref "P6") (pin "P$218") (pinfunction "P$1_P$218") (pintype "power_in"))
      (node (ref "P6") (pin "P$219") (pinfunction "P$1_P$219") (pintype "power_in"))
      (node (ref "P6") (pin "P$22") (pinfunction "P$1_P$22") (pintype "power_in"))
      (node (ref "P6") (pin "P$220") (pinfunction "P$1_P$220") (pintype "power_in"))
      (node (ref "P6") (pin "P$221") (pinfunction "P$1_P$221") (pintype "power_in"))
      (node (ref "P6") (pin "P$222") (pinfunction "P$1_P$222") (pintype "power_in"))
      (node (ref "P6") (pin "P$224") (pinfunction "P$1_P$224") (pintype "power_in"))
      (node (ref "P6") (pin "P$225") (pinfunction "P$1_P$225") (pintype "power_in"))
      (node (ref "P6") (pin "P$226") (pinfunction "P$1_P$226") (pintype "power_in"))
      (node (ref "P6") (pin "P$227") (pinfunction "P$1_P$227") (pintype "power_in"))
      (node (ref "P6") (pin "P$228") (pinfunction "P$1_P$228") (pintype "power_in"))
      (node (ref "P6") (pin "P$229") (pinfunction "P$1_P$229") (pintype "power_in"))
      (node (ref "P6") (pin "P$23") (pinfunction "P$1_P$23") (pintype "power_in"))
      (node (ref "P6") (pin "P$230") (pinfunction "P$1_P$230") (pintype "power_in"))
      (node (ref "P6") (pin "P$231") (pinfunction "P$1_P$231") (pintype "power_in"))
      (node (ref "P6") (pin "P$232") (pinfunction "P$1_P$232") (pintype "power_in"))
      (node (ref "P6") (pin "P$233") (pinfunction "P$1_P$233") (pintype "power_in"))
      (node (ref "P6") (pin "P$234") (pinfunction "P$1_P$234") (pintype "power_in"))
      (node (ref "P6") (pin "P$235") (pinfunction "P$1_P$235") (pintype "power_in"))
      (node (ref "P6") (pin "P$236") (pinfunction "P$1_P$236") (pintype "power_in"))
      (node (ref "P6") (pin "P$237") (pinfunction "P$1_P$237") (pintype "power_in"))
      (node (ref "P6") (pin "P$238") (pinfunction "P$1_P$238") (pintype "power_in"))
      (node (ref "P6") (pin "P$239") (pinfunction "P$1_P$239") (pintype "power_in"))
      (node (ref "P6") (pin "P$24") (pinfunction "P$1_P$24") (pintype "power_in"))
      (node (ref "P6") (pin "P$240") (pinfunction "P$1_P$240") (pintype "power_in"))
      (node (ref "P6") (pin "P$241") (pinfunction "P$1_P$241") (pintype "power_in"))
      (node (ref "P6") (pin "P$242") (pinfunction "P$1_P$242") (pintype "power_in"))
      (node (ref "P6") (pin "P$243") (pinfunction "P$1_P$243") (pintype "power_in"))
      (node (ref "P6") (pin "P$244") (pinfunction "P$1_P$244") (pintype "power_in"))
      (node (ref "P6") (pin "P$245") (pinfunction "P$1_P$245") (pintype "power_in"))
      (node (ref "P6") (pin "P$246") (pinfunction "P$1_P$246") (pintype "power_in"))
      (node (ref "P6") (pin "P$247") (pinfunction "P$1_P$247") (pintype "power_in"))
      (node (ref "P6") (pin "P$248") (pinfunction "P$1_P$248") (pintype "power_in"))
      (node (ref "P6") (pin "P$249") (pinfunction "P$1_P$249") (pintype "power_in"))
      (node (ref "P6") (pin "P$25") (pinfunction "P$1_P$25") (pintype "power_in"))
      (node (ref "P6") (pin "P$250") (pinfunction "P$1_P$250") (pintype "power_in"))
      (node (ref "P6") (pin "P$251") (pinfunction "P$1_P$251") (pintype "power_in"))
      (node (ref "P6") (pin "P$252") (pinfunction "P$1_P$252") (pintype "power_in"))
      (node (ref "P6") (pin "P$253") (pinfunction "P$1_P$253") (pintype "power_in"))
      (node (ref "P6") (pin "P$254") (pinfunction "P$1_P$254") (pintype "power_in"))
      (node (ref "P6") (pin "P$255") (pinfunction "P$1_P$255") (pintype "power_in"))
      (node (ref "P6") (pin "P$256") (pinfunction "P$1_P$256") (pintype "power_in"))
      (node (ref "P6") (pin "P$257") (pinfunction "P$1_P$257") (pintype "power_in"))
      (node (ref "P6") (pin "P$258") (pinfunction "P$1_P$258") (pintype "power_in"))
      (node (ref "P6") (pin "P$259") (pinfunction "P$1_P$259") (pintype "power_in"))
      (node (ref "P6") (pin "P$26") (pinfunction "P$1_P$26") (pintype "power_in"))
      (node (ref "P6") (pin "P$261") (pinfunction "P$1_P$261") (pintype "power_in"))
      (node (ref "P6") (pin "P$262") (pinfunction "P$1_P$262") (pintype "power_in"))
      (node (ref "P6") (pin "P$263") (pinfunction "P$1_P$263") (pintype "power_in"))
      (node (ref "P6") (pin "P$264") (pinfunction "P$1_P$264") (pintype "power_in"))
      (node (ref "P6") (pin "P$265") (pinfunction "P$1_P$265") (pintype "power_in"))
      (node (ref "P6") (pin "P$266") (pinfunction "P$1_P$266") (pintype "power_in"))
      (node (ref "P6") (pin "P$267") (pinfunction "P$1_P$267") (pintype "power_in"))
      (node (ref "P6") (pin "P$268") (pinfunction "P$1_P$268") (pintype "power_in"))
      (node (ref "P6") (pin "P$269") (pinfunction "P$1_P$269") (pintype "power_in"))
      (node (ref "P6") (pin "P$27") (pinfunction "P$1_P$27") (pintype "power_in"))
      (node (ref "P6") (pin "P$270") (pinfunction "P$1_P$270") (pintype "power_in"))
      (node (ref "P6") (pin "P$271") (pinfunction "P$1_P$271") (pintype "power_in"))
      (node (ref "P6") (pin "P$272") (pinfunction "P$1_P$272") (pintype "power_in"))
      (node (ref "P6") (pin "P$273") (pinfunction "P$1_P$273") (pintype "power_in"))
      (node (ref "P6") (pin "P$274") (pinfunction "P$1_P$274") (pintype "power_in"))
      (node (ref "P6") (pin "P$275") (pinfunction "P$1_P$275") (pintype "power_in"))
      (node (ref "P6") (pin "P$276") (pinfunction "P$1_P$276") (pintype "power_in"))
      (node (ref "P6") (pin "P$277") (pinfunction "P$1_P$277") (pintype "power_in"))
      (node (ref "P6") (pin "P$278") (pinfunction "P$1_P$278") (pintype "power_in"))
      (node (ref "P6") (pin "P$279") (pinfunction "P$1_P$279") (pintype "power_in"))
      (node (ref "P6") (pin "P$28") (pinfunction "P$1_P$28") (pintype "power_in"))
      (node (ref "P6") (pin "P$280") (pinfunction "P$1_P$280") (pintype "power_in"))
      (node (ref "P6") (pin "P$281") (pinfunction "P$1_P$281") (pintype "power_in"))
      (node (ref "P6") (pin "P$282") (pinfunction "P$1_P$282") (pintype "power_in"))
      (node (ref "P6") (pin "P$283") (pinfunction "P$1_P$283") (pintype "power_in"))
      (node (ref "P6") (pin "P$284") (pinfunction "P$1_P$284") (pintype "power_in"))
      (node (ref "P6") (pin "P$285") (pinfunction "P$1_P$285") (pintype "power_in"))
      (node (ref "P6") (pin "P$286") (pinfunction "P$1_P$286") (pintype "power_in"))
      (node (ref "P6") (pin "P$287") (pinfunction "P$1_P$287") (pintype "power_in"))
      (node (ref "P6") (pin "P$288") (pinfunction "P$1_P$288") (pintype "power_in"))
      (node (ref "P6") (pin "P$289") (pinfunction "P$1_P$289") (pintype "power_in"))
      (node (ref "P6") (pin "P$29") (pinfunction "P$1_P$29") (pintype "power_in"))
      (node (ref "P6") (pin "P$290") (pinfunction "P$1_P$290") (pintype "power_in"))
      (node (ref "P6") (pin "P$291") (pinfunction "P$1_P$291") (pintype "power_in"))
      (node (ref "P6") (pin "P$292") (pinfunction "P$1_P$292") (pintype "power_in"))
      (node (ref "P6") (pin "P$293") (pinfunction "P$1_P$293") (pintype "power_in"))
      (node (ref "P6") (pin "P$294") (pinfunction "P$1_P$294") (pintype "power_in"))
      (node (ref "P6") (pin "P$295") (pinfunction "P$1_P$295") (pintype "power_in"))
      (node (ref "P6") (pin "P$296") (pinfunction "P$1_P$296") (pintype "power_in"))
      (node (ref "P6") (pin "P$3") (pinfunction "P$1_P$3") (pintype "power_in"))
      (node (ref "P6") (pin "P$30") (pinfunction "P$1_P$30") (pintype "power_in"))
      (node (ref "P6") (pin "P$31") (pinfunction "P$1_P$31") (pintype "power_in"))
      (node (ref "P6") (pin "P$32") (pinfunction "P$1_P$32") (pintype "power_in"))
      (node (ref "P6") (pin "P$33") (pinfunction "P$1_P$33") (pintype "power_in"))
      (node (ref "P6") (pin "P$34") (pinfunction "P$1_P$34") (pintype "power_in"))
      (node (ref "P6") (pin "P$35") (pinfunction "P$1_P$35") (pintype "power_in"))
      (node (ref "P6") (pin "P$36") (pinfunction "P$1_P$36") (pintype "power_in"))
      (node (ref "P6") (pin "P$37") (pinfunction "P$1_P$37") (pintype "power_in"))
      (node (ref "P6") (pin "P$39") (pinfunction "P$1_P$39") (pintype "power_in"))
      (node (ref "P6") (pin "P$4") (pinfunction "P$1_P$4") (pintype "power_in"))
      (node (ref "P6") (pin "P$40") (pinfunction "P$1_P$40") (pintype "power_in"))
      (node (ref "P6") (pin "P$41") (pinfunction "P$1_P$41") (pintype "power_in"))
      (node (ref "P6") (pin "P$42") (pinfunction "P$1_P$42") (pintype "power_in"))
      (node (ref "P6") (pin "P$43") (pinfunction "P$1_P$43") (pintype "power_in"))
      (node (ref "P6") (pin "P$433") (pinfunction "P$1_P$433") (pintype "power_in"))
      (node (ref "P6") (pin "P$434") (pinfunction "P$1_P$434") (pintype "power_in"))
      (node (ref "P6") (pin "P$435") (pinfunction "P$1_P$435") (pintype "power_in"))
      (node (ref "P6") (pin "P$436") (pinfunction "P$1_P$436") (pintype "power_in"))
      (node (ref "P6") (pin "P$437") (pinfunction "P$1_P$437") (pintype "power_in"))
      (node (ref "P6") (pin "P$438") (pinfunction "P$1_P$438") (pintype "power_in"))
      (node (ref "P6") (pin "P$439") (pinfunction "P$1_P$439") (pintype "power_in"))
      (node (ref "P6") (pin "P$44") (pinfunction "P$1_P$44") (pintype "power_in"))
      (node (ref "P6") (pin "P$440") (pinfunction "P$1_P$440") (pintype "power_in"))
      (node (ref "P6") (pin "P$441") (pinfunction "P$1_P$441") (pintype "power_in"))
      (node (ref "P6") (pin "P$442") (pinfunction "P$1_P$442") (pintype "power_in"))
      (node (ref "P6") (pin "P$443") (pinfunction "P$1_P$443") (pintype "power_in"))
      (node (ref "P6") (pin "P$444") (pinfunction "P$1_P$444") (pintype "power_in"))
      (node (ref "P6") (pin "P$445") (pinfunction "P$1_P$445") (pintype "power_in"))
      (node (ref "P6") (pin "P$446") (pinfunction "P$1_P$446") (pintype "power_in"))
      (node (ref "P6") (pin "P$447") (pinfunction "P$1_P$447") (pintype "power_in"))
      (node (ref "P6") (pin "P$448") (pinfunction "P$1_P$448") (pintype "power_in"))
      (node (ref "P6") (pin "P$449") (pinfunction "P$1_P$449") (pintype "power_in"))
      (node (ref "P6") (pin "P$45") (pinfunction "P$1_P$45") (pintype "power_in"))
      (node (ref "P6") (pin "P$450") (pinfunction "P$1_P$450") (pintype "power_in"))
      (node (ref "P6") (pin "P$451") (pinfunction "P$1_P$451") (pintype "power_in"))
      (node (ref "P6") (pin "P$452") (pinfunction "P$1_P$452") (pintype "power_in"))
      (node (ref "P6") (pin "P$453") (pinfunction "P$1_P$453") (pintype "power_in"))
      (node (ref "P6") (pin "P$454") (pinfunction "P$1_P$454") (pintype "power_in"))
      (node (ref "P6") (pin "P$455") (pinfunction "P$1_P$455") (pintype "power_in"))
      (node (ref "P6") (pin "P$456") (pinfunction "P$1_P$456") (pintype "power_in"))
      (node (ref "P6") (pin "P$457") (pinfunction "P$1_P$457") (pintype "power_in"))
      (node (ref "P6") (pin "P$458") (pinfunction "P$1_P$458") (pintype "power_in"))
      (node (ref "P6") (pin "P$459") (pinfunction "P$1_P$459") (pintype "power_in"))
      (node (ref "P6") (pin "P$46") (pinfunction "P$1_P$46") (pintype "power_in"))
      (node (ref "P6") (pin "P$460") (pinfunction "P$1_P$460") (pintype "power_in"))
      (node (ref "P6") (pin "P$461") (pinfunction "P$1_P$461") (pintype "power_in"))
      (node (ref "P6") (pin "P$462") (pinfunction "P$1_P$462") (pintype "power_in"))
      (node (ref "P6") (pin "P$463") (pinfunction "P$1_P$463") (pintype "power_in"))
      (node (ref "P6") (pin "P$464") (pinfunction "P$1_P$464") (pintype "power_in"))
      (node (ref "P6") (pin "P$465") (pinfunction "P$1_P$465") (pintype "power_in"))
      (node (ref "P6") (pin "P$466") (pinfunction "P$1_P$466") (pintype "power_in"))
      (node (ref "P6") (pin "P$467") (pinfunction "P$1_P$467") (pintype "power_in"))
      (node (ref "P6") (pin "P$468") (pinfunction "P$1_P$468") (pintype "power_in"))
      (node (ref "P6") (pin "P$469") (pinfunction "P$1_P$469") (pintype "power_in"))
      (node (ref "P6") (pin "P$47") (pinfunction "P$1_P$47") (pintype "power_in"))
      (node (ref "P6") (pin "P$470") (pinfunction "P$1_P$470") (pintype "power_in"))
      (node (ref "P6") (pin "P$471") (pinfunction "P$1_P$471") (pintype "power_in"))
      (node (ref "P6") (pin "P$472") (pinfunction "P$1_P$472") (pintype "power_in"))
      (node (ref "P6") (pin "P$473") (pinfunction "P$1_P$473") (pintype "power_in"))
      (node (ref "P6") (pin "P$474") (pinfunction "P$1_P$474") (pintype "power_in"))
      (node (ref "P6") (pin "P$475") (pinfunction "P$1_P$475") (pintype "power_in"))
      (node (ref "P6") (pin "P$476") (pinfunction "P$1_P$476") (pintype "power_in"))
      (node (ref "P6") (pin "P$477") (pinfunction "P$1_P$477") (pintype "power_in"))
      (node (ref "P6") (pin "P$478") (pinfunction "P$1_P$478") (pintype "power_in"))
      (node (ref "P6") (pin "P$479") (pinfunction "P$1_P$479") (pintype "power_in"))
      (node (ref "P6") (pin "P$48") (pinfunction "P$1_P$48") (pintype "power_in"))
      (node (ref "P6") (pin "P$480") (pinfunction "P$1_P$480") (pintype "power_in"))
      (node (ref "P6") (pin "P$481") (pinfunction "P$1_P$481") (pintype "power_in"))
      (node (ref "P6") (pin "P$482") (pinfunction "P$1_P$482") (pintype "power_in"))
      (node (ref "P6") (pin "P$483") (pinfunction "P$1_P$483") (pintype "power_in"))
      (node (ref "P6") (pin "P$484") (pinfunction "P$1_P$484") (pintype "power_in"))
      (node (ref "P6") (pin "P$485") (pinfunction "P$1_P$485") (pintype "power_in"))
      (node (ref "P6") (pin "P$486") (pinfunction "P$1_P$486") (pintype "power_in"))
      (node (ref "P6") (pin "P$487") (pinfunction "P$1_P$487") (pintype "power_in"))
      (node (ref "P6") (pin "P$488") (pinfunction "P$1_P$488") (pintype "power_in"))
      (node (ref "P6") (pin "P$489") (pinfunction "P$1_P$489") (pintype "power_in"))
      (node (ref "P6") (pin "P$49") (pinfunction "P$1_P$49") (pintype "power_in"))
      (node (ref "P6") (pin "P$490") (pinfunction "P$1_P$490") (pintype "power_in"))
      (node (ref "P6") (pin "P$491") (pinfunction "P$1_P$491") (pintype "power_in"))
      (node (ref "P6") (pin "P$492") (pinfunction "P$1_P$492") (pintype "power_in"))
      (node (ref "P6") (pin "P$493") (pinfunction "P$1_P$493") (pintype "power_in"))
      (node (ref "P6") (pin "P$494") (pinfunction "P$1_P$494") (pintype "power_in"))
      (node (ref "P6") (pin "P$495") (pinfunction "P$1_P$495") (pintype "power_in"))
      (node (ref "P6") (pin "P$496") (pinfunction "P$1_P$496") (pintype "power_in"))
      (node (ref "P6") (pin "P$497") (pinfunction "P$1_P$497") (pintype "power_in"))
      (node (ref "P6") (pin "P$498") (pinfunction "P$1_P$498") (pintype "power_in"))
      (node (ref "P6") (pin "P$499") (pinfunction "P$1_P$499") (pintype "power_in"))
      (node (ref "P6") (pin "P$5") (pinfunction "P$1_P$5") (pintype "power_in"))
      (node (ref "P6") (pin "P$50") (pinfunction "P$1_P$50") (pintype "power_in"))
      (node (ref "P6") (pin "P$500") (pinfunction "P$1_P$500") (pintype "power_in"))
      (node (ref "P6") (pin "P$501") (pinfunction "P$1_P$501") (pintype "power_in"))
      (node (ref "P6") (pin "P$502") (pinfunction "P$1_P$502") (pintype "power_in"))
      (node (ref "P6") (pin "P$503") (pinfunction "P$1_P$503") (pintype "power_in"))
      (node (ref "P6") (pin "P$504") (pinfunction "P$1_P$504") (pintype "power_in"))
      (node (ref "P6") (pin "P$505") (pinfunction "P$1_P$505") (pintype "power_in"))
      (node (ref "P6") (pin "P$506") (pinfunction "P$1_P$506") (pintype "power_in"))
      (node (ref "P6") (pin "P$507") (pinfunction "P$1_P$507") (pintype "power_in"))
      (node (ref "P6") (pin "P$508") (pinfunction "P$1_P$508") (pintype "power_in"))
      (node (ref "P6") (pin "P$509") (pinfunction "P$1_P$509") (pintype "power_in"))
      (node (ref "P6") (pin "P$51") (pinfunction "P$1_P$51") (pintype "power_in"))
      (node (ref "P6") (pin "P$510") (pinfunction "P$1_P$510") (pintype "power_in"))
      (node (ref "P6") (pin "P$511") (pinfunction "P$1_P$511") (pintype "power_in"))
      (node (ref "P6") (pin "P$512") (pinfunction "P$1_P$512") (pintype "power_in"))
      (node (ref "P6") (pin "P$513") (pinfunction "P$1_P$513") (pintype "power_in"))
      (node (ref "P6") (pin "P$514") (pinfunction "P$1_P$514") (pintype "power_in"))
      (node (ref "P6") (pin "P$515") (pinfunction "P$1_P$515") (pintype "power_in"))
      (node (ref "P6") (pin "P$516") (pinfunction "P$1_P$516") (pintype "power_in"))
      (node (ref "P6") (pin "P$517") (pinfunction "P$1_P$517") (pintype "power_in"))
      (node (ref "P6") (pin "P$518") (pinfunction "P$1_P$518") (pintype "power_in"))
      (node (ref "P6") (pin "P$519") (pinfunction "P$1_P$519") (pintype "power_in"))
      (node (ref "P6") (pin "P$52") (pinfunction "P$1_P$52") (pintype "power_in"))
      (node (ref "P6") (pin "P$520") (pinfunction "P$1_P$520") (pintype "power_in"))
      (node (ref "P6") (pin "P$521") (pinfunction "P$1_P$521") (pintype "power_in"))
      (node (ref "P6") (pin "P$522") (pinfunction "P$1_P$522") (pintype "power_in"))
      (node (ref "P6") (pin "P$523") (pinfunction "P$1_P$523") (pintype "power_in"))
      (node (ref "P6") (pin "P$524") (pinfunction "P$1_P$524") (pintype "power_in"))
      (node (ref "P6") (pin "P$525") (pinfunction "P$1_P$525") (pintype "power_in"))
      (node (ref "P6") (pin "P$526") (pinfunction "P$1_P$526") (pintype "power_in"))
      (node (ref "P6") (pin "P$527") (pinfunction "P$1_P$527") (pintype "power_in"))
      (node (ref "P6") (pin "P$528") (pinfunction "P$1_P$528") (pintype "power_in"))
      (node (ref "P6") (pin "P$529") (pinfunction "P$1_P$529") (pintype "power_in"))
      (node (ref "P6") (pin "P$53") (pinfunction "P$1_P$53") (pintype "power_in"))
      (node (ref "P6") (pin "P$530") (pinfunction "P$1_P$530") (pintype "power_in"))
      (node (ref "P6") (pin "P$531") (pinfunction "P$1_P$531") (pintype "power_in"))
      (node (ref "P6") (pin "P$532") (pinfunction "P$1_P$532") (pintype "power_in"))
      (node (ref "P6") (pin "P$533") (pinfunction "P$1_P$533") (pintype "power_in"))
      (node (ref "P6") (pin "P$534") (pinfunction "P$1_P$534") (pintype "power_in"))
      (node (ref "P6") (pin "P$535") (pinfunction "P$1_P$535") (pintype "power_in"))
      (node (ref "P6") (pin "P$536") (pinfunction "P$1_P$536") (pintype "power_in"))
      (node (ref "P6") (pin "P$537") (pinfunction "P$1_P$537") (pintype "power_in"))
      (node (ref "P6") (pin "P$538") (pinfunction "P$1_P$538") (pintype "power_in"))
      (node (ref "P6") (pin "P$539") (pinfunction "P$1_P$539") (pintype "power_in"))
      (node (ref "P6") (pin "P$54") (pinfunction "P$1_P$54") (pintype "power_in"))
      (node (ref "P6") (pin "P$540") (pinfunction "P$1_P$540") (pintype "power_in"))
      (node (ref "P6") (pin "P$541") (pinfunction "P$1_P$541") (pintype "power_in"))
      (node (ref "P6") (pin "P$542") (pinfunction "P$1_P$542") (pintype "power_in"))
      (node (ref "P6") (pin "P$543") (pinfunction "P$1_P$543") (pintype "power_in"))
      (node (ref "P6") (pin "P$544") (pinfunction "P$1_P$544") (pintype "power_in"))
      (node (ref "P6") (pin "P$545") (pinfunction "P$1_P$545") (pintype "power_in"))
      (node (ref "P6") (pin "P$546") (pinfunction "P$1_P$546") (pintype "power_in"))
      (node (ref "P6") (pin "P$547") (pinfunction "P$1_P$547") (pintype "power_in"))
      (node (ref "P6") (pin "P$548") (pinfunction "P$1_P$548") (pintype "power_in"))
      (node (ref "P6") (pin "P$549") (pinfunction "P$1_P$549") (pintype "power_in"))
      (node (ref "P6") (pin "P$55") (pinfunction "P$1_P$55") (pintype "power_in"))
      (node (ref "P6") (pin "P$550") (pinfunction "P$1_P$550") (pintype "power_in"))
      (node (ref "P6") (pin "P$551") (pinfunction "P$1_P$551") (pintype "power_in"))
      (node (ref "P6") (pin "P$552") (pinfunction "P$1_P$552") (pintype "power_in"))
      (node (ref "P6") (pin "P$553") (pinfunction "P$1_P$553") (pintype "power_in"))
      (node (ref "P6") (pin "P$554") (pinfunction "P$1_P$554") (pintype "power_in"))
      (node (ref "P6") (pin "P$555") (pinfunction "P$1_P$555") (pintype "power_in"))
      (node (ref "P6") (pin "P$556") (pinfunction "P$1_P$556") (pintype "power_in"))
      (node (ref "P6") (pin "P$557") (pinfunction "P$1_P$557") (pintype "power_in"))
      (node (ref "P6") (pin "P$558") (pinfunction "P$1_P$558") (pintype "power_in"))
      (node (ref "P6") (pin "P$559") (pinfunction "P$1_P$559") (pintype "power_in"))
      (node (ref "P6") (pin "P$56") (pinfunction "P$1_P$56") (pintype "power_in"))
      (node (ref "P6") (pin "P$560") (pinfunction "P$1_P$560") (pintype "power_in"))
      (node (ref "P6") (pin "P$561") (pinfunction "P$1_P$561") (pintype "power_in"))
      (node (ref "P6") (pin "P$562") (pinfunction "P$1_P$562") (pintype "power_in"))
      (node (ref "P6") (pin "P$563") (pinfunction "P$1_P$563") (pintype "power_in"))
      (node (ref "P6") (pin "P$564") (pinfunction "P$1_P$564") (pintype "power_in"))
      (node (ref "P6") (pin "P$565") (pinfunction "P$1_P$565") (pintype "power_in"))
      (node (ref "P6") (pin "P$566") (pinfunction "P$1_P$566") (pintype "power_in"))
      (node (ref "P6") (pin "P$567") (pinfunction "P$1_P$567") (pintype "power_in"))
      (node (ref "P6") (pin "P$568") (pinfunction "P$1_P$568") (pintype "power_in"))
      (node (ref "P6") (pin "P$569") (pinfunction "P$1_P$569") (pintype "power_in"))
      (node (ref "P6") (pin "P$57") (pinfunction "P$1_P$57") (pintype "power_in"))
      (node (ref "P6") (pin "P$570") (pinfunction "P$1_P$570") (pintype "power_in"))
      (node (ref "P6") (pin "P$571") (pinfunction "P$1_P$571") (pintype "power_in"))
      (node (ref "P6") (pin "P$572") (pinfunction "P$1_P$572") (pintype "power_in"))
      (node (ref "P6") (pin "P$573") (pinfunction "P$1_P$573") (pintype "power_in"))
      (node (ref "P6") (pin "P$574") (pinfunction "P$1_P$574") (pintype "power_in"))
      (node (ref "P6") (pin "P$575") (pinfunction "P$1_P$575") (pintype "power_in"))
      (node (ref "P6") (pin "P$576") (pinfunction "P$1_P$576") (pintype "power_in"))
      (node (ref "P6") (pin "P$58") (pinfunction "P$1_P$58") (pintype "power_in"))
      (node (ref "P6") (pin "P$59") (pinfunction "P$1_P$59") (pintype "power_in"))
      (node (ref "P6") (pin "P$6") (pinfunction "P$1_P$6") (pintype "power_in"))
      (node (ref "P6") (pin "P$60") (pinfunction "P$1_P$60") (pintype "power_in"))
      (node (ref "P6") (pin "P$61") (pinfunction "P$1_P$61") (pintype "power_in"))
      (node (ref "P6") (pin "P$62") (pinfunction "P$1_P$62") (pintype "power_in"))
      (node (ref "P6") (pin "P$63") (pinfunction "P$1_P$63") (pintype "power_in"))
      (node (ref "P6") (pin "P$64") (pinfunction "P$1_P$64") (pintype "power_in"))
      (node (ref "P6") (pin "P$65") (pinfunction "P$1_P$65") (pintype "power_in"))
      (node (ref "P6") (pin "P$66") (pinfunction "P$1_P$66") (pintype "power_in"))
      (node (ref "P6") (pin "P$67") (pinfunction "P$1_P$67") (pintype "power_in"))
      (node (ref "P6") (pin "P$68") (pinfunction "P$1_P$68") (pintype "power_in"))
      (node (ref "P6") (pin "P$69") (pinfunction "P$1_P$69") (pintype "power_in"))
      (node (ref "P6") (pin "P$7") (pinfunction "P$1_P$7") (pintype "power_in"))
      (node (ref "P6") (pin "P$70") (pinfunction "P$1_P$70") (pintype "power_in"))
      (node (ref "P6") (pin "P$71") (pinfunction "P$1_P$71") (pintype "power_in"))
      (node (ref "P6") (pin "P$72") (pinfunction "P$1_P$72") (pintype "power_in"))
      (node (ref "P6") (pin "P$73") (pinfunction "P$1_P$73") (pintype "power_in"))
      (node (ref "P6") (pin "P$74") (pinfunction "P$1_P$74") (pintype "power_in"))
      (node (ref "P6") (pin "P$76") (pinfunction "P$1_P$76") (pintype "power_in"))
      (node (ref "P6") (pin "P$77") (pinfunction "P$1_P$77") (pintype "power_in"))
      (node (ref "P6") (pin "P$78") (pinfunction "P$1_P$78") (pintype "power_in"))
      (node (ref "P6") (pin "P$79") (pinfunction "P$1_P$79") (pintype "power_in"))
      (node (ref "P6") (pin "P$8") (pinfunction "P$1_P$8") (pintype "power_in"))
      (node (ref "P6") (pin "P$80") (pinfunction "P$1_P$80") (pintype "power_in"))
      (node (ref "P6") (pin "P$81") (pinfunction "P$1_P$81") (pintype "power_in"))
      (node (ref "P6") (pin "P$82") (pinfunction "P$1_P$82") (pintype "power_in"))
      (node (ref "P6") (pin "P$83") (pinfunction "P$1_P$83") (pintype "power_in"))
      (node (ref "P6") (pin "P$84") (pinfunction "P$1_P$84") (pintype "power_in"))
      (node (ref "P6") (pin "P$85") (pinfunction "P$1_P$85") (pintype "power_in"))
      (node (ref "P6") (pin "P$86") (pinfunction "P$1_P$86") (pintype "power_in"))
      (node (ref "P6") (pin "P$87") (pinfunction "P$1_P$87") (pintype "power_in"))
      (node (ref "P6") (pin "P$88") (pinfunction "P$1_P$88") (pintype "power_in"))
      (node (ref "P6") (pin "P$89") (pinfunction "P$1_P$89") (pintype "power_in"))
      (node (ref "P6") (pin "P$9") (pinfunction "P$1_P$9") (pintype "power_in"))
      (node (ref "P6") (pin "P$90") (pinfunction "P$1_P$90") (pintype "power_in"))
      (node (ref "P6") (pin "P$91") (pinfunction "P$1_P$91") (pintype "power_in"))
      (node (ref "P6") (pin "P$92") (pinfunction "P$1_P$92") (pintype "power_in"))
      (node (ref "P6") (pin "P$93") (pinfunction "P$1_P$93") (pintype "power_in"))
      (node (ref "P6") (pin "P$94") (pinfunction "P$1_P$94") (pintype "power_in"))
      (node (ref "P6") (pin "P$95") (pinfunction "P$1_P$95") (pintype "power_in"))
      (node (ref "P6") (pin "P$96") (pinfunction "P$1_P$96") (pintype "power_in"))
      (node (ref "P6") (pin "P$97") (pinfunction "P$1_P$97") (pintype "power_in"))
      (node (ref "P6") (pin "P$98") (pinfunction "P$1_P$98") (pintype "power_in"))
      (node (ref "P6") (pin "P$99") (pinfunction "P$1_P$99") (pintype "power_in"))
    )
    (net (code "8") (name "/P7") (class "Default")
      (node (ref "JP1") (pin "P$8") (pinfunction "7_P$8") (pintype "bidirectional"))
      (node (ref "P7") (pin "P$10") (pinfunction "P$1_P$10") (pintype "power_in"))
      (node (ref "P7") (pin "P$100") (pinfunction "P$1_P$100") (pintype "power_in"))
      (node (ref "P7") (pin "P$101") (pinfunction "P$1_P$101") (pintype "power_in"))
      (node (ref "P7") (pin "P$102") (pinfunction "P$1_P$102") (pintype "power_in"))
      (node (ref "P7") (pin "P$103") (pinfunction "P$1_P$103") (pintype "power_in"))
      (node (ref "P7") (pin "P$104") (pinfunction "P$1_P$104") (pintype "power_in"))
      (node (ref "P7") (pin "P$105") (pinfunction "P$1_P$105") (pintype "power_in"))
      (node (ref "P7") (pin "P$106") (pinfunction "P$1_P$106") (pintype "power_in"))
      (node (ref "P7") (pin "P$107") (pinfunction "P$1_P$107") (pintype "power_in"))
      (node (ref "P7") (pin "P$108") (pinfunction "P$1_P$108") (pintype "power_in"))
      (node (ref "P7") (pin "P$109") (pinfunction "P$1_P$109") (pintype "power_in"))
      (node (ref "P7") (pin "P$11") (pinfunction "P$1_P$11") (pintype "power_in"))
      (node (ref "P7") (pin "P$110") (pinfunction "P$1_P$110") (pintype "power_in"))
      (node (ref "P7") (pin "P$111") (pinfunction "P$1_P$111") (pintype "power_in"))
      (node (ref "P7") (pin "P$112") (pinfunction "P$1_P$112") (pintype "power_in"))
      (node (ref "P7") (pin "P$114") (pinfunction "P$1_P$114") (pintype "power_in"))
      (node (ref "P7") (pin "P$115") (pinfunction "P$1_P$115") (pintype "power_in"))
      (node (ref "P7") (pin "P$116") (pinfunction "P$1_P$116") (pintype "power_in"))
      (node (ref "P7") (pin "P$117") (pinfunction "P$1_P$117") (pintype "power_in"))
      (node (ref "P7") (pin "P$118") (pinfunction "P$1_P$118") (pintype "power_in"))
      (node (ref "P7") (pin "P$119") (pinfunction "P$1_P$119") (pintype "power_in"))
      (node (ref "P7") (pin "P$12") (pinfunction "P$1_P$12") (pintype "power_in"))
      (node (ref "P7") (pin "P$120") (pinfunction "P$1_P$120") (pintype "power_in"))
      (node (ref "P7") (pin "P$121") (pinfunction "P$1_P$121") (pintype "power_in"))
      (node (ref "P7") (pin "P$122") (pinfunction "P$1_P$122") (pintype "power_in"))
      (node (ref "P7") (pin "P$123") (pinfunction "P$1_P$123") (pintype "power_in"))
      (node (ref "P7") (pin "P$124") (pinfunction "P$1_P$124") (pintype "power_in"))
      (node (ref "P7") (pin "P$125") (pinfunction "P$1_P$125") (pintype "power_in"))
      (node (ref "P7") (pin "P$126") (pinfunction "P$1_P$126") (pintype "power_in"))
      (node (ref "P7") (pin "P$127") (pinfunction "P$1_P$127") (pintype "power_in"))
      (node (ref "P7") (pin "P$128") (pinfunction "P$1_P$128") (pintype "power_in"))
      (node (ref "P7") (pin "P$129") (pinfunction "P$1_P$129") (pintype "power_in"))
      (node (ref "P7") (pin "P$13") (pinfunction "P$1_P$13") (pintype "power_in"))
      (node (ref "P7") (pin "P$130") (pinfunction "P$1_P$130") (pintype "power_in"))
      (node (ref "P7") (pin "P$131") (pinfunction "P$1_P$131") (pintype "power_in"))
      (node (ref "P7") (pin "P$132") (pinfunction "P$1_P$132") (pintype "power_in"))
      (node (ref "P7") (pin "P$133") (pinfunction "P$1_P$133") (pintype "power_in"))
      (node (ref "P7") (pin "P$134") (pinfunction "P$1_P$134") (pintype "power_in"))
      (node (ref "P7") (pin "P$135") (pinfunction "P$1_P$135") (pintype "power_in"))
      (node (ref "P7") (pin "P$136") (pinfunction "P$1_P$136") (pintype "power_in"))
      (node (ref "P7") (pin "P$137") (pinfunction "P$1_P$137") (pintype "power_in"))
      (node (ref "P7") (pin "P$138") (pinfunction "P$1_P$138") (pintype "power_in"))
      (node (ref "P7") (pin "P$139") (pinfunction "P$1_P$139") (pintype "power_in"))
      (node (ref "P7") (pin "P$14") (pinfunction "P$1_P$14") (pintype "power_in"))
      (node (ref "P7") (pin "P$140") (pinfunction "P$1_P$140") (pintype "power_in"))
      (node (ref "P7") (pin "P$141") (pinfunction "P$1_P$141") (pintype "power_in"))
      (node (ref "P7") (pin "P$142") (pinfunction "P$1_P$142") (pintype "power_in"))
      (node (ref "P7") (pin "P$143") (pinfunction "P$1_P$143") (pintype "power_in"))
      (node (ref "P7") (pin "P$144") (pinfunction "P$1_P$144") (pintype "power_in"))
      (node (ref "P7") (pin "P$145") (pinfunction "P$1_P$145") (pintype "power_in"))
      (node (ref "P7") (pin "P$146") (pinfunction "P$1_P$146") (pintype "power_in"))
      (node (ref "P7") (pin "P$147") (pinfunction "P$1_P$147") (pintype "power_in"))
      (node (ref "P7") (pin "P$148") (pinfunction "P$1_P$148") (pintype "power_in"))
      (node (ref "P7") (pin "P$149") (pinfunction "P$1_P$149") (pintype "power_in"))
      (node (ref "P7") (pin "P$15") (pinfunction "P$1_P$15") (pintype "power_in"))
      (node (ref "P7") (pin "P$151") (pinfunction "P$1_P$151") (pintype "power_in"))
      (node (ref "P7") (pin "P$152") (pinfunction "P$1_P$152") (pintype "power_in"))
      (node (ref "P7") (pin "P$153") (pinfunction "P$1_P$153") (pintype "power_in"))
      (node (ref "P7") (pin "P$154") (pinfunction "P$1_P$154") (pintype "power_in"))
      (node (ref "P7") (pin "P$155") (pinfunction "P$1_P$155") (pintype "power_in"))
      (node (ref "P7") (pin "P$156") (pinfunction "P$1_P$156") (pintype "power_in"))
      (node (ref "P7") (pin "P$157") (pinfunction "P$1_P$157") (pintype "power_in"))
      (node (ref "P7") (pin "P$158") (pinfunction "P$1_P$158") (pintype "power_in"))
      (node (ref "P7") (pin "P$159") (pinfunction "P$1_P$159") (pintype "power_in"))
      (node (ref "P7") (pin "P$16") (pinfunction "P$1_P$16") (pintype "power_in"))
      (node (ref "P7") (pin "P$160") (pinfunction "P$1_P$160") (pintype "power_in"))
      (node (ref "P7") (pin "P$161") (pinfunction "P$1_P$161") (pintype "power_in"))
      (node (ref "P7") (pin "P$162") (pinfunction "P$1_P$162") (pintype "power_in"))
      (node (ref "P7") (pin "P$163") (pinfunction "P$1_P$163") (pintype "power_in"))
      (node (ref "P7") (pin "P$164") (pinfunction "P$1_P$164") (pintype "power_in"))
      (node (ref "P7") (pin "P$165") (pinfunction "P$1_P$165") (pintype "power_in"))
      (node (ref "P7") (pin "P$166") (pinfunction "P$1_P$166") (pintype "power_in"))
      (node (ref "P7") (pin "P$167") (pinfunction "P$1_P$167") (pintype "power_in"))
      (node (ref "P7") (pin "P$168") (pinfunction "P$1_P$168") (pintype "power_in"))
      (node (ref "P7") (pin "P$169") (pinfunction "P$1_P$169") (pintype "power_in"))
      (node (ref "P7") (pin "P$17") (pinfunction "P$1_P$17") (pintype "power_in"))
      (node (ref "P7") (pin "P$170") (pinfunction "P$1_P$170") (pintype "power_in"))
      (node (ref "P7") (pin "P$171") (pinfunction "P$1_P$171") (pintype "power_in"))
      (node (ref "P7") (pin "P$172") (pinfunction "P$1_P$172") (pintype "power_in"))
      (node (ref "P7") (pin "P$173") (pinfunction "P$1_P$173") (pintype "power_in"))
      (node (ref "P7") (pin "P$174") (pinfunction "P$1_P$174") (pintype "power_in"))
      (node (ref "P7") (pin "P$175") (pinfunction "P$1_P$175") (pintype "power_in"))
      (node (ref "P7") (pin "P$176") (pinfunction "P$1_P$176") (pintype "power_in"))
      (node (ref "P7") (pin "P$177") (pinfunction "P$1_P$177") (pintype "power_in"))
      (node (ref "P7") (pin "P$178") (pinfunction "P$1_P$178") (pintype "power_in"))
      (node (ref "P7") (pin "P$179") (pinfunction "P$1_P$179") (pintype "power_in"))
      (node (ref "P7") (pin "P$18") (pinfunction "P$1_P$18") (pintype "power_in"))
      (node (ref "P7") (pin "P$180") (pinfunction "P$1_P$180") (pintype "power_in"))
      (node (ref "P7") (pin "P$181") (pinfunction "P$1_P$181") (pintype "power_in"))
      (node (ref "P7") (pin "P$182") (pinfunction "P$1_P$182") (pintype "power_in"))
      (node (ref "P7") (pin "P$183") (pinfunction "P$1_P$183") (pintype "power_in"))
      (node (ref "P7") (pin "P$184") (pinfunction "P$1_P$184") (pintype "power_in"))
      (node (ref "P7") (pin "P$185") (pinfunction "P$1_P$185") (pintype "power_in"))
      (node (ref "P7") (pin "P$186") (pinfunction "P$1_P$186") (pintype "power_in"))
      (node (ref "P7") (pin "P$188") (pinfunction "P$1_P$188") (pintype "power_in"))
      (node (ref "P7") (pin "P$189") (pinfunction "P$1_P$189") (pintype "power_in"))
      (node (ref "P7") (pin "P$19") (pinfunction "P$1_P$19") (pintype "power_in"))
      (node (ref "P7") (pin "P$190") (pinfunction "P$1_P$190") (pintype "power_in"))
      (node (ref "P7") (pin "P$191") (pinfunction "P$1_P$191") (pintype "power_in"))
      (node (ref "P7") (pin "P$192") (pinfunction "P$1_P$192") (pintype "power_in"))
      (node (ref "P7") (pin "P$193") (pinfunction "P$1_P$193") (pintype "power_in"))
      (node (ref "P7") (pin "P$194") (pinfunction "P$1_P$194") (pintype "power_in"))
      (node (ref "P7") (pin "P$195") (pinfunction "P$1_P$195") (pintype "power_in"))
      (node (ref "P7") (pin "P$196") (pinfunction "P$1_P$196") (pintype "power_in"))
      (node (ref "P7") (pin "P$197") (pinfunction "P$1_P$197") (pintype "power_in"))
      (node (ref "P7") (pin "P$198") (pinfunction "P$1_P$198") (pintype "power_in"))
      (node (ref "P7") (pin "P$199") (pinfunction "P$1_P$199") (pintype "power_in"))
      (node (ref "P7") (pin "P$20") (pinfunction "P$1_P$20") (pintype "power_in"))
      (node (ref "P7") (pin "P$200") (pinfunction "P$1_P$200") (pintype "power_in"))
      (node (ref "P7") (pin "P$201") (pinfunction "P$1_P$201") (pintype "power_in"))
      (node (ref "P7") (pin "P$202") (pinfunction "P$1_P$202") (pintype "power_in"))
      (node (ref "P7") (pin "P$203") (pinfunction "P$1_P$203") (pintype "power_in"))
      (node (ref "P7") (pin "P$204") (pinfunction "P$1_P$204") (pintype "power_in"))
      (node (ref "P7") (pin "P$205") (pinfunction "P$1_P$205") (pintype "power_in"))
      (node (ref "P7") (pin "P$206") (pinfunction "P$1_P$206") (pintype "power_in"))
      (node (ref "P7") (pin "P$207") (pinfunction "P$1_P$207") (pintype "power_in"))
      (node (ref "P7") (pin "P$208") (pinfunction "P$1_P$208") (pintype "power_in"))
      (node (ref "P7") (pin "P$209") (pinfunction "P$1_P$209") (pintype "power_in"))
      (node (ref "P7") (pin "P$21") (pinfunction "P$1_P$21") (pintype "power_in"))
      (node (ref "P7") (pin "P$210") (pinfunction "P$1_P$210") (pintype "power_in"))
      (node (ref "P7") (pin "P$211") (pinfunction "P$1_P$211") (pintype "power_in"))
      (node (ref "P7") (pin "P$212") (pinfunction "P$1_P$212") (pintype "power_in"))
      (node (ref "P7") (pin "P$213") (pinfunction "P$1_P$213") (pintype "power_in"))
      (node (ref "P7") (pin "P$214") (pinfunction "P$1_P$214") (pintype "power_in"))
      (node (ref "P7") (pin "P$215") (pinfunction "P$1_P$215") (pintype "power_in"))
      (node (ref "P7") (pin "P$216") (pinfunction "P$1_P$216") (pintype "power_in"))
      (node (ref "P7") (pin "P$217") (pinfunction "P$1_P$217") (pintype "power_in"))
      (node (ref "P7") (pin "P$218") (pinfunction "P$1_P$218") (pintype "power_in"))
      (node (ref "P7") (pin "P$219") (pinfunction "P$1_P$219") (pintype "power_in"))
      (node (ref "P7") (pin "P$22") (pinfunction "P$1_P$22") (pintype "power_in"))
      (node (ref "P7") (pin "P$220") (pinfunction "P$1_P$220") (pintype "power_in"))
      (node (ref "P7") (pin "P$221") (pinfunction "P$1_P$221") (pintype "power_in"))
      (node (ref "P7") (pin "P$222") (pinfunction "P$1_P$222") (pintype "power_in"))
      (node (ref "P7") (pin "P$223") (pinfunction "P$1_P$223") (pintype "power_in"))
      (node (ref "P7") (pin "P$23") (pinfunction "P$1_P$23") (pintype "power_in"))
      (node (ref "P7") (pin "P$24") (pinfunction "P$1_P$24") (pintype "power_in"))
      (node (ref "P7") (pin "P$25") (pinfunction "P$1_P$25") (pintype "power_in"))
      (node (ref "P7") (pin "P$26") (pinfunction "P$1_P$26") (pintype "power_in"))
      (node (ref "P7") (pin "P$27") (pinfunction "P$1_P$27") (pintype "power_in"))
      (node (ref "P7") (pin "P$28") (pinfunction "P$1_P$28") (pintype "power_in"))
      (node (ref "P7") (pin "P$29") (pinfunction "P$1_P$29") (pintype "power_in"))
      (node (ref "P7") (pin "P$30") (pinfunction "P$1_P$30") (pintype "power_in"))
      (node (ref "P7") (pin "P$31") (pinfunction "P$1_P$31") (pintype "power_in"))
      (node (ref "P7") (pin "P$32") (pinfunction "P$1_P$32") (pintype "power_in"))
      (node (ref "P7") (pin "P$33") (pinfunction "P$1_P$33") (pintype "power_in"))
      (node (ref "P7") (pin "P$34") (pinfunction "P$1_P$34") (pintype "power_in"))
      (node (ref "P7") (pin "P$35") (pinfunction "P$1_P$35") (pintype "power_in"))
      (node (ref "P7") (pin "P$36") (pinfunction "P$1_P$36") (pintype "power_in"))
      (node (ref "P7") (pin "P$37") (pinfunction "P$1_P$37") (pintype "power_in"))
      (node (ref "P7") (pin "P$38") (pinfunction "P$1_P$38") (pintype "power_in"))
      (node (ref "P7") (pin "P$39") (pinfunction "P$1_P$39") (pintype "power_in"))
      (node (ref "P7") (pin "P$40") (pinfunction "P$1_P$40") (pintype "power_in"))
      (node (ref "P7") (pin "P$41") (pinfunction "P$1_P$41") (pintype "power_in"))
      (node (ref "P7") (pin "P$42") (pinfunction "P$1_P$42") (pintype "power_in"))
      (node (ref "P7") (pin "P$43") (pinfunction "P$1_P$43") (pintype "power_in"))
      (node (ref "P7") (pin "P$44") (pinfunction "P$1_P$44") (pintype "power_in"))
      (node (ref "P7") (pin "P$45") (pinfunction "P$1_P$45") (pintype "power_in"))
      (node (ref "P7") (pin "P$46") (pinfunction "P$1_P$46") (pintype "power_in"))
      (node (ref "P7") (pin "P$47") (pinfunction "P$1_P$47") (pintype "power_in"))
      (node (ref "P7") (pin "P$48") (pinfunction "P$1_P$48") (pintype "power_in"))
      (node (ref "P7") (pin "P$49") (pinfunction "P$1_P$49") (pintype "power_in"))
      (node (ref "P7") (pin "P$5") (pinfunction "P$1_P$5") (pintype "power_in"))
      (node (ref "P7") (pin "P$50") (pinfunction "P$1_P$50") (pintype "power_in"))
      (node (ref "P7") (pin "P$51") (pinfunction "P$1_P$51") (pintype "power_in"))
      (node (ref "P7") (pin "P$52") (pinfunction "P$1_P$52") (pintype "power_in"))
      (node (ref "P7") (pin "P$53") (pinfunction "P$1_P$53") (pintype "power_in"))
      (node (ref "P7") (pin "P$54") (pinfunction "P$1_P$54") (pintype "power_in"))
      (node (ref "P7") (pin "P$55") (pinfunction "P$1_P$55") (pintype "power_in"))
      (node (ref "P7") (pin "P$56") (pinfunction "P$1_P$56") (pintype "power_in"))
      (node (ref "P7") (pin "P$57") (pinfunction "P$1_P$57") (pintype "power_in"))
      (node (ref "P7") (pin "P$58") (pinfunction "P$1_P$58") (pintype "power_in"))
      (node (ref "P7") (pin "P$59") (pinfunction "P$1_P$59") (pintype "power_in"))
      (node (ref "P7") (pin "P$6") (pinfunction "P$1_P$6") (pintype "power_in"))
      (node (ref "P7") (pin "P$60") (pinfunction "P$1_P$60") (pintype "power_in"))
      (node (ref "P7") (pin "P$61") (pinfunction "P$1_P$61") (pintype "power_in"))
      (node (ref "P7") (pin "P$62") (pinfunction "P$1_P$62") (pintype "power_in"))
      (node (ref "P7") (pin "P$63") (pinfunction "P$1_P$63") (pintype "power_in"))
      (node (ref "P7") (pin "P$64") (pinfunction "P$1_P$64") (pintype "power_in"))
      (node (ref "P7") (pin "P$65") (pinfunction "P$1_P$65") (pintype "power_in"))
      (node (ref "P7") (pin "P$66") (pinfunction "P$1_P$66") (pintype "power_in"))
      (node (ref "P7") (pin "P$67") (pinfunction "P$1_P$67") (pintype "power_in"))
      (node (ref "P7") (pin "P$68") (pinfunction "P$1_P$68") (pintype "power_in"))
      (node (ref "P7") (pin "P$69") (pinfunction "P$1_P$69") (pintype "power_in"))
      (node (ref "P7") (pin "P$7") (pinfunction "P$1_P$7") (pintype "power_in"))
      (node (ref "P7") (pin "P$70") (pinfunction "P$1_P$70") (pintype "power_in"))
      (node (ref "P7") (pin "P$71") (pinfunction "P$1_P$71") (pintype "power_in"))
      (node (ref "P7") (pin "P$72") (pinfunction "P$1_P$72") (pintype "power_in"))
      (node (ref "P7") (pin "P$73") (pinfunction "P$1_P$73") (pintype "power_in"))
      (node (ref "P7") (pin "P$74") (pinfunction "P$1_P$74") (pintype "power_in"))
      (node (ref "P7") (pin "P$75") (pinfunction "P$1_P$75") (pintype "power_in"))
      (node (ref "P7") (pin "P$76") (pinfunction "P$1_P$76") (pintype "power_in"))
      (node (ref "P7") (pin "P$77") (pinfunction "P$1_P$77") (pintype "power_in"))
      (node (ref "P7") (pin "P$78") (pinfunction "P$1_P$78") (pintype "power_in"))
      (node (ref "P7") (pin "P$79") (pinfunction "P$1_P$79") (pintype "power_in"))
      (node (ref "P7") (pin "P$8") (pinfunction "P$1_P$8") (pintype "power_in"))
      (node (ref "P7") (pin "P$80") (pinfunction "P$1_P$80") (pintype "power_in"))
      (node (ref "P7") (pin "P$81") (pinfunction "P$1_P$81") (pintype "power_in"))
      (node (ref "P7") (pin "P$82") (pinfunction "P$1_P$82") (pintype "power_in"))
      (node (ref "P7") (pin "P$83") (pinfunction "P$1_P$83") (pintype "power_in"))
      (node (ref "P7") (pin "P$84") (pinfunction "P$1_P$84") (pintype "power_in"))
      (node (ref "P7") (pin "P$85") (pinfunction "P$1_P$85") (pintype "power_in"))
      (node (ref "P7") (pin "P$86") (pinfunction "P$1_P$86") (pintype "power_in"))
      (node (ref "P7") (pin "P$87") (pinfunction "P$1_P$87") (pintype "power_in"))
      (node (ref "P7") (pin "P$88") (pinfunction "P$1_P$88") (pintype "power_in"))
      (node (ref "P7") (pin "P$89") (pinfunction "P$1_P$89") (pintype "power_in"))
      (node (ref "P7") (pin "P$9") (pinfunction "P$1_P$9") (pintype "power_in"))
      (node (ref "P7") (pin "P$90") (pinfunction "P$1_P$90") (pintype "power_in"))
      (node (ref "P7") (pin "P$91") (pinfunction "P$1_P$91") (pintype "power_in"))
      (node (ref "P7") (pin "P$92") (pinfunction "P$1_P$92") (pintype "power_in"))
      (node (ref "P7") (pin "P$93") (pinfunction "P$1_P$93") (pintype "power_in"))
      (node (ref "P7") (pin "P$94") (pinfunction "P$1_P$94") (pintype "power_in"))
      (node (ref "P7") (pin "P$95") (pinfunction "P$1_P$95") (pintype "power_in"))
      (node (ref "P7") (pin "P$96") (pinfunction "P$1_P$96") (pintype "power_in"))
      (node (ref "P7") (pin "P$97") (pinfunction "P$1_P$97") (pintype "power_in"))
      (node (ref "P7") (pin "P$98") (pinfunction "P$1_P$98") (pintype "power_in"))
      (node (ref "P7") (pin "P$99") (pinfunction "P$1_P$99") (pintype "power_in"))
    )
    (net (code "9") (name "/P8") (class "Default")
      (node (ref "JP1") (pin "P$9") (pinfunction "8_P$9") (pintype "bidirectional"))
      (node (ref "P8") (pin "P$10") (pinfunction "P$1_P$10") (pintype "power_in"))
      (node (ref "P8") (pin "P$100") (pinfunction "P$1_P$100") (pintype "power_in"))
      (node (ref "P8") (pin "P$101") (pinfunction "P$1_P$101") (pintype "power_in"))
      (node (ref "P8") (pin "P$102") (pinfunction "P$1_P$102") (pintype "power_in"))
      (node (ref "P8") (pin "P$103") (pinfunction "P$1_P$103") (pintype "power_in"))
      (node (ref "P8") (pin "P$104") (pinfunction "P$1_P$104") (pintype "power_in"))
      (node (ref "P8") (pin "P$105") (pinfunction "P$1_P$105") (pintype "power_in"))
      (node (ref "P8") (pin "P$106") (pinfunction "P$1_P$106") (pintype "power_in"))
      (node (ref "P8") (pin "P$107") (pinfunction "P$1_P$107") (pintype "power_in"))
      (node (ref "P8") (pin "P$108") (pinfunction "P$1_P$108") (pintype "power_in"))
      (node (ref "P8") (pin "P$109") (pinfunction "P$1_P$109") (pintype "power_in"))
      (node (ref "P8") (pin "P$11") (pinfunction "P$1_P$11") (pintype "power_in"))
      (node (ref "P8") (pin "P$110") (pinfunction "P$1_P$110") (pintype "power_in"))
      (node (ref "P8") (pin "P$111") (pinfunction "P$1_P$111") (pintype "power_in"))
      (node (ref "P8") (pin "P$112") (pinfunction "P$1_P$112") (pintype "power_in"))
      (node (ref "P8") (pin "P$113") (pinfunction "P$1_P$113") (pintype "power_in"))
      (node (ref "P8") (pin "P$114") (pinfunction "P$1_P$114") (pintype "power_in"))
      (node (ref "P8") (pin "P$116") (pinfunction "P$1_P$116") (pintype "power_in"))
      (node (ref "P8") (pin "P$117") (pinfunction "P$1_P$117") (pintype "power_in"))
      (node (ref "P8") (pin "P$118") (pinfunction "P$1_P$118") (pintype "power_in"))
      (node (ref "P8") (pin "P$119") (pinfunction "P$1_P$119") (pintype "power_in"))
      (node (ref "P8") (pin "P$12") (pinfunction "P$1_P$12") (pintype "power_in"))
      (node (ref "P8") (pin "P$120") (pinfunction "P$1_P$120") (pintype "power_in"))
      (node (ref "P8") (pin "P$121") (pinfunction "P$1_P$121") (pintype "power_in"))
      (node (ref "P8") (pin "P$122") (pinfunction "P$1_P$122") (pintype "power_in"))
      (node (ref "P8") (pin "P$123") (pinfunction "P$1_P$123") (pintype "power_in"))
      (node (ref "P8") (pin "P$124") (pinfunction "P$1_P$124") (pintype "power_in"))
      (node (ref "P8") (pin "P$125") (pinfunction "P$1_P$125") (pintype "power_in"))
      (node (ref "P8") (pin "P$126") (pinfunction "P$1_P$126") (pintype "power_in"))
      (node (ref "P8") (pin "P$127") (pinfunction "P$1_P$127") (pintype "power_in"))
      (node (ref "P8") (pin "P$128") (pinfunction "P$1_P$128") (pintype "power_in"))
      (node (ref "P8") (pin "P$129") (pinfunction "P$1_P$129") (pintype "power_in"))
      (node (ref "P8") (pin "P$13") (pinfunction "P$1_P$13") (pintype "power_in"))
      (node (ref "P8") (pin "P$130") (pinfunction "P$1_P$130") (pintype "power_in"))
      (node (ref "P8") (pin "P$131") (pinfunction "P$1_P$131") (pintype "power_in"))
      (node (ref "P8") (pin "P$132") (pinfunction "P$1_P$132") (pintype "power_in"))
      (node (ref "P8") (pin "P$133") (pinfunction "P$1_P$133") (pintype "power_in"))
      (node (ref "P8") (pin "P$134") (pinfunction "P$1_P$134") (pintype "power_in"))
      (node (ref "P8") (pin "P$135") (pinfunction "P$1_P$135") (pintype "power_in"))
      (node (ref "P8") (pin "P$136") (pinfunction "P$1_P$136") (pintype "power_in"))
      (node (ref "P8") (pin "P$137") (pinfunction "P$1_P$137") (pintype "power_in"))
      (node (ref "P8") (pin "P$138") (pinfunction "P$1_P$138") (pintype "power_in"))
      (node (ref "P8") (pin "P$139") (pinfunction "P$1_P$139") (pintype "power_in"))
      (node (ref "P8") (pin "P$14") (pinfunction "P$1_P$14") (pintype "power_in"))
      (node (ref "P8") (pin "P$140") (pinfunction "P$1_P$140") (pintype "power_in"))
      (node (ref "P8") (pin "P$141") (pinfunction "P$1_P$141") (pintype "power_in"))
      (node (ref "P8") (pin "P$142") (pinfunction "P$1_P$142") (pintype "power_in"))
      (node (ref "P8") (pin "P$143") (pinfunction "P$1_P$143") (pintype "power_in"))
      (node (ref "P8") (pin "P$144") (pinfunction "P$1_P$144") (pintype "power_in"))
      (node (ref "P8") (pin "P$145") (pinfunction "P$1_P$145") (pintype "power_in"))
      (node (ref "P8") (pin "P$146") (pinfunction "P$1_P$146") (pintype "power_in"))
      (node (ref "P8") (pin "P$147") (pinfunction "P$1_P$147") (pintype "power_in"))
      (node (ref "P8") (pin "P$148") (pinfunction "P$1_P$148") (pintype "power_in"))
      (node (ref "P8") (pin "P$149") (pinfunction "P$1_P$149") (pintype "power_in"))
      (node (ref "P8") (pin "P$15") (pinfunction "P$1_P$15") (pintype "power_in"))
      (node (ref "P8") (pin "P$150") (pinfunction "P$1_P$150") (pintype "power_in"))
      (node (ref "P8") (pin "P$151") (pinfunction "P$1_P$151") (pintype "power_in"))
      (node (ref "P8") (pin "P$153") (pinfunction "P$1_P$153") (pintype "power_in"))
      (node (ref "P8") (pin "P$154") (pinfunction "P$1_P$154") (pintype "power_in"))
      (node (ref "P8") (pin "P$155") (pinfunction "P$1_P$155") (pintype "power_in"))
      (node (ref "P8") (pin "P$156") (pinfunction "P$1_P$156") (pintype "power_in"))
      (node (ref "P8") (pin "P$157") (pinfunction "P$1_P$157") (pintype "power_in"))
      (node (ref "P8") (pin "P$158") (pinfunction "P$1_P$158") (pintype "power_in"))
      (node (ref "P8") (pin "P$159") (pinfunction "P$1_P$159") (pintype "power_in"))
      (node (ref "P8") (pin "P$16") (pinfunction "P$1_P$16") (pintype "power_in"))
      (node (ref "P8") (pin "P$160") (pinfunction "P$1_P$160") (pintype "power_in"))
      (node (ref "P8") (pin "P$161") (pinfunction "P$1_P$161") (pintype "power_in"))
      (node (ref "P8") (pin "P$162") (pinfunction "P$1_P$162") (pintype "power_in"))
      (node (ref "P8") (pin "P$163") (pinfunction "P$1_P$163") (pintype "power_in"))
      (node (ref "P8") (pin "P$164") (pinfunction "P$1_P$164") (pintype "power_in"))
      (node (ref "P8") (pin "P$165") (pinfunction "P$1_P$165") (pintype "power_in"))
      (node (ref "P8") (pin "P$166") (pinfunction "P$1_P$166") (pintype "power_in"))
      (node (ref "P8") (pin "P$167") (pinfunction "P$1_P$167") (pintype "power_in"))
      (node (ref "P8") (pin "P$168") (pinfunction "P$1_P$168") (pintype "power_in"))
      (node (ref "P8") (pin "P$169") (pinfunction "P$1_P$169") (pintype "power_in"))
      (node (ref "P8") (pin "P$17") (pinfunction "P$1_P$17") (pintype "power_in"))
      (node (ref "P8") (pin "P$170") (pinfunction "P$1_P$170") (pintype "power_in"))
      (node (ref "P8") (pin "P$171") (pinfunction "P$1_P$171") (pintype "power_in"))
      (node (ref "P8") (pin "P$172") (pinfunction "P$1_P$172") (pintype "power_in"))
      (node (ref "P8") (pin "P$173") (pinfunction "P$1_P$173") (pintype "power_in"))
      (node (ref "P8") (pin "P$174") (pinfunction "P$1_P$174") (pintype "power_in"))
      (node (ref "P8") (pin "P$175") (pinfunction "P$1_P$175") (pintype "power_in"))
      (node (ref "P8") (pin "P$176") (pinfunction "P$1_P$176") (pintype "power_in"))
      (node (ref "P8") (pin "P$177") (pinfunction "P$1_P$177") (pintype "power_in"))
      (node (ref "P8") (pin "P$178") (pinfunction "P$1_P$178") (pintype "power_in"))
      (node (ref "P8") (pin "P$179") (pinfunction "P$1_P$179") (pintype "power_in"))
      (node (ref "P8") (pin "P$18") (pinfunction "P$1_P$18") (pintype "power_in"))
      (node (ref "P8") (pin "P$180") (pinfunction "P$1_P$180") (pintype "power_in"))
      (node (ref "P8") (pin "P$181") (pinfunction "P$1_P$181") (pintype "power_in"))
      (node (ref "P8") (pin "P$182") (pinfunction "P$1_P$182") (pintype "power_in"))
      (node (ref "P8") (pin "P$183") (pinfunction "P$1_P$183") (pintype "power_in"))
      (node (ref "P8") (pin "P$184") (pinfunction "P$1_P$184") (pintype "power_in"))
      (node (ref "P8") (pin "P$185") (pinfunction "P$1_P$185") (pintype "power_in"))
      (node (ref "P8") (pin "P$186") (pinfunction "P$1_P$186") (pintype "power_in"))
      (node (ref "P8") (pin "P$187") (pinfunction "P$1_P$187") (pintype "power_in"))
      (node (ref "P8") (pin "P$188") (pinfunction "P$1_P$188") (pintype "power_in"))
      (node (ref "P8") (pin "P$19") (pinfunction "P$1_P$19") (pintype "power_in"))
      (node (ref "P8") (pin "P$190") (pinfunction "P$1_P$190") (pintype "power_in"))
      (node (ref "P8") (pin "P$191") (pinfunction "P$1_P$191") (pintype "power_in"))
      (node (ref "P8") (pin "P$192") (pinfunction "P$1_P$192") (pintype "power_in"))
      (node (ref "P8") (pin "P$193") (pinfunction "P$1_P$193") (pintype "power_in"))
      (node (ref "P8") (pin "P$194") (pinfunction "P$1_P$194") (pintype "power_in"))
      (node (ref "P8") (pin "P$195") (pinfunction "P$1_P$195") (pintype "power_in"))
      (node (ref "P8") (pin "P$196") (pinfunction "P$1_P$196") (pintype "power_in"))
      (node (ref "P8") (pin "P$197") (pinfunction "P$1_P$197") (pintype "power_in"))
      (node (ref "P8") (pin "P$198") (pinfunction "P$1_P$198") (pintype "power_in"))
      (node (ref "P8") (pin "P$199") (pinfunction "P$1_P$199") (pintype "power_in"))
      (node (ref "P8") (pin "P$20") (pinfunction "P$1_P$20") (pintype "power_in"))
      (node (ref "P8") (pin "P$200") (pinfunction "P$1_P$200") (pintype "power_in"))
      (node (ref "P8") (pin "P$201") (pinfunction "P$1_P$201") (pintype "power_in"))
      (node (ref "P8") (pin "P$202") (pinfunction "P$1_P$202") (pintype "power_in"))
      (node (ref "P8") (pin "P$203") (pinfunction "P$1_P$203") (pintype "power_in"))
      (node (ref "P8") (pin "P$204") (pinfunction "P$1_P$204") (pintype "power_in"))
      (node (ref "P8") (pin "P$205") (pinfunction "P$1_P$205") (pintype "power_in"))
      (node (ref "P8") (pin "P$206") (pinfunction "P$1_P$206") (pintype "power_in"))
      (node (ref "P8") (pin "P$207") (pinfunction "P$1_P$207") (pintype "power_in"))
      (node (ref "P8") (pin "P$208") (pinfunction "P$1_P$208") (pintype "power_in"))
      (node (ref "P8") (pin "P$209") (pinfunction "P$1_P$209") (pintype "power_in"))
      (node (ref "P8") (pin "P$21") (pinfunction "P$1_P$21") (pintype "power_in"))
      (node (ref "P8") (pin "P$210") (pinfunction "P$1_P$210") (pintype "power_in"))
      (node (ref "P8") (pin "P$211") (pinfunction "P$1_P$211") (pintype "power_in"))
      (node (ref "P8") (pin "P$212") (pinfunction "P$1_P$212") (pintype "power_in"))
      (node (ref "P8") (pin "P$213") (pinfunction "P$1_P$213") (pintype "power_in"))
      (node (ref "P8") (pin "P$214") (pinfunction "P$1_P$214") (pintype "power_in"))
      (node (ref "P8") (pin "P$215") (pinfunction "P$1_P$215") (pintype "power_in"))
      (node (ref "P8") (pin "P$216") (pinfunction "P$1_P$216") (pintype "power_in"))
      (node (ref "P8") (pin "P$217") (pinfunction "P$1_P$217") (pintype "power_in"))
      (node (ref "P8") (pin "P$218") (pinfunction "P$1_P$218") (pintype "power_in"))
      (node (ref "P8") (pin "P$219") (pinfunction "P$1_P$219") (pintype "power_in"))
      (node (ref "P8") (pin "P$22") (pinfunction "P$1_P$22") (pintype "power_in"))
      (node (ref "P8") (pin "P$220") (pinfunction "P$1_P$220") (pintype "power_in"))
      (node (ref "P8") (pin "P$221") (pinfunction "P$1_P$221") (pintype "power_in"))
      (node (ref "P8") (pin "P$222") (pinfunction "P$1_P$222") (pintype "power_in"))
      (node (ref "P8") (pin "P$223") (pinfunction "P$1_P$223") (pintype "power_in"))
      (node (ref "P8") (pin "P$224") (pinfunction "P$1_P$224") (pintype "power_in"))
      (node (ref "P8") (pin "P$225") (pinfunction "P$1_P$225") (pintype "power_in"))
      (node (ref "P8") (pin "P$23") (pinfunction "P$1_P$23") (pintype "power_in"))
      (node (ref "P8") (pin "P$24") (pinfunction "P$1_P$24") (pintype "power_in"))
      (node (ref "P8") (pin "P$25") (pinfunction "P$1_P$25") (pintype "power_in"))
      (node (ref "P8") (pin "P$26") (pinfunction "P$1_P$26") (pintype "power_in"))
      (node (ref "P8") (pin "P$27") (pinfunction "P$1_P$27") (pintype "power_in"))
      (node (ref "P8") (pin "P$28") (pinfunction "P$1_P$28") (pintype "power_in"))
      (node (ref "P8") (pin "P$29") (pinfunction "P$1_P$29") (pintype "power_in"))
      (node (ref "P8") (pin "P$30") (pinfunction "P$1_P$30") (pintype "power_in"))
      (node (ref "P8") (pin "P$31") (pinfunction "P$1_P$31") (pintype "power_in"))
      (node (ref "P8") (pin "P$32") (pinfunction "P$1_P$32") (pintype "power_in"))
      (node (ref "P8") (pin "P$33") (pinfunction "P$1_P$33") (pintype "power_in"))
      (node (ref "P8") (pin "P$34") (pinfunction "P$1_P$34") (pintype "power_in"))
      (node (ref "P8") (pin "P$35") (pinfunction "P$1_P$35") (pintype "power_in"))
      (node (ref "P8") (pin "P$36") (pinfunction "P$1_P$36") (pintype "power_in"))
      (node (ref "P8") (pin "P$37") (pinfunction "P$1_P$37") (pintype "power_in"))
      (node (ref "P8") (pin "P$38") (pinfunction "P$1_P$38") (pintype "power_in"))
      (node (ref "P8") (pin "P$39") (pinfunction "P$1_P$39") (pintype "power_in"))
      (node (ref "P8") (pin "P$40") (pinfunction "P$1_P$40") (pintype "power_in"))
      (node (ref "P8") (pin "P$42") (pinfunction "P$1_P$42") (pintype "power_in"))
      (node (ref "P8") (pin "P$43") (pinfunction "P$1_P$43") (pintype "power_in"))
      (node (ref "P8") (pin "P$44") (pinfunction "P$1_P$44") (pintype "power_in"))
      (node (ref "P8") (pin "P$45") (pinfunction "P$1_P$45") (pintype "power_in"))
      (node (ref "P8") (pin "P$46") (pinfunction "P$1_P$46") (pintype "power_in"))
      (node (ref "P8") (pin "P$47") (pinfunction "P$1_P$47") (pintype "power_in"))
      (node (ref "P8") (pin "P$48") (pinfunction "P$1_P$48") (pintype "power_in"))
      (node (ref "P8") (pin "P$49") (pinfunction "P$1_P$49") (pintype "power_in"))
      (node (ref "P8") (pin "P$5") (pinfunction "P$1_P$5") (pintype "power_in"))
      (node (ref "P8") (pin "P$50") (pinfunction "P$1_P$50") (pintype "power_in"))
      (node (ref "P8") (pin "P$51") (pinfunction "P$1_P$51") (pintype "power_in"))
      (node (ref "P8") (pin "P$52") (pinfunction "P$1_P$52") (pintype "power_in"))
      (node (ref "P8") (pin "P$53") (pinfunction "P$1_P$53") (pintype "power_in"))
      (node (ref "P8") (pin "P$54") (pinfunction "P$1_P$54") (pintype "power_in"))
      (node (ref "P8") (pin "P$55") (pinfunction "P$1_P$55") (pintype "power_in"))
      (node (ref "P8") (pin "P$56") (pinfunction "P$1_P$56") (pintype "power_in"))
      (node (ref "P8") (pin "P$57") (pinfunction "P$1_P$57") (pintype "power_in"))
      (node (ref "P8") (pin "P$58") (pinfunction "P$1_P$58") (pintype "power_in"))
      (node (ref "P8") (pin "P$59") (pinfunction "P$1_P$59") (pintype "power_in"))
      (node (ref "P8") (pin "P$6") (pinfunction "P$1_P$6") (pintype "power_in"))
      (node (ref "P8") (pin "P$60") (pinfunction "P$1_P$60") (pintype "power_in"))
      (node (ref "P8") (pin "P$61") (pinfunction "P$1_P$61") (pintype "power_in"))
      (node (ref "P8") (pin "P$62") (pinfunction "P$1_P$62") (pintype "power_in"))
      (node (ref "P8") (pin "P$63") (pinfunction "P$1_P$63") (pintype "power_in"))
      (node (ref "P8") (pin "P$64") (pinfunction "P$1_P$64") (pintype "power_in"))
      (node (ref "P8") (pin "P$65") (pinfunction "P$1_P$65") (pintype "power_in"))
      (node (ref "P8") (pin "P$66") (pinfunction "P$1_P$66") (pintype "power_in"))
      (node (ref "P8") (pin "P$67") (pinfunction "P$1_P$67") (pintype "power_in"))
      (node (ref "P8") (pin "P$68") (pinfunction "P$1_P$68") (pintype "power_in"))
      (node (ref "P8") (pin "P$69") (pinfunction "P$1_P$69") (pintype "power_in"))
      (node (ref "P8") (pin "P$7") (pinfunction "P$1_P$7") (pintype "power_in"))
      (node (ref "P8") (pin "P$70") (pinfunction "P$1_P$70") (pintype "power_in"))
      (node (ref "P8") (pin "P$71") (pinfunction "P$1_P$71") (pintype "power_in"))
      (node (ref "P8") (pin "P$72") (pinfunction "P$1_P$72") (pintype "power_in"))
      (node (ref "P8") (pin "P$73") (pinfunction "P$1_P$73") (pintype "power_in"))
      (node (ref "P8") (pin "P$74") (pinfunction "P$1_P$74") (pintype "power_in"))
      (node (ref "P8") (pin "P$75") (pinfunction "P$1_P$75") (pintype "power_in"))
      (node (ref "P8") (pin "P$76") (pinfunction "P$1_P$76") (pintype "power_in"))
      (node (ref "P8") (pin "P$77") (pinfunction "P$1_P$77") (pintype "power_in"))
      (node (ref "P8") (pin "P$79") (pinfunction "P$1_P$79") (pintype "power_in"))
      (node (ref "P8") (pin "P$8") (pinfunction "P$1_P$8") (pintype "power_in"))
      (node (ref "P8") (pin "P$80") (pinfunction "P$1_P$80") (pintype "power_in"))
      (node (ref "P8") (pin "P$81") (pinfunction "P$1_P$81") (pintype "power_in"))
      (node (ref "P8") (pin "P$82") (pinfunction "P$1_P$82") (pintype "power_in"))
      (node (ref "P8") (pin "P$83") (pinfunction "P$1_P$83") (pintype "power_in"))
      (node (ref "P8") (pin "P$84") (pinfunction "P$1_P$84") (pintype "power_in"))
      (node (ref "P8") (pin "P$85") (pinfunction "P$1_P$85") (pintype "power_in"))
      (node (ref "P8") (pin "P$86") (pinfunction "P$1_P$86") (pintype "power_in"))
      (node (ref "P8") (pin "P$87") (pinfunction "P$1_P$87") (pintype "power_in"))
      (node (ref "P8") (pin "P$88") (pinfunction "P$1_P$88") (pintype "power_in"))
      (node (ref "P8") (pin "P$89") (pinfunction "P$1_P$89") (pintype "power_in"))
      (node (ref "P8") (pin "P$9") (pinfunction "P$1_P$9") (pintype "power_in"))
      (node (ref "P8") (pin "P$90") (pinfunction "P$1_P$90") (pintype "power_in"))
      (node (ref "P8") (pin "P$91") (pinfunction "P$1_P$91") (pintype "power_in"))
      (node (ref "P8") (pin "P$92") (pinfunction "P$1_P$92") (pintype "power_in"))
      (node (ref "P8") (pin "P$93") (pinfunction "P$1_P$93") (pintype "power_in"))
      (node (ref "P8") (pin "P$94") (pinfunction "P$1_P$94") (pintype "power_in"))
      (node (ref "P8") (pin "P$95") (pinfunction "P$1_P$95") (pintype "power_in"))
      (node (ref "P8") (pin "P$96") (pinfunction "P$1_P$96") (pintype "power_in"))
      (node (ref "P8") (pin "P$97") (pinfunction "P$1_P$97") (pintype "power_in"))
      (node (ref "P8") (pin "P$98") (pinfunction "P$1_P$98") (pintype "power_in"))
      (node (ref "P8") (pin "P$99") (pinfunction "P$1_P$99") (pintype "power_in"))
    )
    (net (code "10") (name "/P9") (class "Default")
      (node (ref "JP1") (pin "P$10") (pinfunction "9_P$10") (pintype "bidirectional"))
      (node (ref "P9") (pin "P$10") (pinfunction "P$1_P$10") (pintype "power_in"))
      (node (ref "P9") (pin "P$100") (pinfunction "P$1_P$100") (pintype "power_in"))
      (node (ref "P9") (pin "P$101") (pinfunction "P$1_P$101") (pintype "power_in"))
      (node (ref "P9") (pin "P$102") (pinfunction "P$1_P$102") (pintype "power_in"))
      (node (ref "P9") (pin "P$103") (pinfunction "P$1_P$103") (pintype "power_in"))
      (node (ref "P9") (pin "P$104") (pinfunction "P$1_P$104") (pintype "power_in"))
      (node (ref "P9") (pin "P$105") (pinfunction "P$1_P$105") (pintype "power_in"))
      (node (ref "P9") (pin "P$106") (pinfunction "P$1_P$106") (pintype "power_in"))
      (node (ref "P9") (pin "P$107") (pinfunction "P$1_P$107") (pintype "power_in"))
      (node (ref "P9") (pin "P$108") (pinfunction "P$1_P$108") (pintype "power_in"))
      (node (ref "P9") (pin "P$109") (pinfunction "P$1_P$109") (pintype "power_in"))
      (node (ref "P9") (pin "P$11") (pinfunction "P$1_P$11") (pintype "power_in"))
      (node (ref "P9") (pin "P$110") (pinfunction "P$1_P$110") (pintype "power_in"))
      (node (ref "P9") (pin "P$111") (pinfunction "P$1_P$111") (pintype "power_in"))
      (node (ref "P9") (pin "P$112") (pinfunction "P$1_P$112") (pintype "power_in"))
      (node (ref "P9") (pin "P$114") (pinfunction "P$1_P$114") (pintype "power_in"))
      (node (ref "P9") (pin "P$115") (pinfunction "P$1_P$115") (pintype "power_in"))
      (node (ref "P9") (pin "P$116") (pinfunction "P$1_P$116") (pintype "power_in"))
      (node (ref "P9") (pin "P$117") (pinfunction "P$1_P$117") (pintype "power_in"))
      (node (ref "P9") (pin "P$118") (pinfunction "P$1_P$118") (pintype "power_in"))
      (node (ref "P9") (pin "P$119") (pinfunction "P$1_P$119") (pintype "power_in"))
      (node (ref "P9") (pin "P$12") (pinfunction "P$1_P$12") (pintype "power_in"))
      (node (ref "P9") (pin "P$120") (pinfunction "P$1_P$120") (pintype "power_in"))
      (node (ref "P9") (pin "P$121") (pinfunction "P$1_P$121") (pintype "power_in"))
      (node (ref "P9") (pin "P$122") (pinfunction "P$1_P$122") (pintype "power_in"))
      (node (ref "P9") (pin "P$123") (pinfunction "P$1_P$123") (pintype "power_in"))
      (node (ref "P9") (pin "P$124") (pinfunction "P$1_P$124") (pintype "power_in"))
      (node (ref "P9") (pin "P$125") (pinfunction "P$1_P$125") (pintype "power_in"))
      (node (ref "P9") (pin "P$126") (pinfunction "P$1_P$126") (pintype "power_in"))
      (node (ref "P9") (pin "P$127") (pinfunction "P$1_P$127") (pintype "power_in"))
      (node (ref "P9") (pin "P$128") (pinfunction "P$1_P$128") (pintype "power_in"))
      (node (ref "P9") (pin "P$129") (pinfunction "P$1_P$129") (pintype "power_in"))
      (node (ref "P9") (pin "P$13") (pinfunction "P$1_P$13") (pintype "power_in"))
      (node (ref "P9") (pin "P$130") (pinfunction "P$1_P$130") (pintype "power_in"))
      (node (ref "P9") (pin "P$131") (pinfunction "P$1_P$131") (pintype "power_in"))
      (node (ref "P9") (pin "P$132") (pinfunction "P$1_P$132") (pintype "power_in"))
      (node (ref "P9") (pin "P$133") (pinfunction "P$1_P$133") (pintype "power_in"))
      (node (ref "P9") (pin "P$134") (pinfunction "P$1_P$134") (pintype "power_in"))
      (node (ref "P9") (pin "P$135") (pinfunction "P$1_P$135") (pintype "power_in"))
      (node (ref "P9") (pin "P$136") (pinfunction "P$1_P$136") (pintype "power_in"))
      (node (ref "P9") (pin "P$137") (pinfunction "P$1_P$137") (pintype "power_in"))
      (node (ref "P9") (pin "P$138") (pinfunction "P$1_P$138") (pintype "power_in"))
      (node (ref "P9") (pin "P$139") (pinfunction "P$1_P$139") (pintype "power_in"))
      (node (ref "P9") (pin "P$14") (pinfunction "P$1_P$14") (pintype "power_in"))
      (node (ref "P9") (pin "P$140") (pinfunction "P$1_P$140") (pintype "power_in"))
      (node (ref "P9") (pin "P$141") (pinfunction "P$1_P$141") (pintype "power_in"))
      (node (ref "P9") (pin "P$142") (pinfunction "P$1_P$142") (pintype "power_in"))
      (node (ref "P9") (pin "P$143") (pinfunction "P$1_P$143") (pintype "power_in"))
      (node (ref "P9") (pin "P$144") (pinfunction "P$1_P$144") (pintype "power_in"))
      (node (ref "P9") (pin "P$145") (pinfunction "P$1_P$145") (pintype "power_in"))
      (node (ref "P9") (pin "P$146") (pinfunction "P$1_P$146") (pintype "power_in"))
      (node (ref "P9") (pin "P$147") (pinfunction "P$1_P$147") (pintype "power_in"))
      (node (ref "P9") (pin "P$148") (pinfunction "P$1_P$148") (pintype "power_in"))
      (node (ref "P9") (pin "P$149") (pinfunction "P$1_P$149") (pintype "power_in"))
      (node (ref "P9") (pin "P$15") (pinfunction "P$1_P$15") (pintype "power_in"))
      (node (ref "P9") (pin "P$151") (pinfunction "P$1_P$151") (pintype "power_in"))
      (node (ref "P9") (pin "P$152") (pinfunction "P$1_P$152") (pintype "power_in"))
      (node (ref "P9") (pin "P$153") (pinfunction "P$1_P$153") (pintype "power_in"))
      (node (ref "P9") (pin "P$154") (pinfunction "P$1_P$154") (pintype "power_in"))
      (node (ref "P9") (pin "P$155") (pinfunction "P$1_P$155") (pintype "power_in"))
      (node (ref "P9") (pin "P$156") (pinfunction "P$1_P$156") (pintype "power_in"))
      (node (ref "P9") (pin "P$157") (pinfunction "P$1_P$157") (pintype "power_in"))
      (node (ref "P9") (pin "P$158") (pinfunction "P$1_P$158") (pintype "power_in"))
      (node (ref "P9") (pin "P$159") (pinfunction "P$1_P$159") (pintype "power_in"))
      (node (ref "P9") (pin "P$16") (pinfunction "P$1_P$16") (pintype "power_in"))
      (node (ref "P9") (pin "P$160") (pinfunction "P$1_P$160") (pintype "power_in"))
      (node (ref "P9") (pin "P$161") (pinfunction "P$1_P$161") (pintype "power_in"))
      (node (ref "P9") (pin "P$162") (pinfunction "P$1_P$162") (pintype "power_in"))
      (node (ref "P9") (pin "P$163") (pinfunction "P$1_P$163") (pintype "power_in"))
      (node (ref "P9") (pin "P$164") (pinfunction "P$1_P$164") (pintype "power_in"))
      (node (ref "P9") (pin "P$165") (pinfunction "P$1_P$165") (pintype "power_in"))
      (node (ref "P9") (pin "P$166") (pinfunction "P$1_P$166") (pintype "power_in"))
      (node (ref "P9") (pin "P$167") (pinfunction "P$1_P$167") (pintype "power_in"))
      (node (ref "P9") (pin "P$168") (pinfunction "P$1_P$168") (pintype "power_in"))
      (node (ref "P9") (pin "P$169") (pinfunction "P$1_P$169") (pintype "power_in"))
      (node (ref "P9") (pin "P$17") (pinfunction "P$1_P$17") (pintype "power_in"))
      (node (ref "P9") (pin "P$170") (pinfunction "P$1_P$170") (pintype "power_in"))
      (node (ref "P9") (pin "P$171") (pinfunction "P$1_P$171") (pintype "power_in"))
      (node (ref "P9") (pin "P$172") (pinfunction "P$1_P$172") (pintype "power_in"))
      (node (ref "P9") (pin "P$173") (pinfunction "P$1_P$173") (pintype "power_in"))
      (node (ref "P9") (pin "P$174") (pinfunction "P$1_P$174") (pintype "power_in"))
      (node (ref "P9") (pin "P$175") (pinfunction "P$1_P$175") (pintype "power_in"))
      (node (ref "P9") (pin "P$176") (pinfunction "P$1_P$176") (pintype "power_in"))
      (node (ref "P9") (pin "P$177") (pinfunction "P$1_P$177") (pintype "power_in"))
      (node (ref "P9") (pin "P$178") (pinfunction "P$1_P$178") (pintype "power_in"))
      (node (ref "P9") (pin "P$179") (pinfunction "P$1_P$179") (pintype "power_in"))
      (node (ref "P9") (pin "P$18") (pinfunction "P$1_P$18") (pintype "power_in"))
      (node (ref "P9") (pin "P$180") (pinfunction "P$1_P$180") (pintype "power_in"))
      (node (ref "P9") (pin "P$181") (pinfunction "P$1_P$181") (pintype "power_in"))
      (node (ref "P9") (pin "P$182") (pinfunction "P$1_P$182") (pintype "power_in"))
      (node (ref "P9") (pin "P$183") (pinfunction "P$1_P$183") (pintype "power_in"))
      (node (ref "P9") (pin "P$184") (pinfunction "P$1_P$184") (pintype "power_in"))
      (node (ref "P9") (pin "P$185") (pinfunction "P$1_P$185") (pintype "power_in"))
      (node (ref "P9") (pin "P$186") (pinfunction "P$1_P$186") (pintype "power_in"))
      (node (ref "P9") (pin "P$188") (pinfunction "P$1_P$188") (pintype "power_in"))
      (node (ref "P9") (pin "P$189") (pinfunction "P$1_P$189") (pintype "power_in"))
      (node (ref "P9") (pin "P$19") (pinfunction "P$1_P$19") (pintype "power_in"))
      (node (ref "P9") (pin "P$190") (pinfunction "P$1_P$190") (pintype "power_in"))
      (node (ref "P9") (pin "P$191") (pinfunction "P$1_P$191") (pintype "power_in"))
      (node (ref "P9") (pin "P$192") (pinfunction "P$1_P$192") (pintype "power_in"))
      (node (ref "P9") (pin "P$193") (pinfunction "P$1_P$193") (pintype "power_in"))
      (node (ref "P9") (pin "P$194") (pinfunction "P$1_P$194") (pintype "power_in"))
      (node (ref "P9") (pin "P$195") (pinfunction "P$1_P$195") (pintype "power_in"))
      (node (ref "P9") (pin "P$196") (pinfunction "P$1_P$196") (pintype "power_in"))
      (node (ref "P9") (pin "P$197") (pinfunction "P$1_P$197") (pintype "power_in"))
      (node (ref "P9") (pin "P$198") (pinfunction "P$1_P$198") (pintype "power_in"))
      (node (ref "P9") (pin "P$199") (pinfunction "P$1_P$199") (pintype "power_in"))
      (node (ref "P9") (pin "P$20") (pinfunction "P$1_P$20") (pintype "power_in"))
      (node (ref "P9") (pin "P$200") (pinfunction "P$1_P$200") (pintype "power_in"))
      (node (ref "P9") (pin "P$201") (pinfunction "P$1_P$201") (pintype "power_in"))
      (node (ref "P9") (pin "P$202") (pinfunction "P$1_P$202") (pintype "power_in"))
      (node (ref "P9") (pin "P$203") (pinfunction "P$1_P$203") (pintype "power_in"))
      (node (ref "P9") (pin "P$204") (pinfunction "P$1_P$204") (pintype "power_in"))
      (node (ref "P9") (pin "P$205") (pinfunction "P$1_P$205") (pintype "power_in"))
      (node (ref "P9") (pin "P$206") (pinfunction "P$1_P$206") (pintype "power_in"))
      (node (ref "P9") (pin "P$207") (pinfunction "P$1_P$207") (pintype "power_in"))
      (node (ref "P9") (pin "P$208") (pinfunction "P$1_P$208") (pintype "power_in"))
      (node (ref "P9") (pin "P$209") (pinfunction "P$1_P$209") (pintype "power_in"))
      (node (ref "P9") (pin "P$21") (pinfunction "P$1_P$21") (pintype "power_in"))
      (node (ref "P9") (pin "P$210") (pinfunction "P$1_P$210") (pintype "power_in"))
      (node (ref "P9") (pin "P$211") (pinfunction "P$1_P$211") (pintype "power_in"))
      (node (ref "P9") (pin "P$212") (pinfunction "P$1_P$212") (pintype "power_in"))
      (node (ref "P9") (pin "P$213") (pinfunction "P$1_P$213") (pintype "power_in"))
      (node (ref "P9") (pin "P$214") (pinfunction "P$1_P$214") (pintype "power_in"))
      (node (ref "P9") (pin "P$215") (pinfunction "P$1_P$215") (pintype "power_in"))
      (node (ref "P9") (pin "P$216") (pinfunction "P$1_P$216") (pintype "power_in"))
      (node (ref "P9") (pin "P$217") (pinfunction "P$1_P$217") (pintype "power_in"))
      (node (ref "P9") (pin "P$218") (pinfunction "P$1_P$218") (pintype "power_in"))
      (node (ref "P9") (pin "P$219") (pinfunction "P$1_P$219") (pintype "power_in"))
      (node (ref "P9") (pin "P$22") (pinfunction "P$1_P$22") (pintype "power_in"))
      (node (ref "P9") (pin "P$220") (pinfunction "P$1_P$220") (pintype "power_in"))
      (node (ref "P9") (pin "P$221") (pinfunction "P$1_P$221") (pintype "power_in"))
      (node (ref "P9") (pin "P$222") (pinfunction "P$1_P$222") (pintype "power_in"))
      (node (ref "P9") (pin "P$223") (pinfunction "P$1_P$223") (pintype "power_in"))
      (node (ref "P9") (pin "P$23") (pinfunction "P$1_P$23") (pintype "power_in"))
      (node (ref "P9") (pin "P$24") (pinfunction "P$1_P$24") (pintype "power_in"))
      (node (ref "P9") (pin "P$25") (pinfunction "P$1_P$25") (pintype "power_in"))
      (node (ref "P9") (pin "P$26") (pinfunction "P$1_P$26") (pintype "power_in"))
      (node (ref "P9") (pin "P$27") (pinfunction "P$1_P$27") (pintype "power_in"))
      (node (ref "P9") (pin "P$28") (pinfunction "P$1_P$28") (pintype "power_in"))
      (node (ref "P9") (pin "P$29") (pinfunction "P$1_P$29") (pintype "power_in"))
      (node (ref "P9") (pin "P$30") (pinfunction "P$1_P$30") (pintype "power_in"))
      (node (ref "P9") (pin "P$31") (pinfunction "P$1_P$31") (pintype "power_in"))
      (node (ref "P9") (pin "P$32") (pinfunction "P$1_P$32") (pintype "power_in"))
      (node (ref "P9") (pin "P$33") (pinfunction "P$1_P$33") (pintype "power_in"))
      (node (ref "P9") (pin "P$34") (pinfunction "P$1_P$34") (pintype "power_in"))
      (node (ref "P9") (pin "P$35") (pinfunction "P$1_P$35") (pintype "power_in"))
      (node (ref "P9") (pin "P$36") (pinfunction "P$1_P$36") (pintype "power_in"))
      (node (ref "P9") (pin "P$37") (pinfunction "P$1_P$37") (pintype "power_in"))
      (node (ref "P9") (pin "P$38") (pinfunction "P$1_P$38") (pintype "power_in"))
      (node (ref "P9") (pin "P$39") (pinfunction "P$1_P$39") (pintype "power_in"))
      (node (ref "P9") (pin "P$40") (pinfunction "P$1_P$40") (pintype "power_in"))
      (node (ref "P9") (pin "P$41") (pinfunction "P$1_P$41") (pintype "power_in"))
      (node (ref "P9") (pin "P$42") (pinfunction "P$1_P$42") (pintype "power_in"))
      (node (ref "P9") (pin "P$43") (pinfunction "P$1_P$43") (pintype "power_in"))
      (node (ref "P9") (pin "P$44") (pinfunction "P$1_P$44") (pintype "power_in"))
      (node (ref "P9") (pin "P$45") (pinfunction "P$1_P$45") (pintype "power_in"))
      (node (ref "P9") (pin "P$46") (pinfunction "P$1_P$46") (pintype "power_in"))
      (node (ref "P9") (pin "P$47") (pinfunction "P$1_P$47") (pintype "power_in"))
      (node (ref "P9") (pin "P$48") (pinfunction "P$1_P$48") (pintype "power_in"))
      (node (ref "P9") (pin "P$49") (pinfunction "P$1_P$49") (pintype "power_in"))
      (node (ref "P9") (pin "P$5") (pinfunction "P$1_P$5") (pintype "power_in"))
      (node (ref "P9") (pin "P$50") (pinfunction "P$1_P$50") (pintype "power_in"))
      (node (ref "P9") (pin "P$51") (pinfunction "P$1_P$51") (pintype "power_in"))
      (node (ref "P9") (pin "P$52") (pinfunction "P$1_P$52") (pintype "power_in"))
      (node (ref "P9") (pin "P$53") (pinfunction "P$1_P$53") (pintype "power_in"))
      (node (ref "P9") (pin "P$54") (pinfunction "P$1_P$54") (pintype "power_in"))
      (node (ref "P9") (pin "P$55") (pinfunction "P$1_P$55") (pintype "power_in"))
      (node (ref "P9") (pin "P$56") (pinfunction "P$1_P$56") (pintype "power_in"))
      (node (ref "P9") (pin "P$57") (pinfunction "P$1_P$57") (pintype "power_in"))
      (node (ref "P9") (pin "P$58") (pinfunction "P$1_P$58") (pintype "power_in"))
      (node (ref "P9") (pin "P$59") (pinfunction "P$1_P$59") (pintype "power_in"))
      (node (ref "P9") (pin "P$6") (pinfunction "P$1_P$6") (pintype "power_in"))
      (node (ref "P9") (pin "P$60") (pinfunction "P$1_P$60") (pintype "power_in"))
      (node (ref "P9") (pin "P$61") (pinfunction "P$1_P$61") (pintype "power_in"))
      (node (ref "P9") (pin "P$62") (pinfunction "P$1_P$62") (pintype "power_in"))
      (node (ref "P9") (pin "P$63") (pinfunction "P$1_P$63") (pintype "power_in"))
      (node (ref "P9") (pin "P$64") (pinfunction "P$1_P$64") (pintype "power_in"))
      (node (ref "P9") (pin "P$65") (pinfunction "P$1_P$65") (pintype "power_in"))
      (node (ref "P9") (pin "P$66") (pinfunction "P$1_P$66") (pintype "power_in"))
      (node (ref "P9") (pin "P$67") (pinfunction "P$1_P$67") (pintype "power_in"))
      (node (ref "P9") (pin "P$68") (pinfunction "P$1_P$68") (pintype "power_in"))
      (node (ref "P9") (pin "P$69") (pinfunction "P$1_P$69") (pintype "power_in"))
      (node (ref "P9") (pin "P$7") (pinfunction "P$1_P$7") (pintype "power_in"))
      (node (ref "P9") (pin "P$70") (pinfunction "P$1_P$70") (pintype "power_in"))
      (node (ref "P9") (pin "P$71") (pinfunction "P$1_P$71") (pintype "power_in"))
      (node (ref "P9") (pin "P$72") (pinfunction "P$1_P$72") (pintype "power_in"))
      (node (ref "P9") (pin "P$73") (pinfunction "P$1_P$73") (pintype "power_in"))
      (node (ref "P9") (pin "P$74") (pinfunction "P$1_P$74") (pintype "power_in"))
      (node (ref "P9") (pin "P$75") (pinfunction "P$1_P$75") (pintype "power_in"))
      (node (ref "P9") (pin "P$76") (pinfunction "P$1_P$76") (pintype "power_in"))
      (node (ref "P9") (pin "P$77") (pinfunction "P$1_P$77") (pintype "power_in"))
      (node (ref "P9") (pin "P$78") (pinfunction "P$1_P$78") (pintype "power_in"))
      (node (ref "P9") (pin "P$79") (pinfunction "P$1_P$79") (pintype "power_in"))
      (node (ref "P9") (pin "P$8") (pinfunction "P$1_P$8") (pintype "power_in"))
      (node (ref "P9") (pin "P$80") (pinfunction "P$1_P$80") (pintype "power_in"))
      (node (ref "P9") (pin "P$81") (pinfunction "P$1_P$81") (pintype "power_in"))
      (node (ref "P9") (pin "P$82") (pinfunction "P$1_P$82") (pintype "power_in"))
      (node (ref "P9") (pin "P$83") (pinfunction "P$1_P$83") (pintype "power_in"))
      (node (ref "P9") (pin "P$84") (pinfunction "P$1_P$84") (pintype "power_in"))
      (node (ref "P9") (pin "P$85") (pinfunction "P$1_P$85") (pintype "power_in"))
      (node (ref "P9") (pin "P$86") (pinfunction "P$1_P$86") (pintype "power_in"))
      (node (ref "P9") (pin "P$87") (pinfunction "P$1_P$87") (pintype "power_in"))
      (node (ref "P9") (pin "P$88") (pinfunction "P$1_P$88") (pintype "power_in"))
      (node (ref "P9") (pin "P$89") (pinfunction "P$1_P$89") (pintype "power_in"))
      (node (ref "P9") (pin "P$9") (pinfunction "P$1_P$9") (pintype "power_in"))
      (node (ref "P9") (pin "P$90") (pinfunction "P$1_P$90") (pintype "power_in"))
      (node (ref "P9") (pin "P$91") (pinfunction "P$1_P$91") (pintype "power_in"))
      (node (ref "P9") (pin "P$92") (pinfunction "P$1_P$92") (pintype "power_in"))
      (node (ref "P9") (pin "P$93") (pinfunction "P$1_P$93") (pintype "power_in"))
      (node (ref "P9") (pin "P$94") (pinfunction "P$1_P$94") (pintype "power_in"))
      (node (ref "P9") (pin "P$95") (pinfunction "P$1_P$95") (pintype "power_in"))
      (node (ref "P9") (pin "P$96") (pinfunction "P$1_P$96") (pintype "power_in"))
      (node (ref "P9") (pin "P$97") (pinfunction "P$1_P$97") (pintype "power_in"))
      (node (ref "P9") (pin "P$98") (pinfunction "P$1_P$98") (pintype "power_in"))
      (node (ref "P9") (pin "P$99") (pinfunction "P$1_P$99") (pintype "power_in"))
    )
    (net (code "11") (name "/P10") (class "Default")
      (node (ref "JP1") (pin "P$11") (pinfunction "10_P$11") (pintype "bidirectional"))
      (node (ref "P10") (pin "P$10") (pinfunction "P$1_P$10") (pintype "power_in"))
      (node (ref "P10") (pin "P$100") (pinfunction "P$1_P$100") (pintype "power_in"))
      (node (ref "P10") (pin "P$101") (pinfunction "P$1_P$101") (pintype "power_in"))
      (node (ref "P10") (pin "P$102") (pinfunction "P$1_P$102") (pintype "power_in"))
      (node (ref "P10") (pin "P$103") (pinfunction "P$1_P$103") (pintype "power_in"))
      (node (ref "P10") (pin "P$104") (pinfunction "P$1_P$104") (pintype "power_in"))
      (node (ref "P10") (pin "P$105") (pinfunction "P$1_P$105") (pintype "power_in"))
      (node (ref "P10") (pin "P$106") (pinfunction "P$1_P$106") (pintype "power_in"))
      (node (ref "P10") (pin "P$107") (pinfunction "P$1_P$107") (pintype "power_in"))
      (node (ref "P10") (pin "P$108") (pinfunction "P$1_P$108") (pintype "power_in"))
      (node (ref "P10") (pin "P$109") (pinfunction "P$1_P$109") (pintype "power_in"))
      (node (ref "P10") (pin "P$11") (pinfunction "P$1_P$11") (pintype "power_in"))
      (node (ref "P10") (pin "P$110") (pinfunction "P$1_P$110") (pintype "power_in"))
      (node (ref "P10") (pin "P$111") (pinfunction "P$1_P$111") (pintype "power_in"))
      (node (ref "P10") (pin "P$112") (pinfunction "P$1_P$112") (pintype "power_in"))
      (node (ref "P10") (pin "P$113") (pinfunction "P$1_P$113") (pintype "power_in"))
      (node (ref "P10") (pin "P$114") (pinfunction "P$1_P$114") (pintype "power_in"))
      (node (ref "P10") (pin "P$116") (pinfunction "P$1_P$116") (pintype "power_in"))
      (node (ref "P10") (pin "P$117") (pinfunction "P$1_P$117") (pintype "power_in"))
      (node (ref "P10") (pin "P$118") (pinfunction "P$1_P$118") (pintype "power_in"))
      (node (ref "P10") (pin "P$119") (pinfunction "P$1_P$119") (pintype "power_in"))
      (node (ref "P10") (pin "P$12") (pinfunction "P$1_P$12") (pintype "power_in"))
      (node (ref "P10") (pin "P$120") (pinfunction "P$1_P$120") (pintype "power_in"))
      (node (ref "P10") (pin "P$121") (pinfunction "P$1_P$121") (pintype "power_in"))
      (node (ref "P10") (pin "P$122") (pinfunction "P$1_P$122") (pintype "power_in"))
      (node (ref "P10") (pin "P$123") (pinfunction "P$1_P$123") (pintype "power_in"))
      (node (ref "P10") (pin "P$124") (pinfunction "P$1_P$124") (pintype "power_in"))
      (node (ref "P10") (pin "P$125") (pinfunction "P$1_P$125") (pintype "power_in"))
      (node (ref "P10") (pin "P$126") (pinfunction "P$1_P$126") (pintype "power_in"))
      (node (ref "P10") (pin "P$127") (pinfunction "P$1_P$127") (pintype "power_in"))
      (node (ref "P10") (pin "P$128") (pinfunction "P$1_P$128") (pintype "power_in"))
      (node (ref "P10") (pin "P$129") (pinfunction "P$1_P$129") (pintype "power_in"))
      (node (ref "P10") (pin "P$13") (pinfunction "P$1_P$13") (pintype "power_in"))
      (node (ref "P10") (pin "P$130") (pinfunction "P$1_P$130") (pintype "power_in"))
      (node (ref "P10") (pin "P$131") (pinfunction "P$1_P$131") (pintype "power_in"))
      (node (ref "P10") (pin "P$132") (pinfunction "P$1_P$132") (pintype "power_in"))
      (node (ref "P10") (pin "P$133") (pinfunction "P$1_P$133") (pintype "power_in"))
      (node (ref "P10") (pin "P$134") (pinfunction "P$1_P$134") (pintype "power_in"))
      (node (ref "P10") (pin "P$135") (pinfunction "P$1_P$135") (pintype "power_in"))
      (node (ref "P10") (pin "P$136") (pinfunction "P$1_P$136") (pintype "power_in"))
      (node (ref "P10") (pin "P$137") (pinfunction "P$1_P$137") (pintype "power_in"))
      (node (ref "P10") (pin "P$138") (pinfunction "P$1_P$138") (pintype "power_in"))
      (node (ref "P10") (pin "P$139") (pinfunction "P$1_P$139") (pintype "power_in"))
      (node (ref "P10") (pin "P$14") (pinfunction "P$1_P$14") (pintype "power_in"))
      (node (ref "P10") (pin "P$140") (pinfunction "P$1_P$140") (pintype "power_in"))
      (node (ref "P10") (pin "P$141") (pinfunction "P$1_P$141") (pintype "power_in"))
      (node (ref "P10") (pin "P$142") (pinfunction "P$1_P$142") (pintype "power_in"))
      (node (ref "P10") (pin "P$143") (pinfunction "P$1_P$143") (pintype "power_in"))
      (node (ref "P10") (pin "P$144") (pinfunction "P$1_P$144") (pintype "power_in"))
      (node (ref "P10") (pin "P$145") (pinfunction "P$1_P$145") (pintype "power_in"))
      (node (ref "P10") (pin "P$146") (pinfunction "P$1_P$146") (pintype "power_in"))
      (node (ref "P10") (pin "P$147") (pinfunction "P$1_P$147") (pintype "power_in"))
      (node (ref "P10") (pin "P$148") (pinfunction "P$1_P$148") (pintype "power_in"))
      (node (ref "P10") (pin "P$149") (pinfunction "P$1_P$149") (pintype "power_in"))
      (node (ref "P10") (pin "P$15") (pinfunction "P$1_P$15") (pintype "power_in"))
      (node (ref "P10") (pin "P$150") (pinfunction "P$1_P$150") (pintype "power_in"))
      (node (ref "P10") (pin "P$151") (pinfunction "P$1_P$151") (pintype "power_in"))
      (node (ref "P10") (pin "P$153") (pinfunction "P$1_P$153") (pintype "power_in"))
      (node (ref "P10") (pin "P$154") (pinfunction "P$1_P$154") (pintype "power_in"))
      (node (ref "P10") (pin "P$155") (pinfunction "P$1_P$155") (pintype "power_in"))
      (node (ref "P10") (pin "P$156") (pinfunction "P$1_P$156") (pintype "power_in"))
      (node (ref "P10") (pin "P$157") (pinfunction "P$1_P$157") (pintype "power_in"))
      (node (ref "P10") (pin "P$158") (pinfunction "P$1_P$158") (pintype "power_in"))
      (node (ref "P10") (pin "P$159") (pinfunction "P$1_P$159") (pintype "power_in"))
      (node (ref "P10") (pin "P$16") (pinfunction "P$1_P$16") (pintype "power_in"))
      (node (ref "P10") (pin "P$160") (pinfunction "P$1_P$160") (pintype "power_in"))
      (node (ref "P10") (pin "P$161") (pinfunction "P$1_P$161") (pintype "power_in"))
      (node (ref "P10") (pin "P$162") (pinfunction "P$1_P$162") (pintype "power_in"))
      (node (ref "P10") (pin "P$163") (pinfunction "P$1_P$163") (pintype "power_in"))
      (node (ref "P10") (pin "P$164") (pinfunction "P$1_P$164") (pintype "power_in"))
      (node (ref "P10") (pin "P$165") (pinfunction "P$1_P$165") (pintype "power_in"))
      (node (ref "P10") (pin "P$166") (pinfunction "P$1_P$166") (pintype "power_in"))
      (node (ref "P10") (pin "P$167") (pinfunction "P$1_P$167") (pintype "power_in"))
      (node (ref "P10") (pin "P$168") (pinfunction "P$1_P$168") (pintype "power_in"))
      (node (ref "P10") (pin "P$169") (pinfunction "P$1_P$169") (pintype "power_in"))
      (node (ref "P10") (pin "P$17") (pinfunction "P$1_P$17") (pintype "power_in"))
      (node (ref "P10") (pin "P$170") (pinfunction "P$1_P$170") (pintype "power_in"))
      (node (ref "P10") (pin "P$171") (pinfunction "P$1_P$171") (pintype "power_in"))
      (node (ref "P10") (pin "P$172") (pinfunction "P$1_P$172") (pintype "power_in"))
      (node (ref "P10") (pin "P$173") (pinfunction "P$1_P$173") (pintype "power_in"))
      (node (ref "P10") (pin "P$174") (pinfunction "P$1_P$174") (pintype "power_in"))
      (node (ref "P10") (pin "P$175") (pinfunction "P$1_P$175") (pintype "power_in"))
      (node (ref "P10") (pin "P$176") (pinfunction "P$1_P$176") (pintype "power_in"))
      (node (ref "P10") (pin "P$177") (pinfunction "P$1_P$177") (pintype "power_in"))
      (node (ref "P10") (pin "P$178") (pinfunction "P$1_P$178") (pintype "power_in"))
      (node (ref "P10") (pin "P$179") (pinfunction "P$1_P$179") (pintype "power_in"))
      (node (ref "P10") (pin "P$18") (pinfunction "P$1_P$18") (pintype "power_in"))
      (node (ref "P10") (pin "P$180") (pinfunction "P$1_P$180") (pintype "power_in"))
      (node (ref "P10") (pin "P$181") (pinfunction "P$1_P$181") (pintype "power_in"))
      (node (ref "P10") (pin "P$182") (pinfunction "P$1_P$182") (pintype "power_in"))
      (node (ref "P10") (pin "P$183") (pinfunction "P$1_P$183") (pintype "power_in"))
      (node (ref "P10") (pin "P$184") (pinfunction "P$1_P$184") (pintype "power_in"))
      (node (ref "P10") (pin "P$185") (pinfunction "P$1_P$185") (pintype "power_in"))
      (node (ref "P10") (pin "P$186") (pinfunction "P$1_P$186") (pintype "power_in"))
      (node (ref "P10") (pin "P$187") (pinfunction "P$1_P$187") (pintype "power_in"))
      (node (ref "P10") (pin "P$188") (pinfunction "P$1_P$188") (pintype "power_in"))
      (node (ref "P10") (pin "P$19") (pinfunction "P$1_P$19") (pintype "power_in"))
      (node (ref "P10") (pin "P$190") (pinfunction "P$1_P$190") (pintype "power_in"))
      (node (ref "P10") (pin "P$191") (pinfunction "P$1_P$191") (pintype "power_in"))
      (node (ref "P10") (pin "P$192") (pinfunction "P$1_P$192") (pintype "power_in"))
      (node (ref "P10") (pin "P$193") (pinfunction "P$1_P$193") (pintype "power_in"))
      (node (ref "P10") (pin "P$194") (pinfunction "P$1_P$194") (pintype "power_in"))
      (node (ref "P10") (pin "P$195") (pinfunction "P$1_P$195") (pintype "power_in"))
      (node (ref "P10") (pin "P$196") (pinfunction "P$1_P$196") (pintype "power_in"))
      (node (ref "P10") (pin "P$197") (pinfunction "P$1_P$197") (pintype "power_in"))
      (node (ref "P10") (pin "P$198") (pinfunction "P$1_P$198") (pintype "power_in"))
      (node (ref "P10") (pin "P$199") (pinfunction "P$1_P$199") (pintype "power_in"))
      (node (ref "P10") (pin "P$20") (pinfunction "P$1_P$20") (pintype "power_in"))
      (node (ref "P10") (pin "P$200") (pinfunction "P$1_P$200") (pintype "power_in"))
      (node (ref "P10") (pin "P$201") (pinfunction "P$1_P$201") (pintype "power_in"))
      (node (ref "P10") (pin "P$202") (pinfunction "P$1_P$202") (pintype "power_in"))
      (node (ref "P10") (pin "P$203") (pinfunction "P$1_P$203") (pintype "power_in"))
      (node (ref "P10") (pin "P$204") (pinfunction "P$1_P$204") (pintype "power_in"))
      (node (ref "P10") (pin "P$205") (pinfunction "P$1_P$205") (pintype "power_in"))
      (node (ref "P10") (pin "P$206") (pinfunction "P$1_P$206") (pintype "power_in"))
      (node (ref "P10") (pin "P$207") (pinfunction "P$1_P$207") (pintype "power_in"))
      (node (ref "P10") (pin "P$208") (pinfunction "P$1_P$208") (pintype "power_in"))
      (node (ref "P10") (pin "P$209") (pinfunction "P$1_P$209") (pintype "power_in"))
      (node (ref "P10") (pin "P$21") (pinfunction "P$1_P$21") (pintype "power_in"))
      (node (ref "P10") (pin "P$210") (pinfunction "P$1_P$210") (pintype "power_in"))
      (node (ref "P10") (pin "P$211") (pinfunction "P$1_P$211") (pintype "power_in"))
      (node (ref "P10") (pin "P$212") (pinfunction "P$1_P$212") (pintype "power_in"))
      (node (ref "P10") (pin "P$213") (pinfunction "P$1_P$213") (pintype "power_in"))
      (node (ref "P10") (pin "P$214") (pinfunction "P$1_P$214") (pintype "power_in"))
      (node (ref "P10") (pin "P$215") (pinfunction "P$1_P$215") (pintype "power_in"))
      (node (ref "P10") (pin "P$216") (pinfunction "P$1_P$216") (pintype "power_in"))
      (node (ref "P10") (pin "P$217") (pinfunction "P$1_P$217") (pintype "power_in"))
      (node (ref "P10") (pin "P$218") (pinfunction "P$1_P$218") (pintype "power_in"))
      (node (ref "P10") (pin "P$219") (pinfunction "P$1_P$219") (pintype "power_in"))
      (node (ref "P10") (pin "P$22") (pinfunction "P$1_P$22") (pintype "power_in"))
      (node (ref "P10") (pin "P$220") (pinfunction "P$1_P$220") (pintype "power_in"))
      (node (ref "P10") (pin "P$221") (pinfunction "P$1_P$221") (pintype "power_in"))
      (node (ref "P10") (pin "P$222") (pinfunction "P$1_P$222") (pintype "power_in"))
      (node (ref "P10") (pin "P$223") (pinfunction "P$1_P$223") (pintype "power_in"))
      (node (ref "P10") (pin "P$224") (pinfunction "P$1_P$224") (pintype "power_in"))
      (node (ref "P10") (pin "P$225") (pinfunction "P$1_P$225") (pintype "power_in"))
      (node (ref "P10") (pin "P$23") (pinfunction "P$1_P$23") (pintype "power_in"))
      (node (ref "P10") (pin "P$24") (pinfunction "P$1_P$24") (pintype "power_in"))
      (node (ref "P10") (pin "P$25") (pinfunction "P$1_P$25") (pintype "power_in"))
      (node (ref "P10") (pin "P$26") (pinfunction "P$1_P$26") (pintype "power_in"))
      (node (ref "P10") (pin "P$27") (pinfunction "P$1_P$27") (pintype "power_in"))
      (node (ref "P10") (pin "P$28") (pinfunction "P$1_P$28") (pintype "power_in"))
      (node (ref "P10") (pin "P$29") (pinfunction "P$1_P$29") (pintype "power_in"))
      (node (ref "P10") (pin "P$30") (pinfunction "P$1_P$30") (pintype "power_in"))
      (node (ref "P10") (pin "P$31") (pinfunction "P$1_P$31") (pintype "power_in"))
      (node (ref "P10") (pin "P$32") (pinfunction "P$1_P$32") (pintype "power_in"))
      (node (ref "P10") (pin "P$33") (pinfunction "P$1_P$33") (pintype "power_in"))
      (node (ref "P10") (pin "P$34") (pinfunction "P$1_P$34") (pintype "power_in"))
      (node (ref "P10") (pin "P$35") (pinfunction "P$1_P$35") (pintype "power_in"))
      (node (ref "P10") (pin "P$36") (pinfunction "P$1_P$36") (pintype "power_in"))
      (node (ref "P10") (pin "P$37") (pinfunction "P$1_P$37") (pintype "power_in"))
      (node (ref "P10") (pin "P$38") (pinfunction "P$1_P$38") (pintype "power_in"))
      (node (ref "P10") (pin "P$39") (pinfunction "P$1_P$39") (pintype "power_in"))
      (node (ref "P10") (pin "P$40") (pinfunction "P$1_P$40") (pintype "power_in"))
      (node (ref "P10") (pin "P$42") (pinfunction "P$1_P$42") (pintype "power_in"))
      (node (ref "P10") (pin "P$43") (pinfunction "P$1_P$43") (pintype "power_in"))
      (node (ref "P10") (pin "P$44") (pinfunction "P$1_P$44") (pintype "power_in"))
      (node (ref "P10") (pin "P$45") (pinfunction "P$1_P$45") (pintype "power_in"))
      (node (ref "P10") (pin "P$46") (pinfunction "P$1_P$46") (pintype "power_in"))
      (node (ref "P10") (pin "P$47") (pinfunction "P$1_P$47") (pintype "power_in"))
      (node (ref "P10") (pin "P$48") (pinfunction "P$1_P$48") (pintype "power_in"))
      (node (ref "P10") (pin "P$49") (pinfunction "P$1_P$49") (pintype "power_in"))
      (node (ref "P10") (pin "P$5") (pinfunction "P$1_P$5") (pintype "power_in"))
      (node (ref "P10") (pin "P$50") (pinfunction "P$1_P$50") (pintype "power_in"))
      (node (ref "P10") (pin "P$51") (pinfunction "P$1_P$51") (pintype "power_in"))
      (node (ref "P10") (pin "P$52") (pinfunction "P$1_P$52") (pintype "power_in"))
      (node (ref "P10") (pin "P$53") (pinfunction "P$1_P$53") (pintype "power_in"))
      (node (ref "P10") (pin "P$54") (pinfunction "P$1_P$54") (pintype "power_in"))
      (node (ref "P10") (pin "P$55") (pinfunction "P$1_P$55") (pintype "power_in"))
      (node (ref "P10") (pin "P$56") (pinfunction "P$1_P$56") (pintype "power_in"))
      (node (ref "P10") (pin "P$57") (pinfunction "P$1_P$57") (pintype "power_in"))
      (node (ref "P10") (pin "P$58") (pinfunction "P$1_P$58") (pintype "power_in"))
      (node (ref "P10") (pin "P$59") (pinfunction "P$1_P$59") (pintype "power_in"))
      (node (ref "P10") (pin "P$6") (pinfunction "P$1_P$6") (pintype "power_in"))
      (node (ref "P10") (pin "P$60") (pinfunction "P$1_P$60") (pintype "power_in"))
      (node (ref "P10") (pin "P$61") (pinfunction "P$1_P$61") (pintype "power_in"))
      (node (ref "P10") (pin "P$62") (pinfunction "P$1_P$62") (pintype "power_in"))
      (node (ref "P10") (pin "P$63") (pinfunction "P$1_P$63") (pintype "power_in"))
      (node (ref "P10") (pin "P$64") (pinfunction "P$1_P$64") (pintype "power_in"))
      (node (ref "P10") (pin "P$65") (pinfunction "P$1_P$65") (pintype "power_in"))
      (node (ref "P10") (pin "P$66") (pinfunction "P$1_P$66") (pintype "power_in"))
      (node (ref "P10") (pin "P$67") (pinfunction "P$1_P$67") (pintype "power_in"))
      (node (ref "P10") (pin "P$68") (pinfunction "P$1_P$68") (pintype "power_in"))
      (node (ref "P10") (pin "P$69") (pinfunction "P$1_P$69") (pintype "power_in"))
      (node (ref "P10") (pin "P$7") (pinfunction "P$1_P$7") (pintype "power_in"))
      (node (ref "P10") (pin "P$70") (pinfunction "P$1_P$70") (pintype "power_in"))
      (node (ref "P10") (pin "P$71") (pinfunction "P$1_P$71") (pintype "power_in"))
      (node (ref "P10") (pin "P$72") (pinfunction "P$1_P$72") (pintype "power_in"))
      (node (ref "P10") (pin "P$73") (pinfunction "P$1_P$73") (pintype "power_in"))
      (node (ref "P10") (pin "P$74") (pinfunction "P$1_P$74") (pintype "power_in"))
      (node (ref "P10") (pin "P$75") (pinfunction "P$1_P$75") (pintype "power_in"))
      (node (ref "P10") (pin "P$76") (pinfunction "P$1_P$76") (pintype "power_in"))
      (node (ref "P10") (pin "P$77") (pinfunction "P$1_P$77") (pintype "power_in"))
      (node (ref "P10") (pin "P$79") (pinfunction "P$1_P$79") (pintype "power_in"))
      (node (ref "P10") (pin "P$8") (pinfunction "P$1_P$8") (pintype "power_in"))
      (node (ref "P10") (pin "P$80") (pinfunction "P$1_P$80") (pintype "power_in"))
      (node (ref "P10") (pin "P$81") (pinfunction "P$1_P$81") (pintype "power_in"))
      (node (ref "P10") (pin "P$82") (pinfunction "P$1_P$82") (pintype "power_in"))
      (node (ref "P10") (pin "P$83") (pinfunction "P$1_P$83") (pintype "power_in"))
      (node (ref "P10") (pin "P$84") (pinfunction "P$1_P$84") (pintype "power_in"))
      (node (ref "P10") (pin "P$85") (pinfunction "P$1_P$85") (pintype "power_in"))
      (node (ref "P10") (pin "P$86") (pinfunction "P$1_P$86") (pintype "power_in"))
      (node (ref "P10") (pin "P$87") (pinfunction "P$1_P$87") (pintype "power_in"))
      (node (ref "P10") (pin "P$88") (pinfunction "P$1_P$88") (pintype "power_in"))
      (node (ref "P10") (pin "P$89") (pinfunction "P$1_P$89") (pintype "power_in"))
      (node (ref "P10") (pin "P$9") (pinfunction "P$1_P$9") (pintype "power_in"))
      (node (ref "P10") (pin "P$90") (pinfunction "P$1_P$90") (pintype "power_in"))
      (node (ref "P10") (pin "P$91") (pinfunction "P$1_P$91") (pintype "power_in"))
      (node (ref "P10") (pin "P$92") (pinfunction "P$1_P$92") (pintype "power_in"))
      (node (ref "P10") (pin "P$93") (pinfunction "P$1_P$93") (pintype "power_in"))
      (node (ref "P10") (pin "P$94") (pinfunction "P$1_P$94") (pintype "power_in"))
      (node (ref "P10") (pin "P$95") (pinfunction "P$1_P$95") (pintype "power_in"))
      (node (ref "P10") (pin "P$96") (pinfunction "P$1_P$96") (pintype "power_in"))
      (node (ref "P10") (pin "P$97") (pinfunction "P$1_P$97") (pintype "power_in"))
      (node (ref "P10") (pin "P$98") (pinfunction "P$1_P$98") (pintype "power_in"))
      (node (ref "P10") (pin "P$99") (pinfunction "P$1_P$99") (pintype "power_in"))
    )
    (net (code "12") (name "/P11") (class "Default")
      (node (ref "JP1") (pin "P$12") (pinfunction "11_P$12") (pintype "bidirectional"))
      (node (ref "P11") (pin "P$10") (pinfunction "P$1_P$10") (pintype "power_in"))
      (node (ref "P11") (pin "P$100") (pinfunction "P$1_P$100") (pintype "power_in"))
      (node (ref "P11") (pin "P$101") (pinfunction "P$1_P$101") (pintype "power_in"))
      (node (ref "P11") (pin "P$102") (pinfunction "P$1_P$102") (pintype "power_in"))
      (node (ref "P11") (pin "P$103") (pinfunction "P$1_P$103") (pintype "power_in"))
      (node (ref "P11") (pin "P$104") (pinfunction "P$1_P$104") (pintype "power_in"))
      (node (ref "P11") (pin "P$105") (pinfunction "P$1_P$105") (pintype "power_in"))
      (node (ref "P11") (pin "P$106") (pinfunction "P$1_P$106") (pintype "power_in"))
      (node (ref "P11") (pin "P$107") (pinfunction "P$1_P$107") (pintype "power_in"))
      (node (ref "P11") (pin "P$108") (pinfunction "P$1_P$108") (pintype "power_in"))
      (node (ref "P11") (pin "P$109") (pinfunction "P$1_P$109") (pintype "power_in"))
      (node (ref "P11") (pin "P$11") (pinfunction "P$1_P$11") (pintype "power_in"))
      (node (ref "P11") (pin "P$110") (pinfunction "P$1_P$110") (pintype "power_in"))
      (node (ref "P11") (pin "P$111") (pinfunction "P$1_P$111") (pintype "power_in"))
      (node (ref "P11") (pin "P$112") (pinfunction "P$1_P$112") (pintype "power_in"))
      (node (ref "P11") (pin "P$114") (pinfunction "P$1_P$114") (pintype "power_in"))
      (node (ref "P11") (pin "P$115") (pinfunction "P$1_P$115") (pintype "power_in"))
      (node (ref "P11") (pin "P$116") (pinfunction "P$1_P$116") (pintype "power_in"))
      (node (ref "P11") (pin "P$117") (pinfunction "P$1_P$117") (pintype "power_in"))
      (node (ref "P11") (pin "P$118") (pinfunction "P$1_P$118") (pintype "power_in"))
      (node (ref "P11") (pin "P$119") (pinfunction "P$1_P$119") (pintype "power_in"))
      (node (ref "P11") (pin "P$12") (pinfunction "P$1_P$12") (pintype "power_in"))
      (node (ref "P11") (pin "P$120") (pinfunction "P$1_P$120") (pintype "power_in"))
      (node (ref "P11") (pin "P$121") (pinfunction "P$1_P$121") (pintype "power_in"))
      (node (ref "P11") (pin "P$122") (pinfunction "P$1_P$122") (pintype "power_in"))
      (node (ref "P11") (pin "P$123") (pinfunction "P$1_P$123") (pintype "power_in"))
      (node (ref "P11") (pin "P$124") (pinfunction "P$1_P$124") (pintype "power_in"))
      (node (ref "P11") (pin "P$125") (pinfunction "P$1_P$125") (pintype "power_in"))
      (node (ref "P11") (pin "P$126") (pinfunction "P$1_P$126") (pintype "power_in"))
      (node (ref "P11") (pin "P$127") (pinfunction "P$1_P$127") (pintype "power_in"))
      (node (ref "P11") (pin "P$128") (pinfunction "P$1_P$128") (pintype "power_in"))
      (node (ref "P11") (pin "P$129") (pinfunction "P$1_P$129") (pintype "power_in"))
      (node (ref "P11") (pin "P$13") (pinfunction "P$1_P$13") (pintype "power_in"))
      (node (ref "P11") (pin "P$130") (pinfunction "P$1_P$130") (pintype "power_in"))
      (node (ref "P11") (pin "P$131") (pinfunction "P$1_P$131") (pintype "power_in"))
      (node (ref "P11") (pin "P$132") (pinfunction "P$1_P$132") (pintype "power_in"))
      (node (ref "P11") (pin "P$133") (pinfunction "P$1_P$133") (pintype "power_in"))
      (node (ref "P11") (pin "P$134") (pinfunction "P$1_P$134") (pintype "power_in"))
      (node (ref "P11") (pin "P$135") (pinfunction "P$1_P$135") (pintype "power_in"))
      (node (ref "P11") (pin "P$136") (pinfunction "P$1_P$136") (pintype "power_in"))
      (node (ref "P11") (pin "P$137") (pinfunction "P$1_P$137") (pintype "power_in"))
      (node (ref "P11") (pin "P$138") (pinfunction "P$1_P$138") (pintype "power_in"))
      (node (ref "P11") (pin "P$139") (pinfunction "P$1_P$139") (pintype "power_in"))
      (node (ref "P11") (pin "P$14") (pinfunction "P$1_P$14") (pintype "power_in"))
      (node (ref "P11") (pin "P$140") (pinfunction "P$1_P$140") (pintype "power_in"))
      (node (ref "P11") (pin "P$141") (pinfunction "P$1_P$141") (pintype "power_in"))
      (node (ref "P11") (pin "P$142") (pinfunction "P$1_P$142") (pintype "power_in"))
      (node (ref "P11") (pin "P$143") (pinfunction "P$1_P$143") (pintype "power_in"))
      (node (ref "P11") (pin "P$144") (pinfunction "P$1_P$144") (pintype "power_in"))
      (node (ref "P11") (pin "P$145") (pinfunction "P$1_P$145") (pintype "power_in"))
      (node (ref "P11") (pin "P$146") (pinfunction "P$1_P$146") (pintype "power_in"))
      (node (ref "P11") (pin "P$147") (pinfunction "P$1_P$147") (pintype "power_in"))
      (node (ref "P11") (pin "P$148") (pinfunction "P$1_P$148") (pintype "power_in"))
      (node (ref "P11") (pin "P$149") (pinfunction "P$1_P$149") (pintype "power_in"))
      (node (ref "P11") (pin "P$15") (pinfunction "P$1_P$15") (pintype "power_in"))
      (node (ref "P11") (pin "P$151") (pinfunction "P$1_P$151") (pintype "power_in"))
      (node (ref "P11") (pin "P$152") (pinfunction "P$1_P$152") (pintype "power_in"))
      (node (ref "P11") (pin "P$153") (pinfunction "P$1_P$153") (pintype "power_in"))
      (node (ref "P11") (pin "P$154") (pinfunction "P$1_P$154") (pintype "power_in"))
      (node (ref "P11") (pin "P$155") (pinfunction "P$1_P$155") (pintype "power_in"))
      (node (ref "P11") (pin "P$156") (pinfunction "P$1_P$156") (pintype "power_in"))
      (node (ref "P11") (pin "P$157") (pinfunction "P$1_P$157") (pintype "power_in"))
      (node (ref "P11") (pin "P$158") (pinfunction "P$1_P$158") (pintype "power_in"))
      (node (ref "P11") (pin "P$159") (pinfunction "P$1_P$159") (pintype "power_in"))
      (node (ref "P11") (pin "P$16") (pinfunction "P$1_P$16") (pintype "power_in"))
      (node (ref "P11") (pin "P$160") (pinfunction "P$1_P$160") (pintype "power_in"))
      (node (ref "P11") (pin "P$161") (pinfunction "P$1_P$161") (pintype "power_in"))
      (node (ref "P11") (pin "P$162") (pinfunction "P$1_P$162") (pintype "power_in"))
      (node (ref "P11") (pin "P$163") (pinfunction "P$1_P$163") (pintype "power_in"))
      (node (ref "P11") (pin "P$164") (pinfunction "P$1_P$164") (pintype "power_in"))
      (node (ref "P11") (pin "P$165") (pinfunction "P$1_P$165") (pintype "power_in"))
      (node (ref "P11") (pin "P$166") (pinfunction "P$1_P$166") (pintype "power_in"))
      (node (ref "P11") (pin "P$167") (pinfunction "P$1_P$167") (pintype "power_in"))
      (node (ref "P11") (pin "P$168") (pinfunction "P$1_P$168") (pintype "power_in"))
      (node (ref "P11") (pin "P$169") (pinfunction "P$1_P$169") (pintype "power_in"))
      (node (ref "P11") (pin "P$17") (pinfunction "P$1_P$17") (pintype "power_in"))
      (node (ref "P11") (pin "P$170") (pinfunction "P$1_P$170") (pintype "power_in"))
      (node (ref "P11") (pin "P$171") (pinfunction "P$1_P$171") (pintype "power_in"))
      (node (ref "P11") (pin "P$172") (pinfunction "P$1_P$172") (pintype "power_in"))
      (node (ref "P11") (pin "P$173") (pinfunction "P$1_P$173") (pintype "power_in"))
      (node (ref "P11") (pin "P$174") (pinfunction "P$1_P$174") (pintype "power_in"))
      (node (ref "P11") (pin "P$175") (pinfunction "P$1_P$175") (pintype "power_in"))
      (node (ref "P11") (pin "P$176") (pinfunction "P$1_P$176") (pintype "power_in"))
      (node (ref "P11") (pin "P$177") (pinfunction "P$1_P$177") (pintype "power_in"))
      (node (ref "P11") (pin "P$178") (pinfunction "P$1_P$178") (pintype "power_in"))
      (node (ref "P11") (pin "P$179") (pinfunction "P$1_P$179") (pintype "power_in"))
      (node (ref "P11") (pin "P$18") (pinfunction "P$1_P$18") (pintype "power_in"))
      (node (ref "P11") (pin "P$180") (pinfunction "P$1_P$180") (pintype "power_in"))
      (node (ref "P11") (pin "P$181") (pinfunction "P$1_P$181") (pintype "power_in"))
      (node (ref "P11") (pin "P$182") (pinfunction "P$1_P$182") (pintype "power_in"))
      (node (ref "P11") (pin "P$183") (pinfunction "P$1_P$183") (pintype "power_in"))
      (node (ref "P11") (pin "P$184") (pinfunction "P$1_P$184") (pintype "power_in"))
      (node (ref "P11") (pin "P$185") (pinfunction "P$1_P$185") (pintype "power_in"))
      (node (ref "P11") (pin "P$186") (pinfunction "P$1_P$186") (pintype "power_in"))
      (node (ref "P11") (pin "P$188") (pinfunction "P$1_P$188") (pintype "power_in"))
      (node (ref "P11") (pin "P$189") (pinfunction "P$1_P$189") (pintype "power_in"))
      (node (ref "P11") (pin "P$19") (pinfunction "P$1_P$19") (pintype "power_in"))
      (node (ref "P11") (pin "P$190") (pinfunction "P$1_P$190") (pintype "power_in"))
      (node (ref "P11") (pin "P$191") (pinfunction "P$1_P$191") (pintype "power_in"))
      (node (ref "P11") (pin "P$192") (pinfunction "P$1_P$192") (pintype "power_in"))
      (node (ref "P11") (pin "P$193") (pinfunction "P$1_P$193") (pintype "power_in"))
      (node (ref "P11") (pin "P$194") (pinfunction "P$1_P$194") (pintype "power_in"))
      (node (ref "P11") (pin "P$195") (pinfunction "P$1_P$195") (pintype "power_in"))
      (node (ref "P11") (pin "P$196") (pinfunction "P$1_P$196") (pintype "power_in"))
      (node (ref "P11") (pin "P$197") (pinfunction "P$1_P$197") (pintype "power_in"))
      (node (ref "P11") (pin "P$198") (pinfunction "P$1_P$198") (pintype "power_in"))
      (node (ref "P11") (pin "P$199") (pinfunction "P$1_P$199") (pintype "power_in"))
      (node (ref "P11") (pin "P$20") (pinfunction "P$1_P$20") (pintype "power_in"))
      (node (ref "P11") (pin "P$200") (pinfunction "P$1_P$200") (pintype "power_in"))
      (node (ref "P11") (pin "P$201") (pinfunction "P$1_P$201") (pintype "power_in"))
      (node (ref "P11") (pin "P$202") (pinfunction "P$1_P$202") (pintype "power_in"))
      (node (ref "P11") (pin "P$203") (pinfunction "P$1_P$203") (pintype "power_in"))
      (node (ref "P11") (pin "P$204") (pinfunction "P$1_P$204") (pintype "power_in"))
      (node (ref "P11") (pin "P$205") (pinfunction "P$1_P$205") (pintype "power_in"))
      (node (ref "P11") (pin "P$206") (pinfunction "P$1_P$206") (pintype "power_in"))
      (node (ref "P11") (pin "P$207") (pinfunction "P$1_P$207") (pintype "power_in"))
      (node (ref "P11") (pin "P$208") (pinfunction "P$1_P$208") (pintype "power_in"))
      (node (ref "P11") (pin "P$209") (pinfunction "P$1_P$209") (pintype "power_in"))
      (node (ref "P11") (pin "P$21") (pinfunction "P$1_P$21") (pintype "power_in"))
      (node (ref "P11") (pin "P$210") (pinfunction "P$1_P$210") (pintype "power_in"))
      (node (ref "P11") (pin "P$211") (pinfunction "P$1_P$211") (pintype "power_in"))
      (node (ref "P11") (pin "P$212") (pinfunction "P$1_P$212") (pintype "power_in"))
      (node (ref "P11") (pin "P$213") (pinfunction "P$1_P$213") (pintype "power_in"))
      (node (ref "P11") (pin "P$214") (pinfunction "P$1_P$214") (pintype "power_in"))
      (node (ref "P11") (pin "P$215") (pinfunction "P$1_P$215") (pintype "power_in"))
      (node (ref "P11") (pin "P$216") (pinfunction "P$1_P$216") (pintype "power_in"))
      (node (ref "P11") (pin "P$217") (pinfunction "P$1_P$217") (pintype "power_in"))
      (node (ref "P11") (pin "P$218") (pinfunction "P$1_P$218") (pintype "power_in"))
      (node (ref "P11") (pin "P$219") (pinfunction "P$1_P$219") (pintype "power_in"))
      (node (ref "P11") (pin "P$22") (pinfunction "P$1_P$22") (pintype "power_in"))
      (node (ref "P11") (pin "P$220") (pinfunction "P$1_P$220") (pintype "power_in"))
      (node (ref "P11") (pin "P$221") (pinfunction "P$1_P$221") (pintype "power_in"))
      (node (ref "P11") (pin "P$222") (pinfunction "P$1_P$222") (pintype "power_in"))
      (node (ref "P11") (pin "P$223") (pinfunction "P$1_P$223") (pintype "power_in"))
      (node (ref "P11") (pin "P$23") (pinfunction "P$1_P$23") (pintype "power_in"))
      (node (ref "P11") (pin "P$24") (pinfunction "P$1_P$24") (pintype "power_in"))
      (node (ref "P11") (pin "P$25") (pinfunction "P$1_P$25") (pintype "power_in"))
      (node (ref "P11") (pin "P$26") (pinfunction "P$1_P$26") (pintype "power_in"))
      (node (ref "P11") (pin "P$27") (pinfunction "P$1_P$27") (pintype "power_in"))
      (node (ref "P11") (pin "P$28") (pinfunction "P$1_P$28") (pintype "power_in"))
      (node (ref "P11") (pin "P$29") (pinfunction "P$1_P$29") (pintype "power_in"))
      (node (ref "P11") (pin "P$30") (pinfunction "P$1_P$30") (pintype "power_in"))
      (node (ref "P11") (pin "P$31") (pinfunction "P$1_P$31") (pintype "power_in"))
      (node (ref "P11") (pin "P$32") (pinfunction "P$1_P$32") (pintype "power_in"))
      (node (ref "P11") (pin "P$33") (pinfunction "P$1_P$33") (pintype "power_in"))
      (node (ref "P11") (pin "P$34") (pinfunction "P$1_P$34") (pintype "power_in"))
      (node (ref "P11") (pin "P$35") (pinfunction "P$1_P$35") (pintype "power_in"))
      (node (ref "P11") (pin "P$36") (pinfunction "P$1_P$36") (pintype "power_in"))
      (node (ref "P11") (pin "P$37") (pinfunction "P$1_P$37") (pintype "power_in"))
      (node (ref "P11") (pin "P$38") (pinfunction "P$1_P$38") (pintype "power_in"))
      (node (ref "P11") (pin "P$39") (pinfunction "P$1_P$39") (pintype "power_in"))
      (node (ref "P11") (pin "P$40") (pinfunction "P$1_P$40") (pintype "power_in"))
      (node (ref "P11") (pin "P$41") (pinfunction "P$1_P$41") (pintype "power_in"))
      (node (ref "P11") (pin "P$42") (pinfunction "P$1_P$42") (pintype "power_in"))
      (node (ref "P11") (pin "P$43") (pinfunction "P$1_P$43") (pintype "power_in"))
      (node (ref "P11") (pin "P$44") (pinfunction "P$1_P$44") (pintype "power_in"))
      (node (ref "P11") (pin "P$45") (pinfunction "P$1_P$45") (pintype "power_in"))
      (node (ref "P11") (pin "P$46") (pinfunction "P$1_P$46") (pintype "power_in"))
      (node (ref "P11") (pin "P$47") (pinfunction "P$1_P$47") (pintype "power_in"))
      (node (ref "P11") (pin "P$48") (pinfunction "P$1_P$48") (pintype "power_in"))
      (node (ref "P11") (pin "P$49") (pinfunction "P$1_P$49") (pintype "power_in"))
      (node (ref "P11") (pin "P$5") (pinfunction "P$1_P$5") (pintype "power_in"))
      (node (ref "P11") (pin "P$50") (pinfunction "P$1_P$50") (pintype "power_in"))
      (node (ref "P11") (pin "P$51") (pinfunction "P$1_P$51") (pintype "power_in"))
      (node (ref "P11") (pin "P$52") (pinfunction "P$1_P$52") (pintype "power_in"))
      (node (ref "P11") (pin "P$53") (pinfunction "P$1_P$53") (pintype "power_in"))
      (node (ref "P11") (pin "P$54") (pinfunction "P$1_P$54") (pintype "power_in"))
      (node (ref "P11") (pin "P$55") (pinfunction "P$1_P$55") (pintype "power_in"))
      (node (ref "P11") (pin "P$56") (pinfunction "P$1_P$56") (pintype "power_in"))
      (node (ref "P11") (pin "P$57") (pinfunction "P$1_P$57") (pintype "power_in"))
      (node (ref "P11") (pin "P$58") (pinfunction "P$1_P$58") (pintype "power_in"))
      (node (ref "P11") (pin "P$59") (pinfunction "P$1_P$59") (pintype "power_in"))
      (node (ref "P11") (pin "P$6") (pinfunction "P$1_P$6") (pintype "power_in"))
      (node (ref "P11") (pin "P$60") (pinfunction "P$1_P$60") (pintype "power_in"))
      (node (ref "P11") (pin "P$61") (pinfunction "P$1_P$61") (pintype "power_in"))
      (node (ref "P11") (pin "P$62") (pinfunction "P$1_P$62") (pintype "power_in"))
      (node (ref "P11") (pin "P$63") (pinfunction "P$1_P$63") (pintype "power_in"))
      (node (ref "P11") (pin "P$64") (pinfunction "P$1_P$64") (pintype "power_in"))
      (node (ref "P11") (pin "P$65") (pinfunction "P$1_P$65") (pintype "power_in"))
      (node (ref "P11") (pin "P$66") (pinfunction "P$1_P$66") (pintype "power_in"))
      (node (ref "P11") (pin "P$67") (pinfunction "P$1_P$67") (pintype "power_in"))
      (node (ref "P11") (pin "P$68") (pinfunction "P$1_P$68") (pintype "power_in"))
      (node (ref "P11") (pin "P$69") (pinfunction "P$1_P$69") (pintype "power_in"))
      (node (ref "P11") (pin "P$7") (pinfunction "P$1_P$7") (pintype "power_in"))
      (node (ref "P11") (pin "P$70") (pinfunction "P$1_P$70") (pintype "power_in"))
      (node (ref "P11") (pin "P$71") (pinfunction "P$1_P$71") (pintype "power_in"))
      (node (ref "P11") (pin "P$72") (pinfunction "P$1_P$72") (pintype "power_in"))
      (node (ref "P11") (pin "P$73") (pinfunction "P$1_P$73") (pintype "power_in"))
      (node (ref "P11") (pin "P$74") (pinfunction "P$1_P$74") (pintype "power_in"))
      (node (ref "P11") (pin "P$75") (pinfunction "P$1_P$75") (pintype "power_in"))
      (node (ref "P11") (pin "P$76") (pinfunction "P$1_P$76") (pintype "power_in"))
      (node (ref "P11") (pin "P$77") (pinfunction "P$1_P$77") (pintype "power_in"))
      (node (ref "P11") (pin "P$78") (pinfunction "P$1_P$78") (pintype "power_in"))
      (node (ref "P11") (pin "P$79") (pinfunction "P$1_P$79") (pintype "power_in"))
      (node (ref "P11") (pin "P$8") (pinfunction "P$1_P$8") (pintype "power_in"))
      (node (ref "P11") (pin "P$80") (pinfunction "P$1_P$80") (pintype "power_in"))
      (node (ref "P11") (pin "P$81") (pinfunction "P$1_P$81") (pintype "power_in"))
      (node (ref "P11") (pin "P$82") (pinfunction "P$1_P$82") (pintype "power_in"))
      (node (ref "P11") (pin "P$83") (pinfunction "P$1_P$83") (pintype "power_in"))
      (node (ref "P11") (pin "P$84") (pinfunction "P$1_P$84") (pintype "power_in"))
      (node (ref "P11") (pin "P$85") (pinfunction "P$1_P$85") (pintype "power_in"))
      (node (ref "P11") (pin "P$86") (pinfunction "P$1_P$86") (pintype "power_in"))
      (node (ref "P11") (pin "P$87") (pinfunction "P$1_P$87") (pintype "power_in"))
      (node (ref "P11") (pin "P$88") (pinfunction "P$1_P$88") (pintype "power_in"))
      (node (ref "P11") (pin "P$89") (pinfunction "P$1_P$89") (pintype "power_in"))
      (node (ref "P11") (pin "P$9") (pinfunction "P$1_P$9") (pintype "power_in"))
      (node (ref "P11") (pin "P$90") (pinfunction "P$1_P$90") (pintype "power_in"))
      (node (ref "P11") (pin "P$91") (pinfunction "P$1_P$91") (pintype "power_in"))
      (node (ref "P11") (pin "P$92") (pinfunction "P$1_P$92") (pintype "power_in"))
      (node (ref "P11") (pin "P$93") (pinfunction "P$1_P$93") (pintype "power_in"))
      (node (ref "P11") (pin "P$94") (pinfunction "P$1_P$94") (pintype "power_in"))
      (node (ref "P11") (pin "P$95") (pinfunction "P$1_P$95") (pintype "power_in"))
      (node (ref "P11") (pin "P$96") (pinfunction "P$1_P$96") (pintype "power_in"))
      (node (ref "P11") (pin "P$97") (pinfunction "P$1_P$97") (pintype "power_in"))
      (node (ref "P11") (pin "P$98") (pinfunction "P$1_P$98") (pintype "power_in"))
      (node (ref "P11") (pin "P$99") (pinfunction "P$1_P$99") (pintype "power_in"))
    )
    (net (code "13") (name "/P12+") (class "Default")
      (node (ref "J1") (pin "1") (pinfunction "1_1") (pintype "bidirectional"))
      (node (ref "J1") (pin "2") (pinfunction "2_2") (pintype "bidirectional"))
      (node (ref "J1") (pin "3") (pinfunction "3_3") (pintype "bidirectional"))
      (node (ref "J1") (pin "4") (pinfunction "4_4") (pintype "bidirectional"))
      (node (ref "J1") (pin "5") (pinfunction "5_5") (pintype "bidirectional"))
      (node (ref "J1") (pin "6") (pinfunction "6_6") (pintype "bidirectional"))
      (node (ref "JP1") (pin "P$13") (pinfunction "12_P$13") (pintype "bidirectional"))
      (node (ref "P12") (pin "P$10") (pinfunction "P$0_P$10") (pintype "power_in"))
      (node (ref "P12") (pin "P$100") (pinfunction "P$0_P$100") (pintype "power_in"))
      (node (ref "P12") (pin "P$101") (pinfunction "P$0_P$101") (pintype "power_in"))
      (node (ref "P12") (pin "P$102") (pinfunction "P$0_P$102") (pintype "power_in"))
      (node (ref "P12") (pin "P$103") (pinfunction "P$0_P$103") (pintype "power_in"))
      (node (ref "P12") (pin "P$104") (pinfunction "P$0_P$104") (pintype "power_in"))
      (node (ref "P12") (pin "P$105") (pinfunction "P$0_P$105") (pintype "power_in"))
      (node (ref "P12") (pin "P$106") (pinfunction "P$0_P$106") (pintype "power_in"))
      (node (ref "P12") (pin "P$107") (pinfunction "P$0_P$107") (pintype "power_in"))
      (node (ref "P12") (pin "P$108") (pinfunction "P$0_P$108") (pintype "power_in"))
      (node (ref "P12") (pin "P$109") (pinfunction "P$0_P$109") (pintype "power_in"))
      (node (ref "P12") (pin "P$11") (pinfunction "P$0_P$11") (pintype "power_in"))
      (node (ref "P12") (pin "P$110") (pinfunction "P$0_P$110") (pintype "power_in"))
      (node (ref "P12") (pin "P$12") (pinfunction "P$0_P$12") (pintype "power_in"))
      (node (ref "P12") (pin "P$13") (pinfunction "P$0_P$13") (pintype "power_in"))
      (node (ref "P12") (pin "P$14") (pinfunction "P$0_P$14") (pintype "power_in"))
      (node (ref "P12") (pin "P$15") (pinfunction "P$0_P$15") (pintype "power_in"))
      (node (ref "P12") (pin "P$16") (pinfunction "P$0_P$16") (pintype "power_in"))
      (node (ref "P12") (pin "P$17") (pinfunction "P$0_P$17") (pintype "power_in"))
      (node (ref "P12") (pin "P$18") (pinfunction "P$0_P$18") (pintype "power_in"))
      (node (ref "P12") (pin "P$181") (pinfunction "P$0_P$181") (pintype "power_in"))
      (node (ref "P12") (pin "P$182") (pinfunction "P$0_P$182") (pintype "power_in"))
      (node (ref "P12") (pin "P$183") (pinfunction "P$0_P$183") (pintype "power_in"))
      (node (ref "P12") (pin "P$184") (pinfunction "P$0_P$184") (pintype "power_in"))
      (node (ref "P12") (pin "P$185") (pinfunction "P$0_P$185") (pintype "power_in"))
      (node (ref "P12") (pin "P$186") (pinfunction "P$0_P$186") (pintype "power_in"))
      (node (ref "P12") (pin "P$187") (pinfunction "P$0_P$187") (pintype "power_in"))
      (node (ref "P12") (pin "P$188") (pinfunction "P$0_P$188") (pintype "power_in"))
      (node (ref "P12") (pin "P$189") (pinfunction "P$0_P$189") (pintype "power_in"))
      (node (ref "P12") (pin "P$19") (pinfunction "P$0_P$19") (pintype "power_in"))
      (node (ref "P12") (pin "P$190") (pinfunction "P$0_P$190") (pintype "power_in"))
      (node (ref "P12") (pin "P$191") (pinfunction "P$0_P$191") (pintype "power_in"))
      (node (ref "P12") (pin "P$192") (pinfunction "P$0_P$192") (pintype "power_in"))
      (node (ref "P12") (pin "P$193") (pinfunction "P$0_P$193") (pintype "power_in"))
      (node (ref "P12") (pin "P$194") (pinfunction "P$0_P$194") (pintype "power_in"))
      (node (ref "P12") (pin "P$195") (pinfunction "P$0_P$195") (pintype "power_in"))
      (node (ref "P12") (pin "P$196") (pinfunction "P$0_P$196") (pintype "power_in"))
      (node (ref "P12") (pin "P$197") (pinfunction "P$0_P$197") (pintype "power_in"))
      (node (ref "P12") (pin "P$198") (pinfunction "P$0_P$198") (pintype "power_in"))
      (node (ref "P12") (pin "P$199") (pinfunction "P$0_P$199") (pintype "power_in"))
      (node (ref "P12") (pin "P$20") (pinfunction "P$0_P$20") (pintype "power_in"))
      (node (ref "P12") (pin "P$200") (pinfunction "P$0_P$200") (pintype "power_in"))
      (node (ref "P12") (pin "P$201") (pinfunction "P$0_P$201") (pintype "power_in"))
      (node (ref "P12") (pin "P$202") (pinfunction "P$0_P$202") (pintype "power_in"))
      (node (ref "P12") (pin "P$203") (pinfunction "P$0_P$203") (pintype "power_in"))
      (node (ref "P12") (pin "P$204") (pinfunction "P$0_P$204") (pintype "power_in"))
      (node (ref "P12") (pin "P$205") (pinfunction "P$0_P$205") (pintype "power_in"))
      (node (ref "P12") (pin "P$206") (pinfunction "P$0_P$206") (pintype "power_in"))
      (node (ref "P12") (pin "P$207") (pinfunction "P$0_P$207") (pintype "power_in"))
      (node (ref "P12") (pin "P$208") (pinfunction "P$0_P$208") (pintype "power_in"))
      (node (ref "P12") (pin "P$209") (pinfunction "P$0_P$209") (pintype "power_in"))
      (node (ref "P12") (pin "P$21") (pinfunction "P$0_P$21") (pintype "power_in"))
      (node (ref "P12") (pin "P$210") (pinfunction "P$0_P$210") (pintype "power_in"))
      (node (ref "P12") (pin "P$211") (pinfunction "P$0_P$211") (pintype "power_in"))
      (node (ref "P12") (pin "P$212") (pinfunction "P$0_P$212") (pintype "power_in"))
      (node (ref "P12") (pin "P$213") (pinfunction "P$0_P$213") (pintype "power_in"))
      (node (ref "P12") (pin "P$214") (pinfunction "P$0_P$214") (pintype "power_in"))
      (node (ref "P12") (pin "P$215") (pinfunction "P$0_P$215") (pintype "power_in"))
      (node (ref "P12") (pin "P$216") (pinfunction "P$0_P$216") (pintype "power_in"))
      (node (ref "P12") (pin "P$217") (pinfunction "P$0_P$217") (pintype "power_in"))
      (node (ref "P12") (pin "P$218") (pinfunction "P$0_P$218") (pintype "power_in"))
      (node (ref "P12") (pin "P$219") (pinfunction "P$0_P$219") (pintype "power_in"))
      (node (ref "P12") (pin "P$22") (pinfunction "P$0_P$22") (pintype "power_in"))
      (node (ref "P12") (pin "P$220") (pinfunction "P$0_P$220") (pintype "power_in"))
      (node (ref "P12") (pin "P$221") (pinfunction "P$0_P$221") (pintype "power_in"))
      (node (ref "P12") (pin "P$222") (pinfunction "P$0_P$222") (pintype "power_in"))
      (node (ref "P12") (pin "P$223") (pinfunction "P$0_P$223") (pintype "power_in"))
      (node (ref "P12") (pin "P$224") (pinfunction "P$0_P$224") (pintype "power_in"))
      (node (ref "P12") (pin "P$225") (pinfunction "P$0_P$225") (pintype "power_in"))
      (node (ref "P12") (pin "P$226") (pinfunction "P$0_P$226") (pintype "power_in"))
      (node (ref "P12") (pin "P$227") (pinfunction "P$0_P$227") (pintype "power_in"))
      (node (ref "P12") (pin "P$228") (pinfunction "P$0_P$228") (pintype "power_in"))
      (node (ref "P12") (pin "P$229") (pinfunction "P$0_P$229") (pintype "power_in"))
      (node (ref "P12") (pin "P$23") (pinfunction "P$0_P$23") (pintype "power_in"))
      (node (ref "P12") (pin "P$230") (pinfunction "P$0_P$230") (pintype "power_in"))
      (node (ref "P12") (pin "P$231") (pinfunction "P$0_P$231") (pintype "power_in"))
      (node (ref "P12") (pin "P$232") (pinfunction "P$0_P$232") (pintype "power_in"))
      (node (ref "P12") (pin "P$233") (pinfunction "P$0_P$233") (pintype "power_in"))
      (node (ref "P12") (pin "P$234") (pinfunction "P$0_P$234") (pintype "power_in"))
      (node (ref "P12") (pin "P$235") (pinfunction "P$0_P$235") (pintype "power_in"))
      (node (ref "P12") (pin "P$236") (pinfunction "P$0_P$236") (pintype "power_in"))
      (node (ref "P12") (pin "P$237") (pinfunction "P$0_P$237") (pintype "power_in"))
      (node (ref "P12") (pin "P$238") (pinfunction "P$0_P$238") (pintype "power_in"))
      (node (ref "P12") (pin "P$239") (pinfunction "P$0_P$239") (pintype "power_in"))
      (node (ref "P12") (pin "P$24") (pinfunction "P$0_P$24") (pintype "power_in"))
      (node (ref "P12") (pin "P$240") (pinfunction "P$0_P$240") (pintype "power_in"))
      (node (ref "P12") (pin "P$241") (pinfunction "P$0_P$241") (pintype "power_in"))
      (node (ref "P12") (pin "P$242") (pinfunction "P$0_P$242") (pintype "power_in"))
      (node (ref "P12") (pin "P$243") (pinfunction "P$0_P$243") (pintype "power_in"))
      (node (ref "P12") (pin "P$244") (pinfunction "P$0_P$244") (pintype "power_in"))
      (node (ref "P12") (pin "P$245") (pinfunction "P$0_P$245") (pintype "power_in"))
      (node (ref "P12") (pin "P$246") (pinfunction "P$0_P$246") (pintype "power_in"))
      (node (ref "P12") (pin "P$247") (pinfunction "P$0_P$247") (pintype "power_in"))
      (node (ref "P12") (pin "P$248") (pinfunction "P$0_P$248") (pintype "power_in"))
      (node (ref "P12") (pin "P$249") (pinfunction "P$0_P$249") (pintype "power_in"))
      (node (ref "P12") (pin "P$25") (pinfunction "P$0_P$25") (pintype "power_in"))
      (node (ref "P12") (pin "P$250") (pinfunction "P$0_P$250") (pintype "power_in"))
      (node (ref "P12") (pin "P$251") (pinfunction "P$0_P$251") (pintype "power_in"))
      (node (ref "P12") (pin "P$252") (pinfunction "P$0_P$252") (pintype "power_in"))
      (node (ref "P12") (pin "P$253") (pinfunction "P$0_P$253") (pintype "power_in"))
      (node (ref "P12") (pin "P$254") (pinfunction "P$0_P$254") (pintype "power_in"))
      (node (ref "P12") (pin "P$255") (pinfunction "P$0_P$255") (pintype "power_in"))
      (node (ref "P12") (pin "P$256") (pinfunction "P$0_P$256") (pintype "power_in"))
      (node (ref "P12") (pin "P$257") (pinfunction "P$0_P$257") (pintype "power_in"))
      (node (ref "P12") (pin "P$258") (pinfunction "P$0_P$258") (pintype "power_in"))
      (node (ref "P12") (pin "P$259") (pinfunction "P$0_P$259") (pintype "power_in"))
      (node (ref "P12") (pin "P$26") (pinfunction "P$0_P$26") (pintype "power_in"))
      (node (ref "P12") (pin "P$260") (pinfunction "P$0_P$260") (pintype "power_in"))
      (node (ref "P12") (pin "P$261") (pinfunction "P$0_P$261") (pintype "power_in"))
      (node (ref "P12") (pin "P$262") (pinfunction "P$0_P$262") (pintype "power_in"))
      (node (ref "P12") (pin "P$263") (pinfunction "P$0_P$263") (pintype "power_in"))
      (node (ref "P12") (pin "P$264") (pinfunction "P$0_P$264") (pintype "power_in"))
      (node (ref "P12") (pin "P$265") (pinfunction "P$0_P$265") (pintype "power_in"))
      (node (ref "P12") (pin "P$266") (pinfunction "P$0_P$266") (pintype "power_in"))
      (node (ref "P12") (pin "P$267") (pinfunction "P$0_P$267") (pintype "power_in"))
      (node (ref "P12") (pin "P$268") (pinfunction "P$0_P$268") (pintype "power_in"))
      (node (ref "P12") (pin "P$269") (pinfunction "P$0_P$269") (pintype "power_in"))
      (node (ref "P12") (pin "P$27") (pinfunction "P$0_P$27") (pintype "power_in"))
      (node (ref "P12") (pin "P$270") (pinfunction "P$0_P$270") (pintype "power_in"))
      (node (ref "P12") (pin "P$271") (pinfunction "P$0_P$271") (pintype "power_in"))
      (node (ref "P12") (pin "P$272") (pinfunction "P$0_P$272") (pintype "power_in"))
      (node (ref "P12") (pin "P$273") (pinfunction "P$0_P$273") (pintype "power_in"))
      (node (ref "P12") (pin "P$274") (pinfunction "P$0_P$274") (pintype "power_in"))
      (node (ref "P12") (pin "P$275") (pinfunction "P$0_P$275") (pintype "power_in"))
      (node (ref "P12") (pin "P$276") (pinfunction "P$0_P$276") (pintype "power_in"))
      (node (ref "P12") (pin "P$277") (pinfunction "P$0_P$277") (pintype "power_in"))
      (node (ref "P12") (pin "P$278") (pinfunction "P$0_P$278") (pintype "power_in"))
      (node (ref "P12") (pin "P$279") (pinfunction "P$0_P$279") (pintype "power_in"))
      (node (ref "P12") (pin "P$28") (pinfunction "P$0_P$28") (pintype "power_in"))
      (node (ref "P12") (pin "P$280") (pinfunction "P$0_P$280") (pintype "power_in"))
      (node (ref "P12") (pin "P$281") (pinfunction "P$0_P$281") (pintype "power_in"))
      (node (ref "P12") (pin "P$282") (pinfunction "P$0_P$282") (pintype "power_in"))
      (node (ref "P12") (pin "P$283") (pinfunction "P$0_P$283") (pintype "power_in"))
      (node (ref "P12") (pin "P$284") (pinfunction "P$0_P$284") (pintype "power_in"))
      (node (ref "P12") (pin "P$285") (pinfunction "P$0_P$285") (pintype "power_in"))
      (node (ref "P12") (pin "P$286") (pinfunction "P$0_P$286") (pintype "power_in"))
      (node (ref "P12") (pin "P$287") (pinfunction "P$0_P$287") (pintype "power_in"))
      (node (ref "P12") (pin "P$288") (pinfunction "P$0_P$288") (pintype "power_in"))
      (node (ref "P12") (pin "P$289") (pinfunction "P$0_P$289") (pintype "power_in"))
      (node (ref "P12") (pin "P$29") (pinfunction "P$0_P$29") (pintype "power_in"))
      (node (ref "P12") (pin "P$290") (pinfunction "P$0_P$290") (pintype "power_in"))
      (node (ref "P12") (pin "P$291") (pinfunction "P$0_P$291") (pintype "power_in"))
      (node (ref "P12") (pin "P$292") (pinfunction "P$0_P$292") (pintype "power_in"))
      (node (ref "P12") (pin "P$293") (pinfunction "P$0_P$293") (pintype "power_in"))
      (node (ref "P12") (pin "P$294") (pinfunction "P$0_P$294") (pintype "power_in"))
      (node (ref "P12") (pin "P$295") (pinfunction "P$0_P$295") (pintype "power_in"))
      (node (ref "P12") (pin "P$296") (pinfunction "P$0_P$296") (pintype "power_in"))
      (node (ref "P12") (pin "P$297") (pinfunction "P$0_P$297") (pintype "power_in"))
      (node (ref "P12") (pin "P$298") (pinfunction "P$0_P$298") (pintype "power_in"))
      (node (ref "P12") (pin "P$299") (pinfunction "P$0_P$299") (pintype "power_in"))
      (node (ref "P12") (pin "P$3") (pinfunction "P$0_P$3") (pintype "power_in"))
      (node (ref "P12") (pin "P$30") (pinfunction "P$0_P$30") (pintype "power_in"))
      (node (ref "P12") (pin "P$300") (pinfunction "P$0_P$300") (pintype "power_in"))
      (node (ref "P12") (pin "P$301") (pinfunction "P$0_P$301") (pintype "power_in"))
      (node (ref "P12") (pin "P$302") (pinfunction "P$0_P$302") (pintype "power_in"))
      (node (ref "P12") (pin "P$303") (pinfunction "P$0_P$303") (pintype "power_in"))
      (node (ref "P12") (pin "P$304") (pinfunction "P$0_P$304") (pintype "power_in"))
      (node (ref "P12") (pin "P$305") (pinfunction "P$0_P$305") (pintype "power_in"))
      (node (ref "P12") (pin "P$306") (pinfunction "P$0_P$306") (pintype "power_in"))
      (node (ref "P12") (pin "P$307") (pinfunction "P$0_P$307") (pintype "power_in"))
      (node (ref "P12") (pin "P$308") (pinfunction "P$0_P$308") (pintype "power_in"))
      (node (ref "P12") (pin "P$309") (pinfunction "P$0_P$309") (pintype "power_in"))
      (node (ref "P12") (pin "P$31") (pinfunction "P$0_P$31") (pintype "power_in"))
      (node (ref "P12") (pin "P$310") (pinfunction "P$0_P$310") (pintype "power_in"))
      (node (ref "P12") (pin "P$311") (pinfunction "P$0_P$311") (pintype "power_in"))
      (node (ref "P12") (pin "P$312") (pinfunction "P$0_P$312") (pintype "power_in"))
      (node (ref "P12") (pin "P$313") (pinfunction "P$0_P$313") (pintype "power_in"))
      (node (ref "P12") (pin "P$314") (pinfunction "P$0_P$314") (pintype "power_in"))
      (node (ref "P12") (pin "P$315") (pinfunction "P$0_P$315") (pintype "power_in"))
      (node (ref "P12") (pin "P$316") (pinfunction "P$0_P$316") (pintype "power_in"))
      (node (ref "P12") (pin "P$317") (pinfunction "P$0_P$317") (pintype "power_in"))
      (node (ref "P12") (pin "P$318") (pinfunction "P$0_P$318") (pintype "power_in"))
      (node (ref "P12") (pin "P$319") (pinfunction "P$0_P$319") (pintype "power_in"))
      (node (ref "P12") (pin "P$32") (pinfunction "P$0_P$32") (pintype "power_in"))
      (node (ref "P12") (pin "P$320") (pinfunction "P$0_P$320") (pintype "power_in"))
      (node (ref "P12") (pin "P$321") (pinfunction "P$0_P$321") (pintype "power_in"))
      (node (ref "P12") (pin "P$322") (pinfunction "P$0_P$322") (pintype "power_in"))
      (node (ref "P12") (pin "P$323") (pinfunction "P$0_P$323") (pintype "power_in"))
      (node (ref "P12") (pin "P$324") (pinfunction "P$0_P$324") (pintype "power_in"))
      (node (ref "P12") (pin "P$325") (pinfunction "P$0_P$325") (pintype "power_in"))
      (node (ref "P12") (pin "P$326") (pinfunction "P$0_P$326") (pintype "power_in"))
      (node (ref "P12") (pin "P$327") (pinfunction "P$0_P$327") (pintype "power_in"))
      (node (ref "P12") (pin "P$328") (pinfunction "P$0_P$328") (pintype "power_in"))
      (node (ref "P12") (pin "P$329") (pinfunction "P$0_P$329") (pintype "power_in"))
      (node (ref "P12") (pin "P$33") (pinfunction "P$0_P$33") (pintype "power_in"))
      (node (ref "P12") (pin "P$330") (pinfunction "P$0_P$330") (pintype "power_in"))
      (node (ref "P12") (pin "P$331") (pinfunction "P$0_P$331") (pintype "power_in"))
      (node (ref "P12") (pin "P$332") (pinfunction "P$0_P$332") (pintype "power_in"))
      (node (ref "P12") (pin "P$333") (pinfunction "P$0_P$333") (pintype "power_in"))
      (node (ref "P12") (pin "P$334") (pinfunction "P$0_P$334") (pintype "power_in"))
      (node (ref "P12") (pin "P$335") (pinfunction "P$0_P$335") (pintype "power_in"))
      (node (ref "P12") (pin "P$336") (pinfunction "P$0_P$336") (pintype "power_in"))
      (node (ref "P12") (pin "P$337") (pinfunction "P$0_P$337") (pintype "power_in"))
      (node (ref "P12") (pin "P$338") (pinfunction "P$0_P$338") (pintype "power_in"))
      (node (ref "P12") (pin "P$339") (pinfunction "P$0_P$339") (pintype "power_in"))
      (node (ref "P12") (pin "P$34") (pinfunction "P$0_P$34") (pintype "power_in"))
      (node (ref "P12") (pin "P$340") (pinfunction "P$0_P$340") (pintype "power_in"))
      (node (ref "P12") (pin "P$341") (pinfunction "P$0_P$341") (pintype "power_in"))
      (node (ref "P12") (pin "P$342") (pinfunction "P$0_P$342") (pintype "power_in"))
      (node (ref "P12") (pin "P$343") (pinfunction "P$0_P$343") (pintype "power_in"))
      (node (ref "P12") (pin "P$344") (pinfunction "P$0_P$344") (pintype "power_in"))
      (node (ref "P12") (pin "P$345") (pinfunction "P$0_P$345") (pintype "power_in"))
      (node (ref "P12") (pin "P$346") (pinfunction "P$0_P$346") (pintype "power_in"))
      (node (ref "P12") (pin "P$347") (pinfunction "P$0_P$347") (pintype "power_in"))
      (node (ref "P12") (pin "P$348") (pinfunction "P$0_P$348") (pintype "power_in"))
      (node (ref "P12") (pin "P$349") (pinfunction "P$0_P$349") (pintype "power_in"))
      (node (ref "P12") (pin "P$35") (pinfunction "P$0_P$35") (pintype "power_in"))
      (node (ref "P12") (pin "P$350") (pinfunction "P$0_P$350") (pintype "power_in"))
      (node (ref "P12") (pin "P$351") (pinfunction "P$0_P$351") (pintype "power_in"))
      (node (ref "P12") (pin "P$352") (pinfunction "P$0_P$352") (pintype "power_in"))
      (node (ref "P12") (pin "P$353") (pinfunction "P$0_P$353") (pintype "power_in"))
      (node (ref "P12") (pin "P$354") (pinfunction "P$0_P$354") (pintype "power_in"))
      (node (ref "P12") (pin "P$355") (pinfunction "P$0_P$355") (pintype "power_in"))
      (node (ref "P12") (pin "P$356") (pinfunction "P$0_P$356") (pintype "power_in"))
      (node (ref "P12") (pin "P$357") (pinfunction "P$0_P$357") (pintype "power_in"))
      (node (ref "P12") (pin "P$358") (pinfunction "P$0_P$358") (pintype "power_in"))
      (node (ref "P12") (pin "P$359") (pinfunction "P$0_P$359") (pintype "power_in"))
      (node (ref "P12") (pin "P$36") (pinfunction "P$0_P$36") (pintype "power_in"))
      (node (ref "P12") (pin "P$360") (pinfunction "P$0_P$360") (pintype "power_in"))
      (node (ref "P12") (pin "P$37") (pinfunction "P$0_P$37") (pintype "power_in"))
      (node (ref "P12") (pin "P$38") (pinfunction "P$0_P$38") (pintype "power_in"))
      (node (ref "P12") (pin "P$39") (pinfunction "P$0_P$39") (pintype "power_in"))
      (node (ref "P12") (pin "P$4") (pinfunction "P$0_P$4") (pintype "power_in"))
      (node (ref "P12") (pin "P$40") (pinfunction "P$0_P$40") (pintype "power_in"))
      (node (ref "P12") (pin "P$41") (pinfunction "P$0_P$41") (pintype "power_in"))
      (node (ref "P12") (pin "P$42") (pinfunction "P$0_P$42") (pintype "power_in"))
      (node (ref "P12") (pin "P$43") (pinfunction "P$0_P$43") (pintype "power_in"))
      (node (ref "P12") (pin "P$44") (pinfunction "P$0_P$44") (pintype "power_in"))
      (node (ref "P12") (pin "P$45") (pinfunction "P$0_P$45") (pintype "power_in"))
      (node (ref "P12") (pin "P$46") (pinfunction "P$0_P$46") (pintype "power_in"))
      (node (ref "P12") (pin "P$47") (pinfunction "P$0_P$47") (pintype "power_in"))
      (node (ref "P12") (pin "P$48") (pinfunction "P$0_P$48") (pintype "power_in"))
      (node (ref "P12") (pin "P$49") (pinfunction "P$0_P$49") (pintype "power_in"))
      (node (ref "P12") (pin "P$5") (pinfunction "P$0_P$5") (pintype "power_in"))
      (node (ref "P12") (pin "P$50") (pinfunction "P$0_P$50") (pintype "power_in"))
      (node (ref "P12") (pin "P$51") (pinfunction "P$0_P$51") (pintype "power_in"))
      (node (ref "P12") (pin "P$52") (pinfunction "P$0_P$52") (pintype "power_in"))
      (node (ref "P12") (pin "P$53") (pinfunction "P$0_P$53") (pintype "power_in"))
      (node (ref "P12") (pin "P$54") (pinfunction "P$0_P$54") (pintype "power_in"))
      (node (ref "P12") (pin "P$55") (pinfunction "P$0_P$55") (pintype "power_in"))
      (node (ref "P12") (pin "P$56") (pinfunction "P$0_P$56") (pintype "power_in"))
      (node (ref "P12") (pin "P$57") (pinfunction "P$0_P$57") (pintype "power_in"))
      (node (ref "P12") (pin "P$58") (pinfunction "P$0_P$58") (pintype "power_in"))
      (node (ref "P12") (pin "P$59") (pinfunction "P$0_P$59") (pintype "power_in"))
      (node (ref "P12") (pin "P$6") (pinfunction "P$0_P$6") (pintype "power_in"))
      (node (ref "P12") (pin "P$60") (pinfunction "P$0_P$60") (pintype "power_in"))
      (node (ref "P12") (pin "P$61") (pinfunction "P$0_P$61") (pintype "power_in"))
      (node (ref "P12") (pin "P$62") (pinfunction "P$0_P$62") (pintype "power_in"))
      (node (ref "P12") (pin "P$63") (pinfunction "P$0_P$63") (pintype "power_in"))
      (node (ref "P12") (pin "P$64") (pinfunction "P$0_P$64") (pintype "power_in"))
      (node (ref "P12") (pin "P$65") (pinfunction "P$0_P$65") (pintype "power_in"))
      (node (ref "P12") (pin "P$66") (pinfunction "P$0_P$66") (pintype "power_in"))
      (node (ref "P12") (pin "P$67") (pinfunction "P$0_P$67") (pintype "power_in"))
      (node (ref "P12") (pin "P$68") (pinfunction "P$0_P$68") (pintype "power_in"))
      (node (ref "P12") (pin "P$69") (pinfunction "P$0_P$69") (pintype "power_in"))
      (node (ref "P12") (pin "P$7") (pinfunction "P$0_P$7") (pintype "power_in"))
      (node (ref "P12") (pin "P$70") (pinfunction "P$0_P$70") (pintype "power_in"))
      (node (ref "P12") (pin "P$71") (pinfunction "P$0_P$71") (pintype "power_in"))
      (node (ref "P12") (pin "P$72") (pinfunction "P$0_P$72") (pintype "power_in"))
      (node (ref "P12") (pin "P$73") (pinfunction "P$0_P$73") (pintype "power_in"))
      (node (ref "P12") (pin "P$74") (pinfunction "P$0_P$74") (pintype "power_in"))
      (node (ref "P12") (pin "P$75") (pinfunction "P$0_P$75") (pintype "power_in"))
      (node (ref "P12") (pin "P$76") (pinfunction "P$0_P$76") (pintype "power_in"))
      (node (ref "P12") (pin "P$77") (pinfunction "P$0_P$77") (pintype "power_in"))
      (node (ref "P12") (pin "P$78") (pinfunction "P$0_P$78") (pintype "power_in"))
      (node (ref "P12") (pin "P$79") (pinfunction "P$0_P$79") (pintype "power_in"))
      (node (ref "P12") (pin "P$8") (pinfunction "P$0_P$8") (pintype "power_in"))
      (node (ref "P12") (pin "P$80") (pinfunction "P$0_P$80") (pintype "power_in"))
      (node (ref "P12") (pin "P$81") (pinfunction "P$0_P$81") (pintype "power_in"))
      (node (ref "P12") (pin "P$82") (pinfunction "P$0_P$82") (pintype "power_in"))
      (node (ref "P12") (pin "P$83") (pinfunction "P$0_P$83") (pintype "power_in"))
      (node (ref "P12") (pin "P$84") (pinfunction "P$0_P$84") (pintype "power_in"))
      (node (ref "P12") (pin "P$85") (pinfunction "P$0_P$85") (pintype "power_in"))
      (node (ref "P12") (pin "P$86") (pinfunction "P$0_P$86") (pintype "power_in"))
      (node (ref "P12") (pin "P$87") (pinfunction "P$0_P$87") (pintype "power_in"))
      (node (ref "P12") (pin "P$88") (pinfunction "P$0_P$88") (pintype "power_in"))
      (node (ref "P12") (pin "P$89") (pinfunction "P$0_P$89") (pintype "power_in"))
      (node (ref "P12") (pin "P$9") (pinfunction "P$0_P$9") (pintype "power_in"))
      (node (ref "P12") (pin "P$90") (pinfunction "P$0_P$90") (pintype "power_in"))
      (node (ref "P12") (pin "P$91") (pinfunction "P$0_P$91") (pintype "power_in"))
      (node (ref "P12") (pin "P$92") (pinfunction "P$0_P$92") (pintype "power_in"))
      (node (ref "P12") (pin "P$93") (pinfunction "P$0_P$93") (pintype "power_in"))
      (node (ref "P12") (pin "P$94") (pinfunction "P$0_P$94") (pintype "power_in"))
      (node (ref "P12") (pin "P$95") (pinfunction "P$0_P$95") (pintype "power_in"))
      (node (ref "P12") (pin "P$96") (pinfunction "P$0_P$96") (pintype "power_in"))
      (node (ref "P12") (pin "P$97") (pinfunction "P$0_P$97") (pintype "power_in"))
      (node (ref "P12") (pin "P$98") (pinfunction "P$0_P$98") (pintype "power_in"))
      (node (ref "P12") (pin "P$99") (pinfunction "P$0_P$99") (pintype "power_in"))
    )
    (net (code "14") (name "Net-(J1-Pad10)") (class "Default")
      (node (ref "J1") (pin "10") (pinfunction "10_10") (pintype "bidirectional"))
      (node (ref "J1") (pin "11") (pinfunction "11_11") (pintype "bidirectional"))
      (node (ref "J1") (pin "12") (pinfunction "12_12") (pintype "bidirectional"))
      (node (ref "J1") (pin "7") (pinfunction "7_7") (pintype "bidirectional"))
      (node (ref "J1") (pin "8") (pinfunction "8_8") (pintype "bidirectional"))
      (node (ref "J1") (pin "9") (pinfunction "9_9") (pintype "bidirectional"))
    )
  )
)
